# PCB_ICBExt-R1_0-J36-CH01.net
KiCad netlist of a schematic drawn in EAGLE
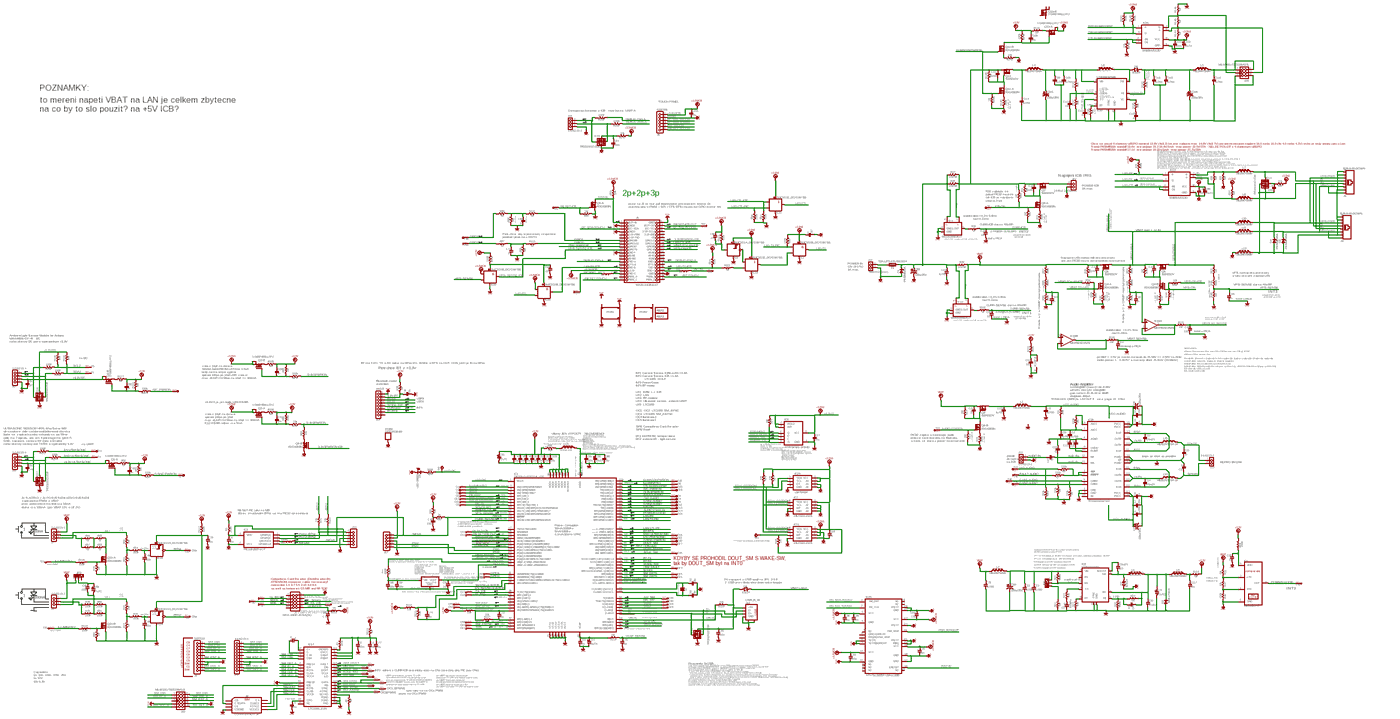
[diagram p0: schematic, sheet 1, overview]
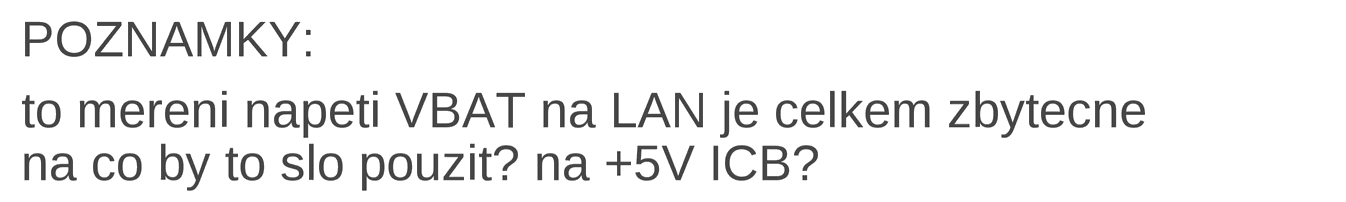
[diagram p1: schematic, sheet 1, part 1 of 6]
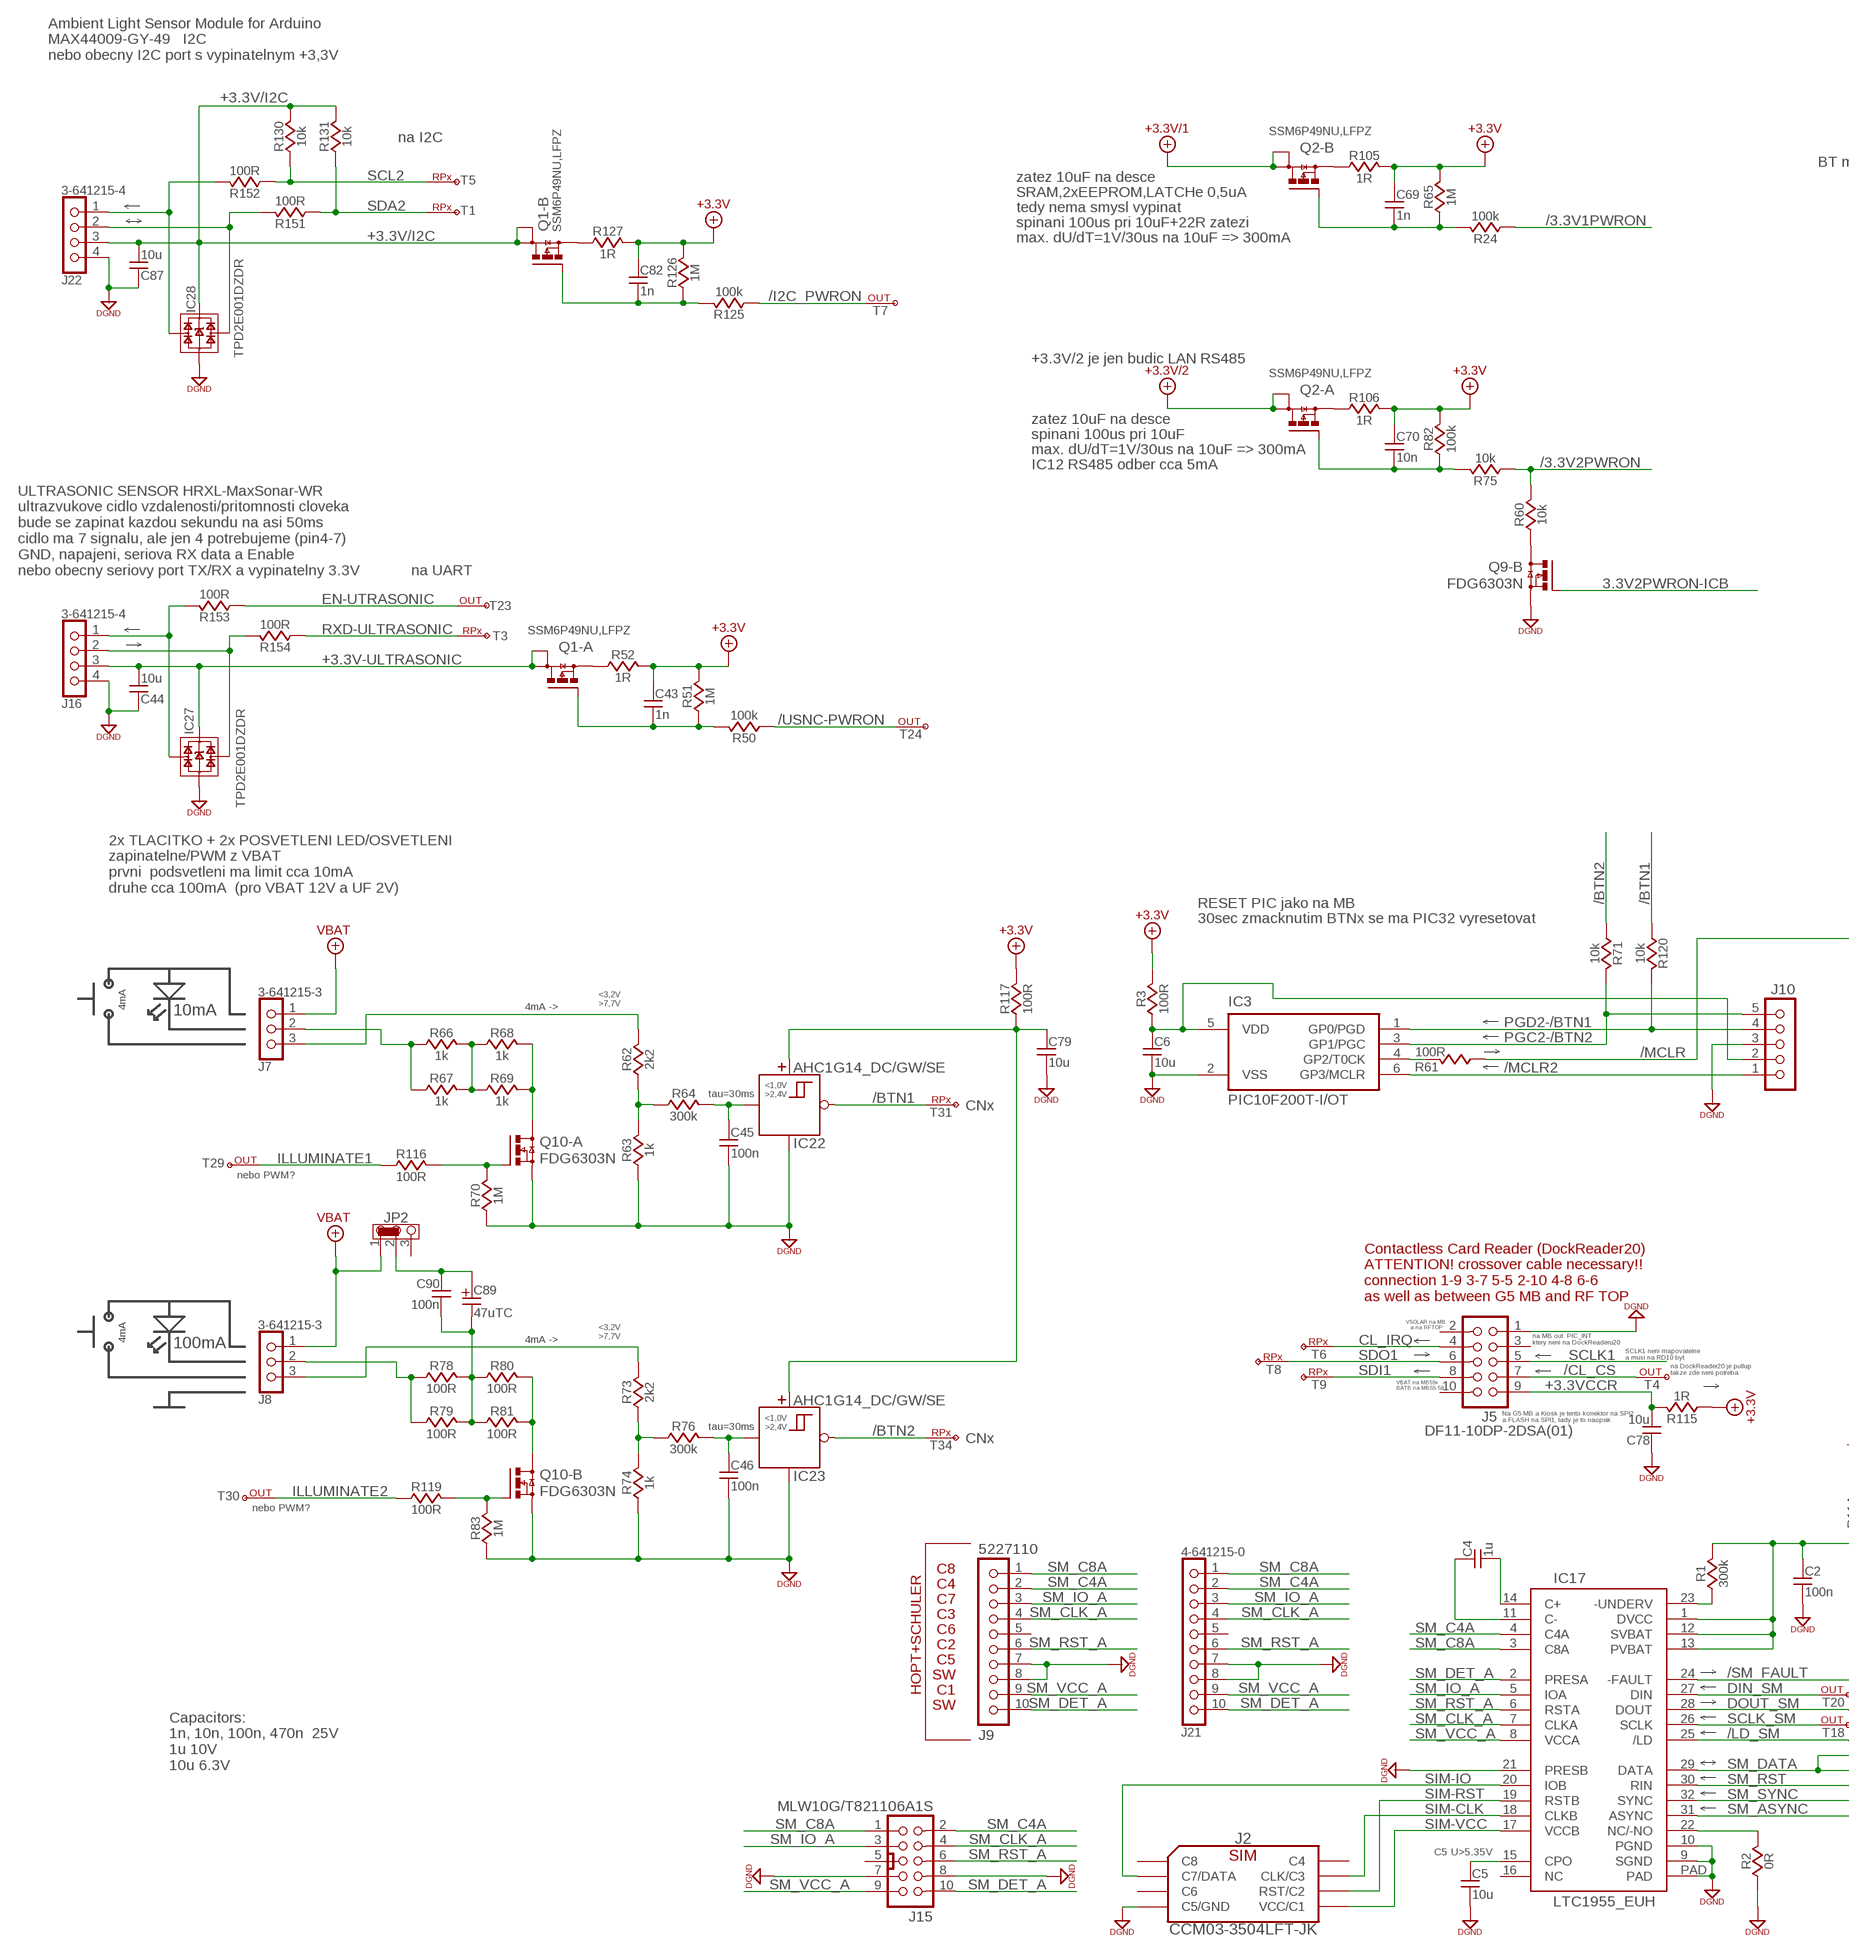
[diagram p2: schematic, sheet 1, part 2 of 6]
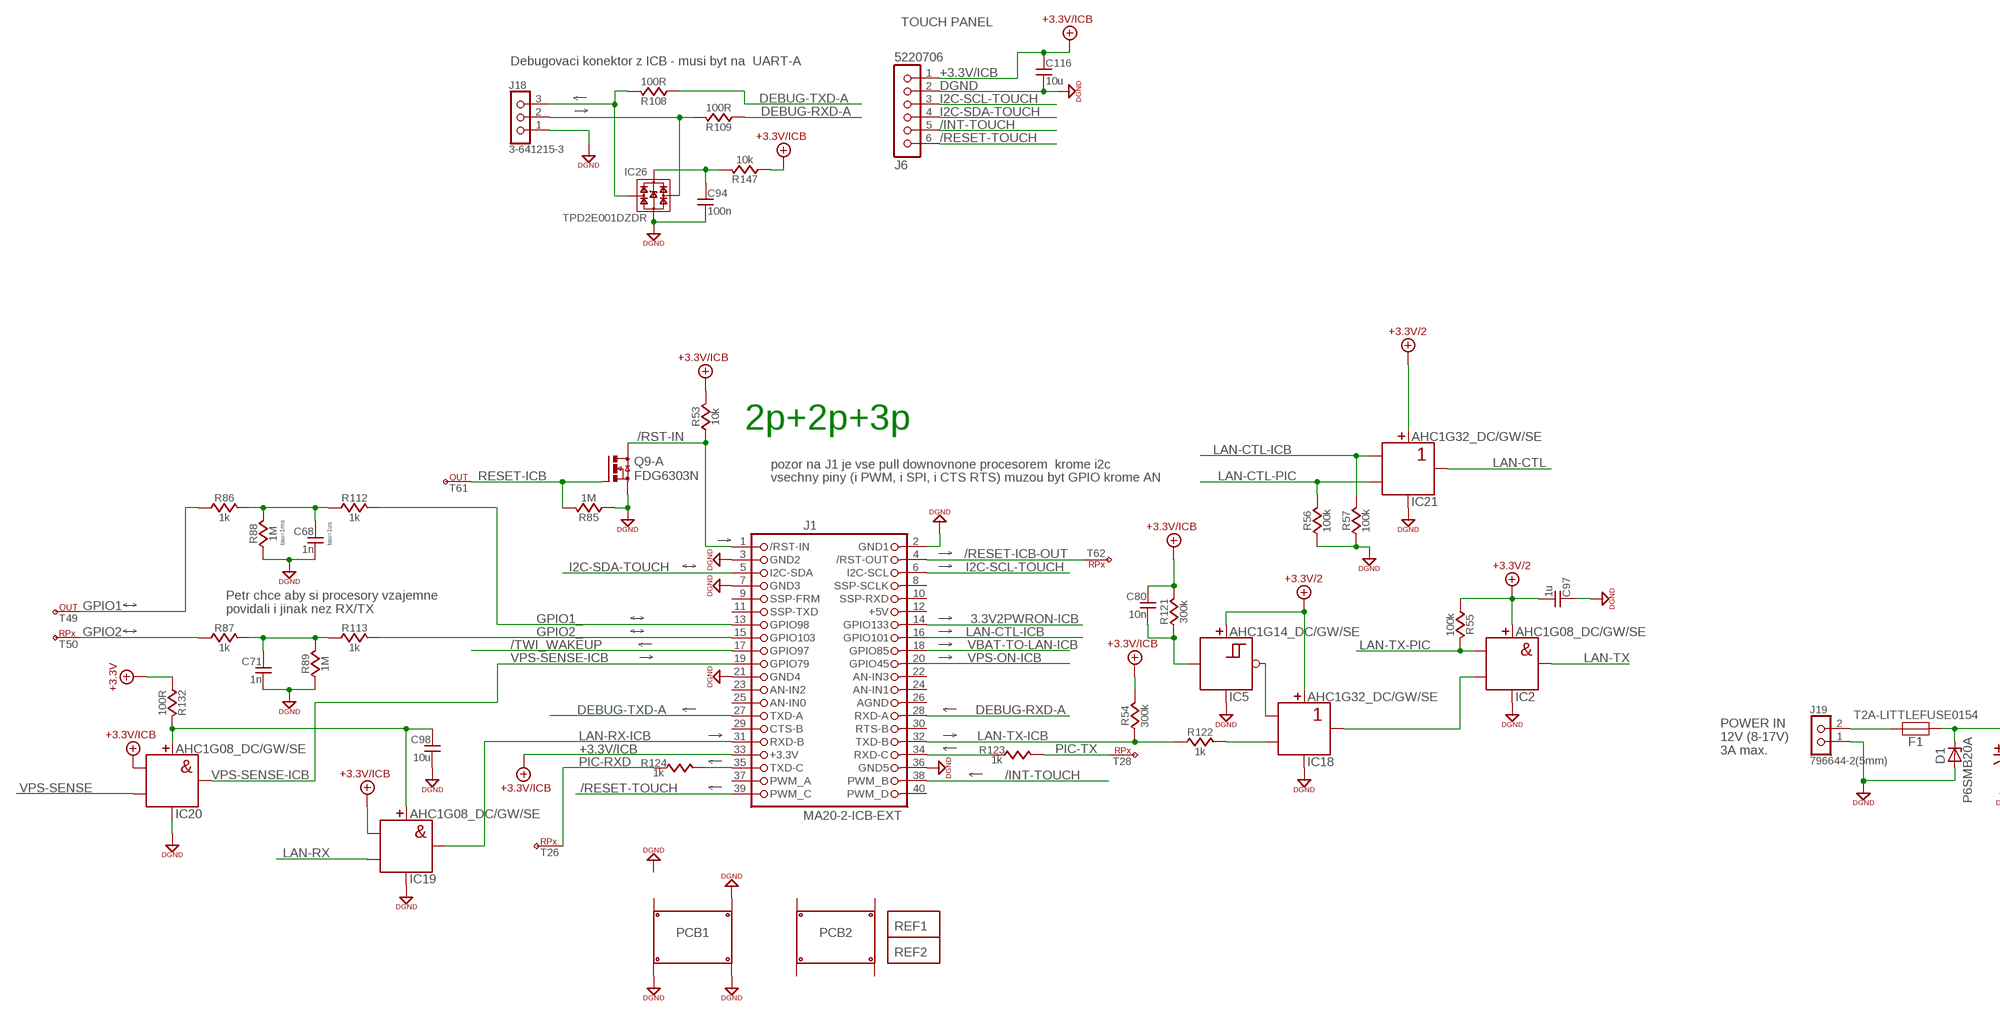
[diagram p3: schematic, sheet 1, part 3 of 6]
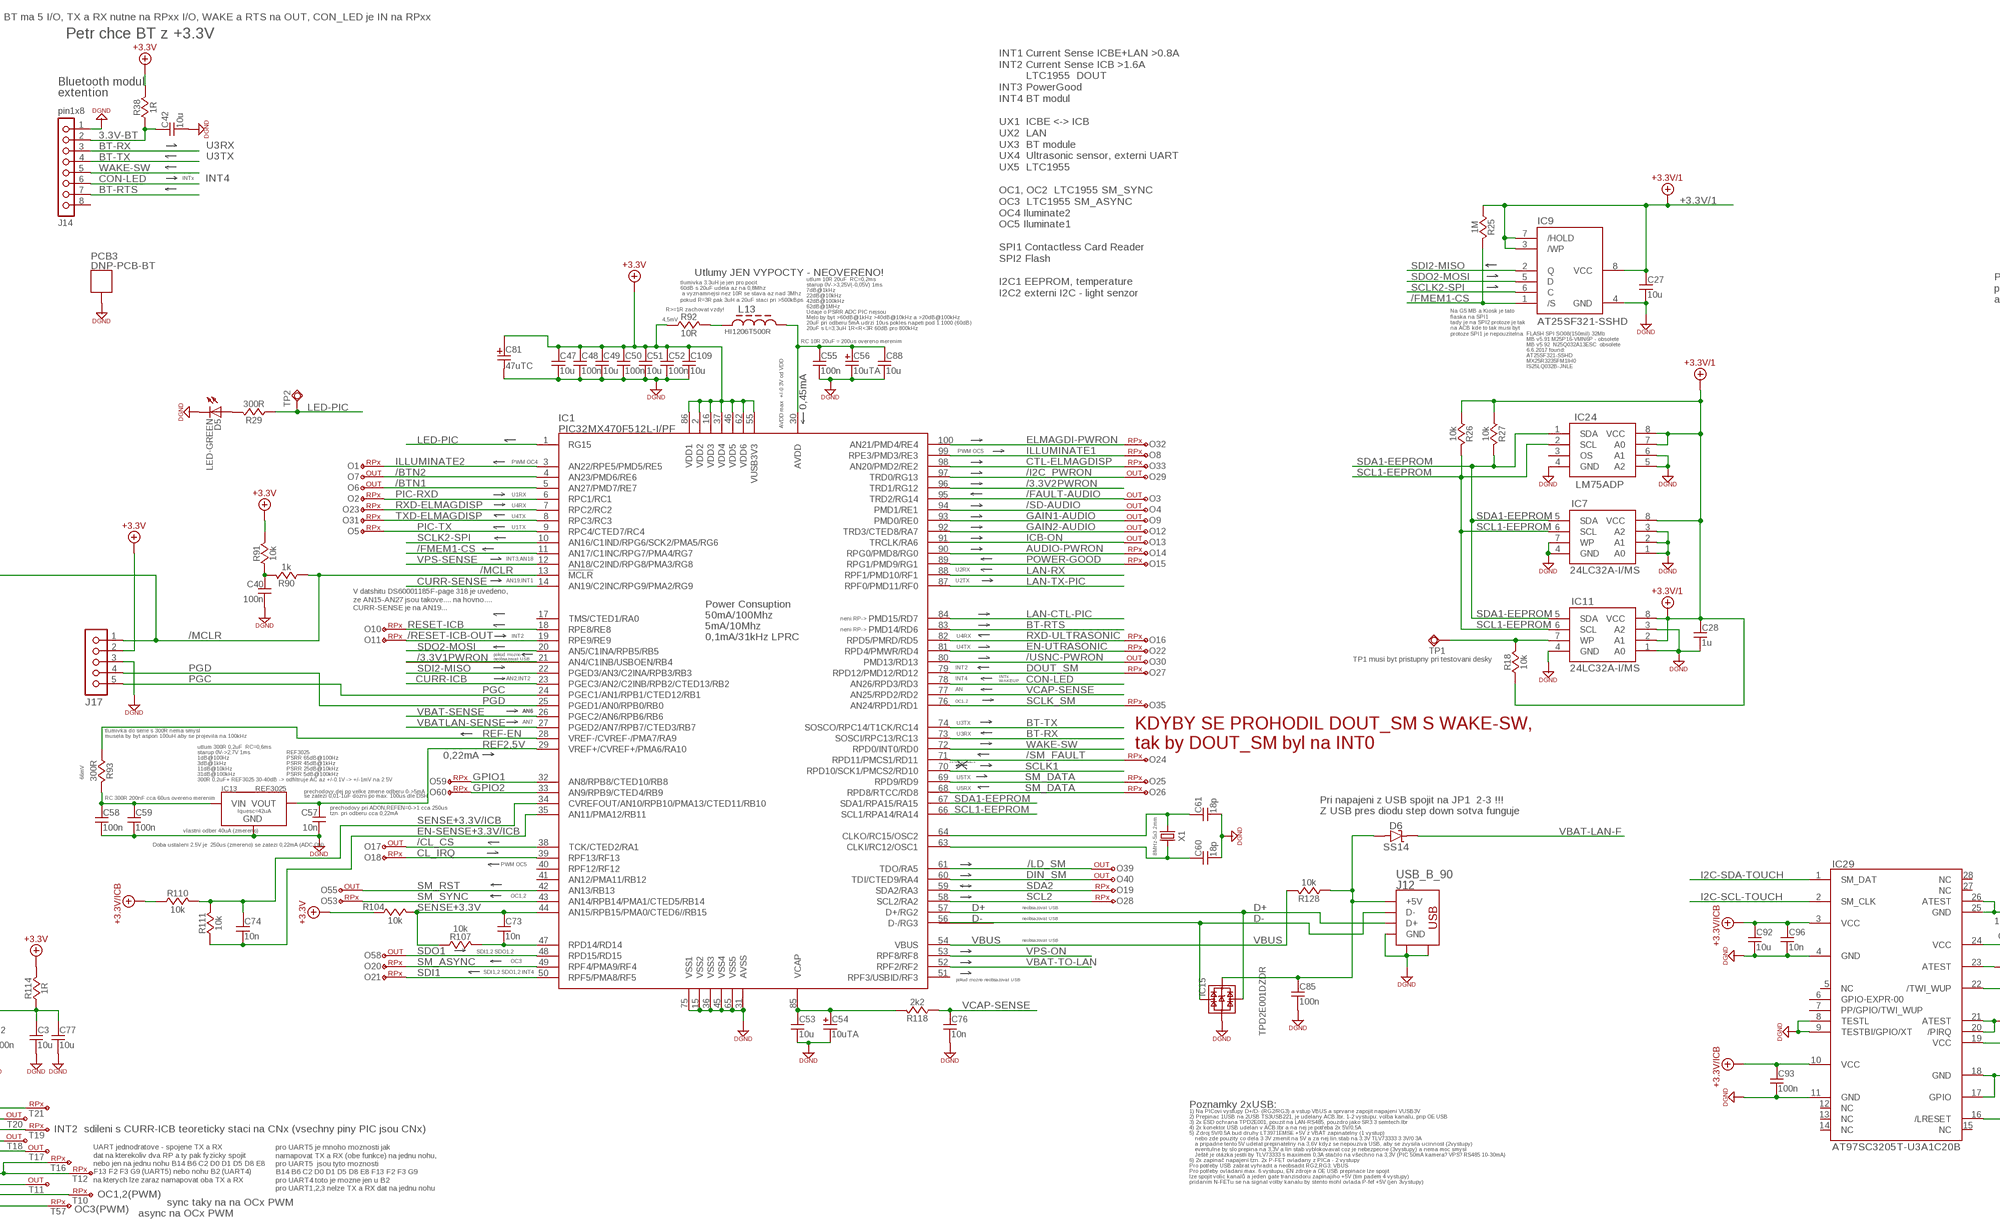
[diagram p4: schematic, sheet 1, part 4 of 6]
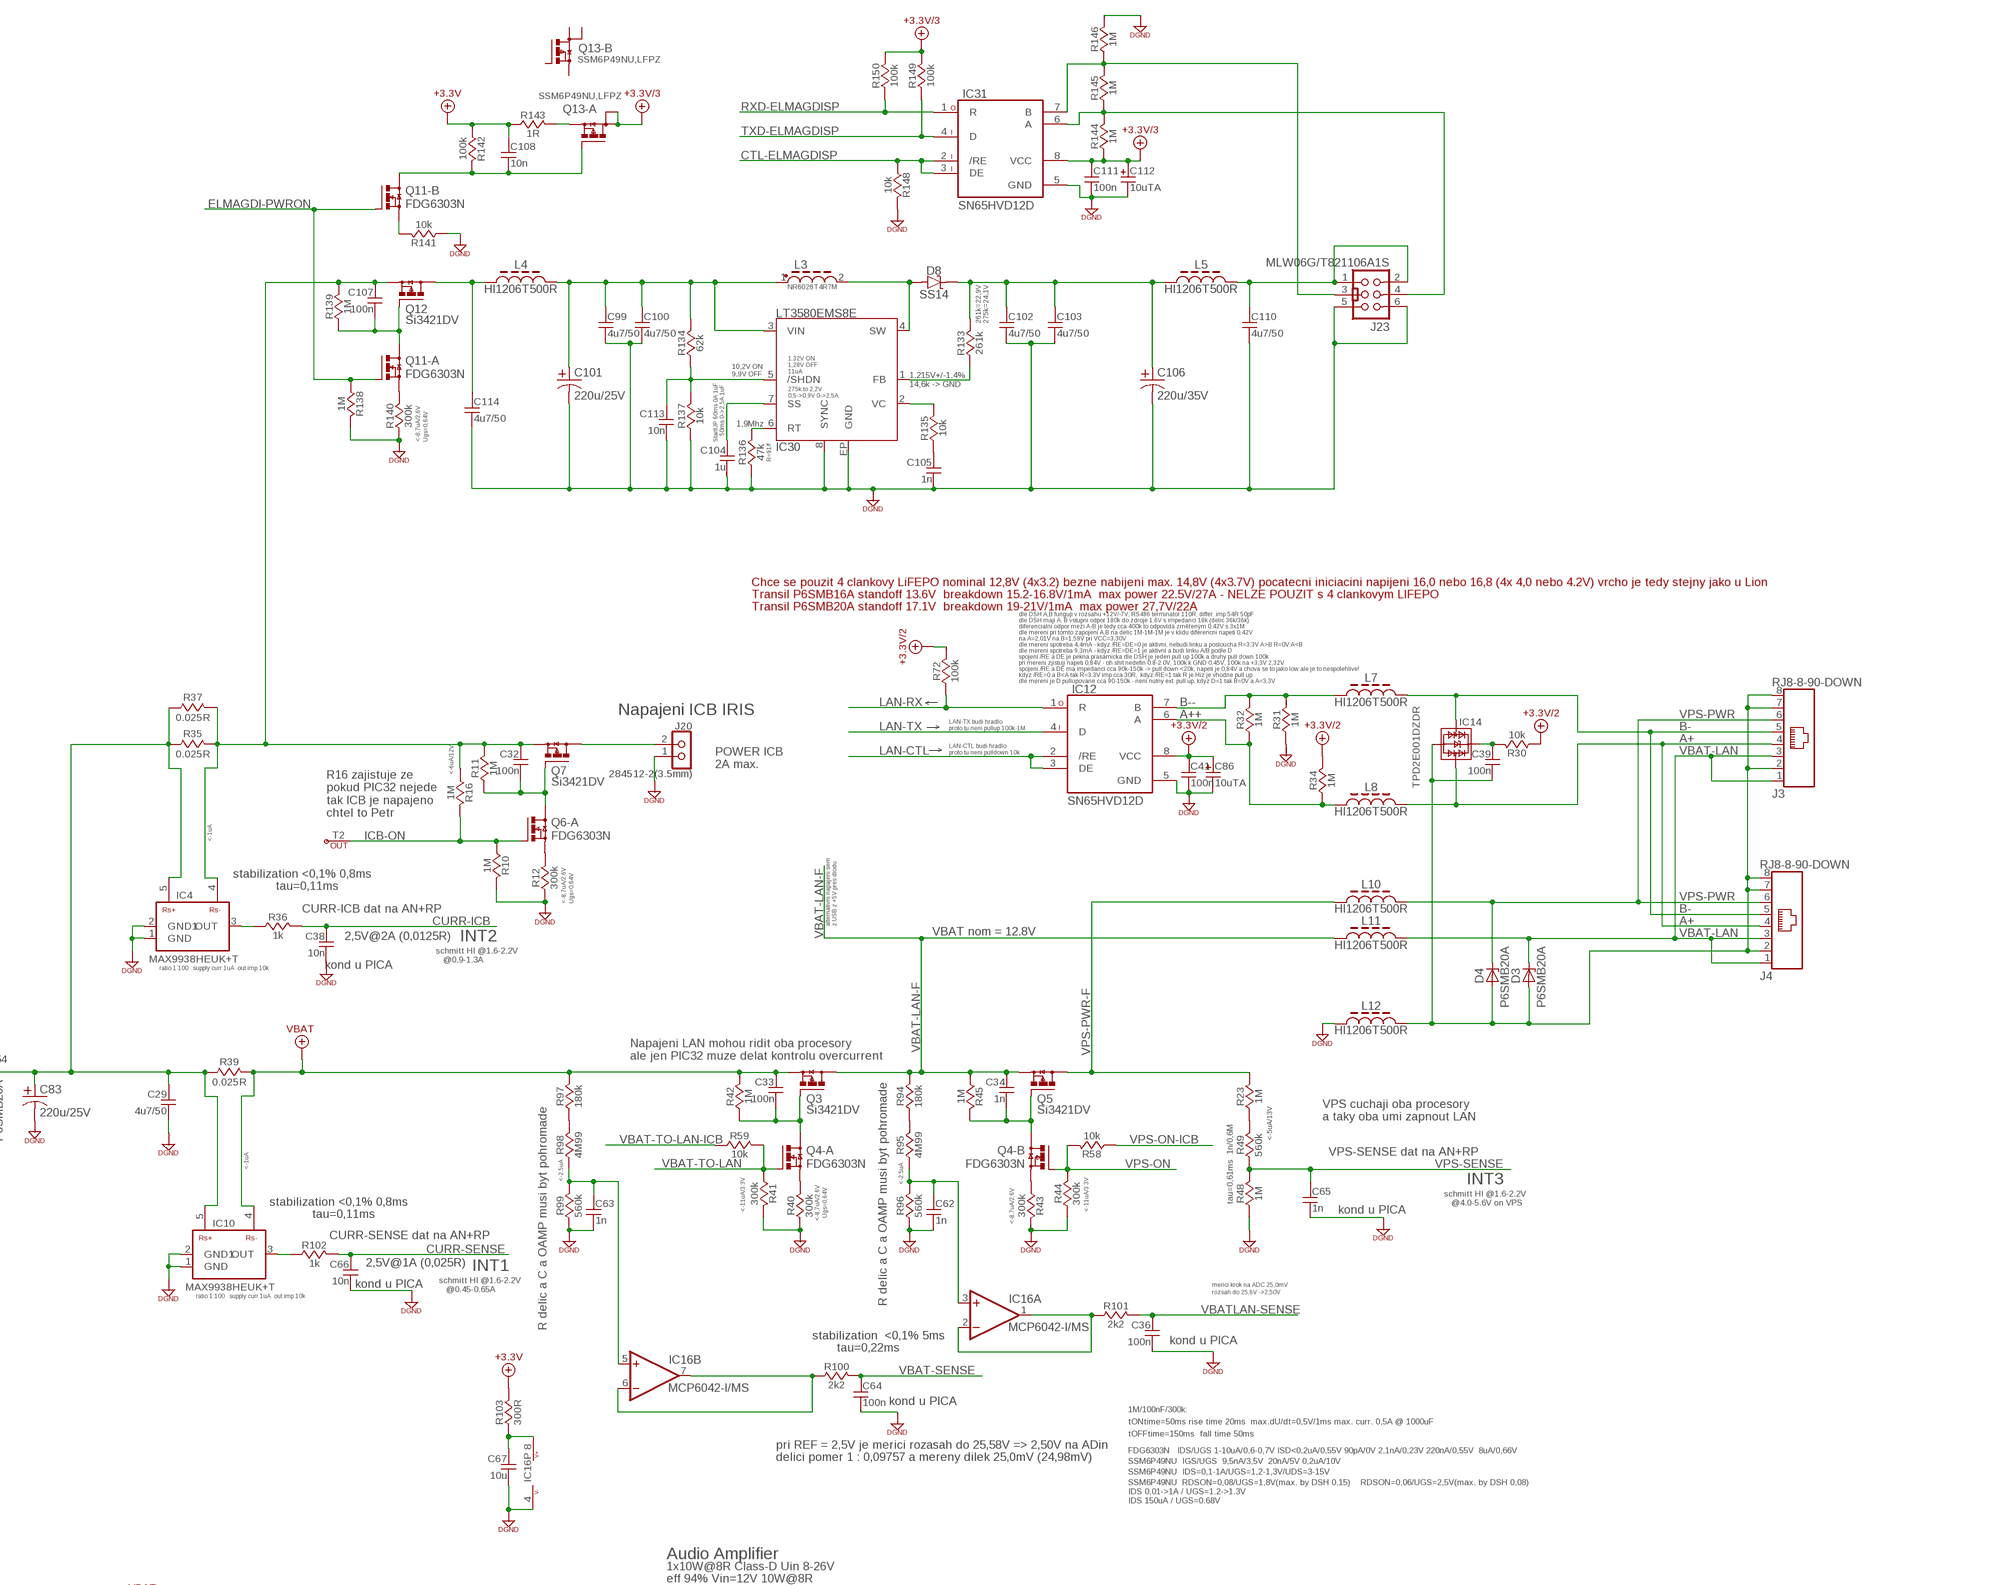
[diagram p5: schematic, sheet 1, part 5 of 6]
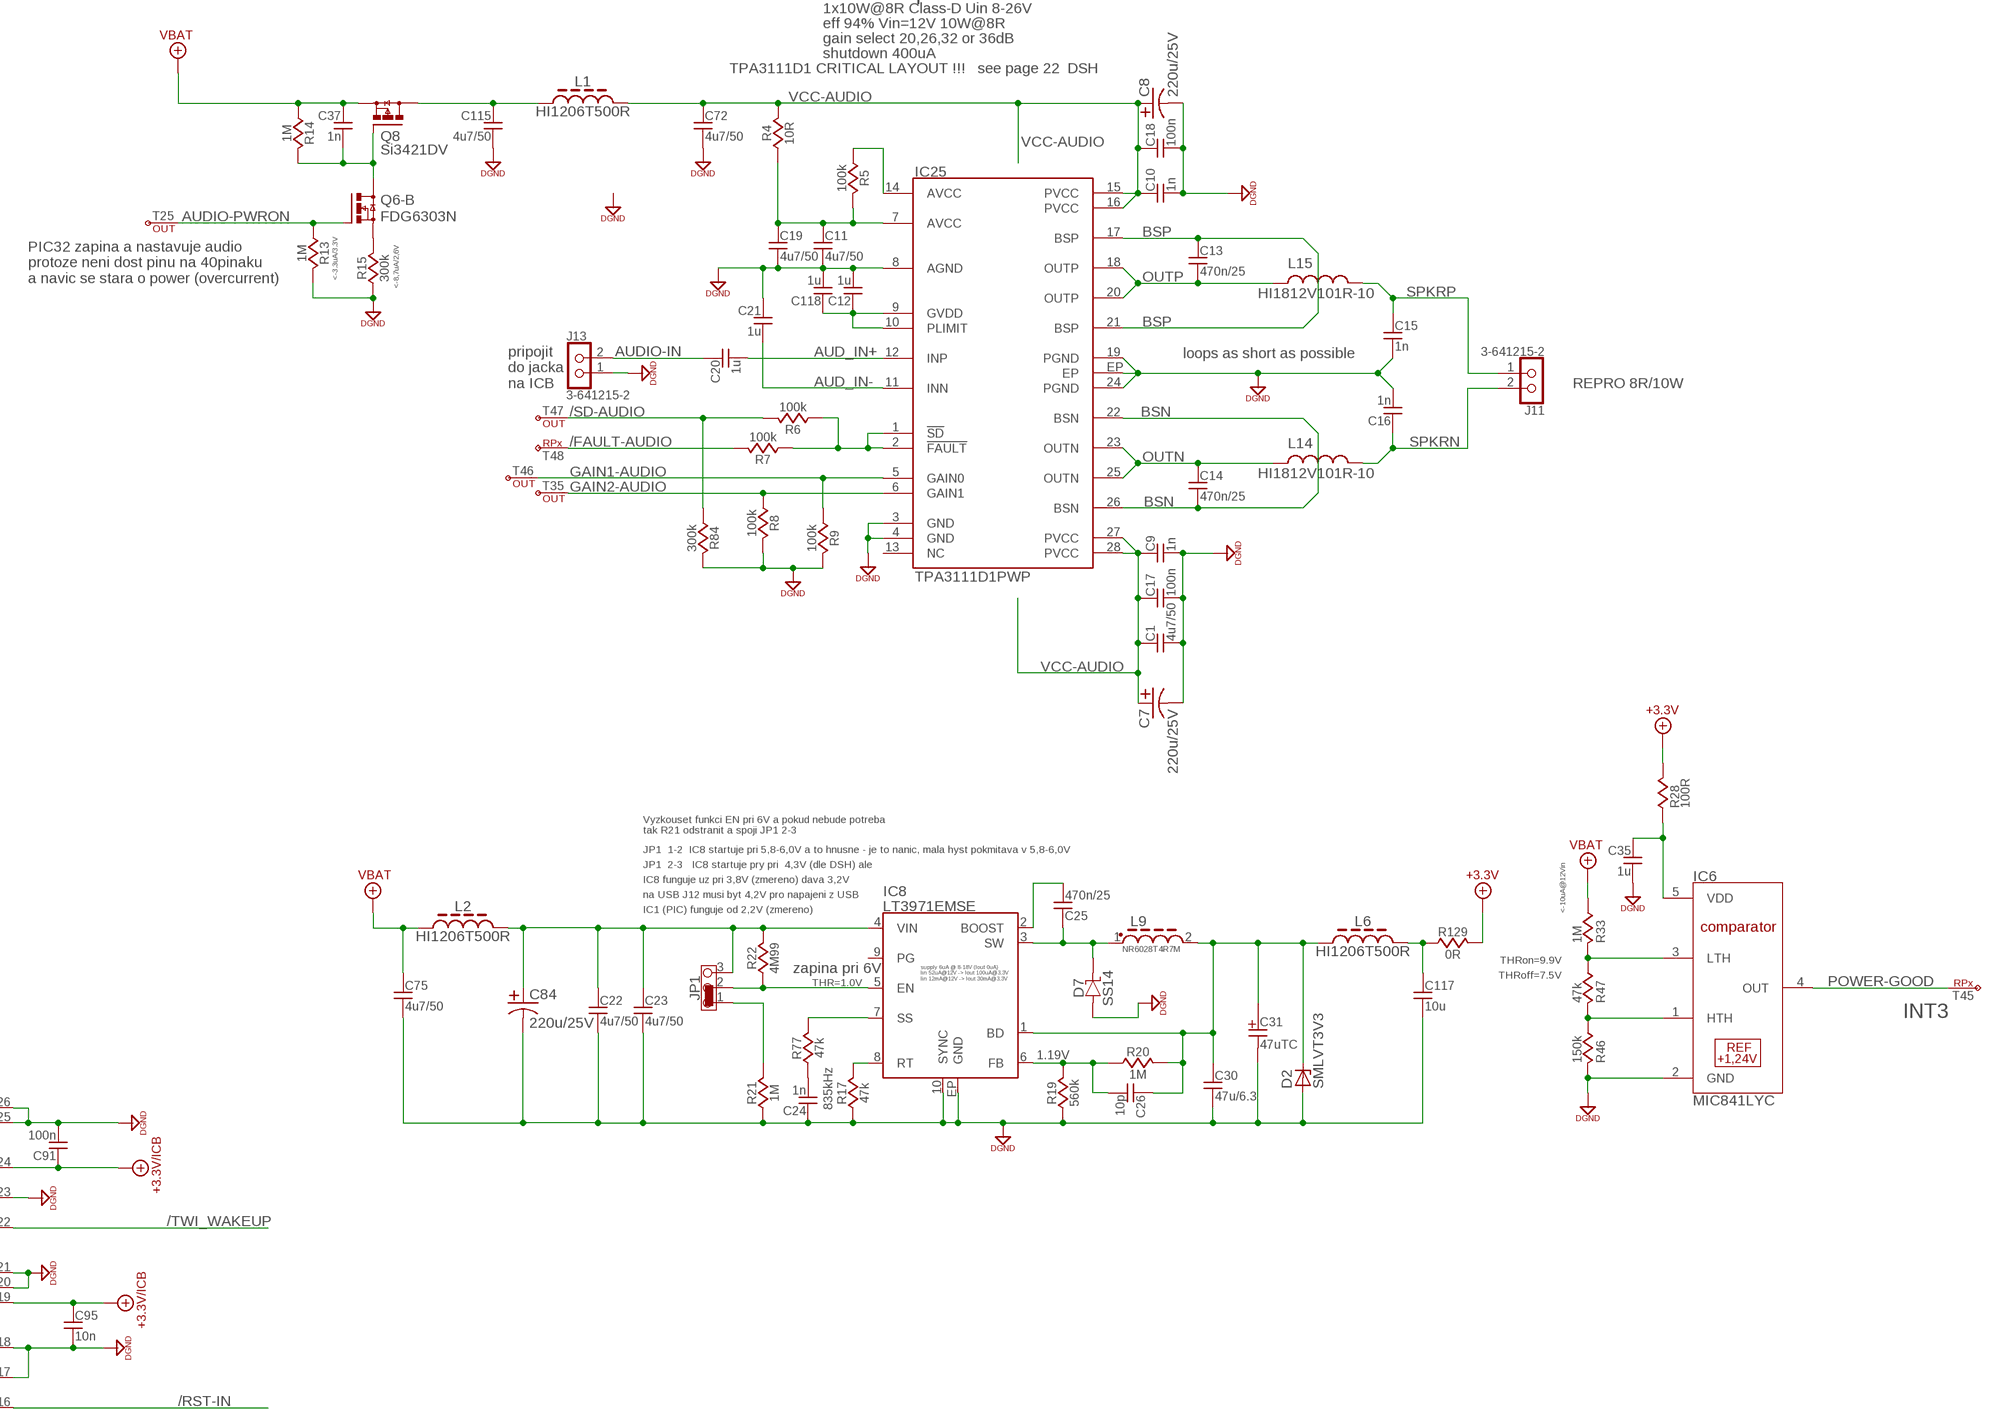
[diagram p6: schematic, sheet 1, part 6 of 6]

(export (version "E")
  (design (tool "Eeschema 10.0.6"))
  (components
    (comp (ref "C1")
      (value "4u7/50")
      (footprint "eagle-import:1206")
      (libsource (lib "eagle-import") (part "C-1206"))
    )
    (comp (ref "C2")
      (value "100n")
      (footprint "eagle-import:0603")
      (libsource (lib "eagle-import") (part "C-0603"))
    )
    (comp (ref "C3")
      (value "10u")
      (footprint "eagle-import:0603")
      (libsource (lib "eagle-import") (part "C-0603"))
    )
    (comp (ref "C4")
      (value "1u")
      (footprint "eagle-import:0603")
      (libsource (lib "eagle-import") (part "C-0603"))
    )
    (comp (ref "C5")
      (value "10u")
      (footprint "eagle-import:0603")
      (libsource (lib "eagle-import") (part "C-0603"))
    )
    (comp (ref "C6")
      (value "10u")
      (footprint "eagle-import:0603")
      (libsource (lib "eagle-import") (part "C-0603"))
    )
    (comp (ref "C7")
      (value "220u/25V")
      (footprint "eagle-import:CAP_8MM_DIA_SMT")
      (libsource (lib "eagle-import") (part "CAP-ELEC-SMD-8MM"))
    )
    (comp (ref "C8")
      (value "220u/25V")
      (footprint "eagle-import:CAP_8MM_DIA_SMT")
      (libsource (lib "eagle-import") (part "CAP-ELEC-SMD-8MM"))
    )
    (comp (ref "C9")
      (value "1n")
      (footprint "eagle-import:0603")
      (libsource (lib "eagle-import") (part "C-0603"))
    )
    (comp (ref "C10")
      (value "1n")
      (footprint "eagle-import:0603")
      (libsource (lib "eagle-import") (part "C-0603"))
    )
    (comp (ref "C11")
      (value "4u7/50")
      (footprint "eagle-import:1206")
      (libsource (lib "eagle-import") (part "C-1206"))
    )
    (comp (ref "C12")
      (value "1u")
      (footprint "eagle-import:0603")
      (libsource (lib "eagle-import") (part "C-0603"))
    )
    (comp (ref "C13")
      (value "470n/25")
      (footprint "eagle-import:0603")
      (libsource (lib "eagle-import") (part "C-0603"))
    )
    (comp (ref "C14")
      (value "470n/25")
      (footprint "eagle-import:0603")
      (libsource (lib "eagle-import") (part "C-0603"))
    )
    (comp (ref "C15")
      (value "1n")
      (footprint "eagle-import:0603")
      (libsource (lib "eagle-import") (part "C-0603"))
    )
    (comp (ref "C16")
      (value "1n")
      (footprint "eagle-import:0603")
      (libsource (lib "eagle-import") (part "C-0603"))
    )
    (comp (ref "C17")
      (value "100n")
      (footprint "eagle-import:0603")
      (libsource (lib "eagle-import") (part "C-0603"))
    )
    (comp (ref "C18")
      (value "100n")
      (footprint "eagle-import:0603")
      (libsource (lib "eagle-import") (part "C-0603"))
    )
    (comp (ref "C19")
      (value "4u7/50")
      (footprint "eagle-import:1206")
      (libsource (lib "eagle-import") (part "C-1206"))
    )
    (comp (ref "C20")
      (value "1u")
      (footprint "eagle-import:0603")
      (libsource (lib "eagle-import") (part "C-0603"))
    )
    (comp (ref "C21")
      (value "1u")
      (footprint "eagle-import:0603")
      (libsource (lib "eagle-import") (part "C-0603"))
    )
    (comp (ref "C22")
      (value "4u7/50")
      (footprint "eagle-import:1206")
      (libsource (lib "eagle-import") (part "C-1206"))
    )
    (comp (ref "C23")
      (value "4u7/50")
      (footprint "eagle-import:1206")
      (libsource (lib "eagle-import") (part "C-1206"))
    )
    (comp (ref "C24")
      (value "1n")
      (footprint "eagle-import:0603")
      (libsource (lib "eagle-import") (part "C-0603"))
    )
    (comp (ref "C25")
      (value "470n/25")
      (footprint "eagle-import:0603")
      (libsource (lib "eagle-import") (part "C-0603"))
    )
    (comp (ref "C26")
      (value "10p")
      (footprint "eagle-import:0603")
      (libsource (lib "eagle-import") (part "C-0603"))
    )
    (comp (ref "C27")
      (value "10u")
      (footprint "eagle-import:0603")
      (libsource (lib "eagle-import") (part "C-0603"))
    )
    (comp (ref "C28")
      (value "1u")
      (footprint "eagle-import:0603")
      (libsource (lib "eagle-import") (part "C-0603"))
    )
    (comp (ref "C29")
      (value "4u7/50")
      (footprint "eagle-import:1206")
      (libsource (lib "eagle-import") (part "C-1206"))
    )
    (comp (ref "C30")
      (value "47u/6.3")
      (footprint "eagle-import:1206")
      (libsource (lib "eagle-import") (part "C-1206"))
    )
    (comp (ref "C31")
      (value "47uTC")
      (footprint "eagle-import:CT-C")
      (libsource (lib "eagle-import") (part "CT-C"))
    )
    (comp (ref "C32")
      (value "100n")
      (footprint "eagle-import:0603")
      (libsource (lib "eagle-import") (part "C-0603"))
    )
    (comp (ref "C33")
      (value "100n")
      (footprint "eagle-import:0603")
      (libsource (lib "eagle-import") (part "C-0603"))
    )
    (comp (ref "C34")
      (value "1n")
      (footprint "eagle-import:0603")
      (libsource (lib "eagle-import") (part "C-0603"))
    )
    (comp (ref "C35")
      (value "1u")
      (footprint "eagle-import:0603")
      (libsource (lib "eagle-import") (part "C-0603"))
    )
    (comp (ref "C36")
      (value "100n")
      (footprint "eagle-import:0603")
      (libsource (lib "eagle-import") (part "C-0603"))
    )
    (comp (ref "C37")
      (value "1n")
      (footprint "eagle-import:0603")
      (libsource (lib "eagle-import") (part "C-0603"))
    )
    (comp (ref "C38")
      (value "10n")
      (footprint "eagle-import:0603")
      (libsource (lib "eagle-import") (part "C-0603"))
    )
    (comp (ref "C39")
      (value "100n")
      (footprint "eagle-import:0603")
      (libsource (lib "eagle-import") (part "C-0603"))
    )
    (comp (ref "C40")
      (value "100n")
      (footprint "eagle-import:0603")
      (libsource (lib "eagle-import") (part "C-0603"))
    )
    (comp (ref "C41")
      (value "100n")
      (footprint "eagle-import:0603")
      (libsource (lib "eagle-import") (part "C-0603"))
    )
    (comp (ref "C42")
      (value "10u")
      (footprint "eagle-import:0603")
      (libsource (lib "eagle-import") (part "C-0603"))
    )
    (comp (ref "C43")
      (value "1n")
      (footprint "eagle-import:0603")
      (libsource (lib "eagle-import") (part "C-0603"))
    )
    (comp (ref "C44")
      (value "10u")
      (footprint "eagle-import:0603")
      (libsource (lib "eagle-import") (part "C-0603"))
    )
    (comp (ref "C45")
      (value "100n")
      (footprint "eagle-import:0603")
      (libsource (lib "eagle-import") (part "C-0603"))
    )
    (comp (ref "C46")
      (value "100n")
      (footprint "eagle-import:0603")
      (libsource (lib "eagle-import") (part "C-0603"))
    )
    (comp (ref "C47")
      (value "10u")
      (footprint "eagle-import:0603")
      (libsource (lib "eagle-import") (part "C-0603"))
    )
    (comp (ref "C48")
      (value "100n")
      (footprint "eagle-import:0603")
      (libsource (lib "eagle-import") (part "C-0603"))
    )
    (comp (ref "C49")
      (value "10u")
      (footprint "eagle-import:0603")
      (libsource (lib "eagle-import") (part "C-0603"))
    )
    (comp (ref "C50")
      (value "100n")
      (footprint "eagle-import:0603")
      (libsource (lib "eagle-import") (part "C-0603"))
    )
    (comp (ref "C51")
      (value "10u")
      (footprint "eagle-import:0603")
      (libsource (lib "eagle-import") (part "C-0603"))
    )
    (comp (ref "C52")
      (value "100n")
      (footprint "eagle-import:0603")
      (libsource (lib "eagle-import") (part "C-0603"))
    )
    (comp (ref "C53")
      (value "10u")
      (footprint "eagle-import:0603")
      (libsource (lib "eagle-import") (part "C-0603"))
    )
    (comp (ref "C54")
      (value "10uTA")
      (footprint "eagle-import:1206-POL-C")
      (libsource (lib "eagle-import") (part "CT-1206"))
    )
    (comp (ref "C55")
      (value "100n")
      (footprint "eagle-import:0603")
      (libsource (lib "eagle-import") (part "C-0603"))
    )
    (comp (ref "C56")
      (value "10uTA")
      (footprint "eagle-import:1206-POL-C")
      (libsource (lib "eagle-import") (part "CT-1206"))
    )
    (comp (ref "C57")
      (value "10n")
      (footprint "eagle-import:0603")
      (libsource (lib "eagle-import") (part "C-0603"))
    )
    (comp (ref "C58")
      (value "100n")
      (footprint "eagle-import:0603")
      (libsource (lib "eagle-import") (part "C-0603"))
    )
    (comp (ref "C59")
      (value "100n")
      (footprint "eagle-import:0603")
      (libsource (lib "eagle-import") (part "C-0603"))
    )
    (comp (ref "C60")
      (value "18p")
      (footprint "eagle-import:0603")
      (libsource (lib "eagle-import") (part "C-0603"))
    )
    (comp (ref "C61")
      (value "18p")
      (footprint "eagle-import:0603")
      (libsource (lib "eagle-import") (part "C-0603"))
    )
    (comp (ref "C62")
      (value "1n")
      (footprint "eagle-import:0603")
      (libsource (lib "eagle-import") (part "C-0603"))
    )
    (comp (ref "C63")
      (value "1n")
      (footprint "eagle-import:0603")
      (libsource (lib "eagle-import") (part "C-0603"))
    )
    (comp (ref "C64")
      (value "100n")
      (footprint "eagle-import:0603")
      (libsource (lib "eagle-import") (part "C-0603"))
    )
    (comp (ref "C65")
      (value "1n")
      (footprint "eagle-import:0603")
      (libsource (lib "eagle-import") (part "C-0603"))
    )
    (comp (ref "C66")
      (value "10n")
      (footprint "eagle-import:0603")
      (libsource (lib "eagle-import") (part "C-0603"))
    )
    (comp (ref "C67")
      (value "10u")
      (footprint "eagle-import:0603")
      (libsource (lib "eagle-import") (part "C-0603"))
    )
    (comp (ref "C68")
      (value "1n")
      (footprint "eagle-import:0603")
      (libsource (lib "eagle-import") (part "C-0603"))
    )
    (comp (ref "C69")
      (value "1n")
      (footprint "eagle-import:0603")
      (libsource (lib "eagle-import") (part "C-0603"))
    )
    (comp (ref "C70")
      (value "10n")
      (footprint "eagle-import:0603")
      (libsource (lib "eagle-import") (part "C-0603"))
    )
    (comp (ref "C71")
      (value "1n")
      (footprint "eagle-import:0603")
      (libsource (lib "eagle-import") (part "C-0603"))
    )
    (comp (ref "C72")
      (value "4u7/50")
      (footprint "eagle-import:1206")
      (libsource (lib "eagle-import") (part "C-1206"))
    )
    (comp (ref "C73")
      (value "10n")
      (footprint "eagle-import:0603")
      (libsource (lib "eagle-import") (part "C-0603"))
    )
    (comp (ref "C74")
      (value "10n")
      (footprint "eagle-import:0603")
      (libsource (lib "eagle-import") (part "C-0603"))
    )
    (comp (ref "C75")
      (value "4u7/50")
      (footprint "eagle-import:1206")
      (libsource (lib "eagle-import") (part "C-1206"))
    )
    (comp (ref "C76")
      (value "10n")
      (footprint "eagle-import:0603")
      (libsource (lib "eagle-import") (part "C-0603"))
    )
    (comp (ref "C77")
      (value "10u")
      (footprint "eagle-import:0603")
      (libsource (lib "eagle-import") (part "C-0603"))
    )
    (comp (ref "C78")
      (value "10u")
      (footprint "eagle-import:0603")
      (libsource (lib "eagle-import") (part "C-0603"))
    )
    (comp (ref "C79")
      (value "10u")
      (footprint "eagle-import:0603")
      (libsource (lib "eagle-import") (part "C-0603"))
    )
    (comp (ref "C80")
      (value "10n")
      (footprint "eagle-import:0603")
      (libsource (lib "eagle-import") (part "C-0603"))
    )
    (comp (ref "C81")
      (value "47uTC")
      (footprint "eagle-import:CT-C")
      (libsource (lib "eagle-import") (part "CT-C"))
    )
    (comp (ref "C82")
      (value "1n")
      (footprint "eagle-import:0603")
      (libsource (lib "eagle-import") (part "C-0603"))
    )
    (comp (ref "C83")
      (value "220u/25V")
      (footprint "eagle-import:CAP_8MM_DIA_SMT")
      (libsource (lib "eagle-import") (part "CAP-ELEC-SMD-8MM"))
    )
    (comp (ref "C84")
      (value "220u/25V")
      (footprint "eagle-import:CAP_8MM_DIA_SMT")
      (libsource (lib "eagle-import") (part "CAP-ELEC-SMD-8MM"))
    )
    (comp (ref "C85")
      (value "100n")
      (footprint "eagle-import:0603")
      (libsource (lib "eagle-import") (part "C-0603"))
    )
    (comp (ref "C86")
      (value "10uTA")
      (footprint "eagle-import:1206-POL-C")
      (libsource (lib "eagle-import") (part "CT-1206"))
    )
    (comp (ref "C87")
      (value "10u")
      (footprint "eagle-import:0603")
      (libsource (lib "eagle-import") (part "C-0603"))
    )
    (comp (ref "C88")
      (value "10u")
      (footprint "eagle-import:0603")
      (libsource (lib "eagle-import") (part "C-0603"))
    )
    (comp (ref "C89")
      (value "47uTC")
      (footprint "eagle-import:CT-C")
      (libsource (lib "eagle-import") (part "CT-C"))
    )
    (comp (ref "C90")
      (value "100n")
      (footprint "eagle-import:0603")
      (libsource (lib "eagle-import") (part "C-0603"))
    )
    (comp (ref "C91")
      (value "100n")
      (footprint "eagle-import:0603")
      (libsource (lib "eagle-import") (part "C-0603"))
    )
    (comp (ref "C92")
      (value "10u")
      (footprint "eagle-import:0603")
      (libsource (lib "eagle-import") (part "C-0603"))
    )
    (comp (ref "C93")
      (value "100n")
      (footprint "eagle-import:0603")
      (libsource (lib "eagle-import") (part "C-0603"))
    )
    (comp (ref "C94")
      (value "100n")
      (footprint "eagle-import:0603")
      (libsource (lib "eagle-import") (part "C-0603"))
    )
    (comp (ref "C95")
      (value "10n")
      (footprint "eagle-import:0603")
      (libsource (lib "eagle-import") (part "C-0603"))
    )
    (comp (ref "C96")
      (value "10n")
      (footprint "eagle-import:0603")
      (libsource (lib "eagle-import") (part "C-0603"))
    )
    (comp (ref "C97")
      (value "1u")
      (footprint "eagle-import:0603")
      (libsource (lib "eagle-import") (part "C-0603"))
    )
    (comp (ref "C98")
      (value "10u")
      (footprint "eagle-import:0603")
      (libsource (lib "eagle-import") (part "C-0603"))
    )
    (comp (ref "C99")
      (value "4u7/50")
      (footprint "eagle-import:1206")
      (libsource (lib "eagle-import") (part "C-1206"))
    )
    (comp (ref "C100")
      (value "4u7/50")
      (footprint "eagle-import:1206")
      (libsource (lib "eagle-import") (part "C-1206"))
    )
    (comp (ref "C101")
      (value "220u/25V")
      (footprint "eagle-import:CAP_8MM_DIA_SMT")
      (libsource (lib "eagle-import") (part "CAP-ELEC-SMD-8MM"))
    )
    (comp (ref "C102")
      (value "4u7/50")
      (footprint "eagle-import:1206")
      (libsource (lib "eagle-import") (part "C-1206"))
    )
    (comp (ref "C103")
      (value "4u7/50")
      (footprint "eagle-import:1206")
      (libsource (lib "eagle-import") (part "C-1206"))
    )
    (comp (ref "C104")
      (value "1u")
      (footprint "eagle-import:0603")
      (libsource (lib "eagle-import") (part "C-0603"))
    )
    (comp (ref "C105")
      (value "1n")
      (footprint "eagle-import:0603")
      (libsource (lib "eagle-import") (part "C-0603"))
    )
    (comp (ref "C106")
      (value "220u/35V")
      (footprint "eagle-import:CAP_8MM_DIA_SMT")
      (libsource (lib "eagle-import") (part "CAP-ELEC-SMD-8MM"))
    )
    (comp (ref "C107")
      (value "100n")
      (footprint "eagle-import:0603")
      (libsource (lib "eagle-import") (part "C-0603"))
    )
    (comp (ref "C108")
      (value "10n")
      (footprint "eagle-import:0603")
      (libsource (lib "eagle-import") (part "C-0603"))
    )
    (comp (ref "C109")
      (value "10u")
      (footprint "eagle-import:0603")
      (libsource (lib "eagle-import") (part "C-0603"))
    )
    (comp (ref "C110")
      (value "4u7/50")
      (footprint "eagle-import:1206")
      (libsource (lib "eagle-import") (part "C-1206"))
    )
    (comp (ref "C111")
      (value "100n")
      (footprint "eagle-import:0603")
      (libsource (lib "eagle-import") (part "C-0603"))
    )
    (comp (ref "C112")
      (value "10uTA")
      (footprint "eagle-import:1206-POL-C")
      (libsource (lib "eagle-import") (part "CT-1206"))
    )
    (comp (ref "C113")
      (value "10n")
      (footprint "eagle-import:0603")
      (libsource (lib "eagle-import") (part "C-0603"))
    )
    (comp (ref "C114")
      (value "4u7/50")
      (footprint "eagle-import:1206")
      (libsource (lib "eagle-import") (part "C-1206"))
    )
    (comp (ref "C115")
      (value "4u7/50")
      (footprint "eagle-import:1206")
      (libsource (lib "eagle-import") (part "C-1206"))
    )
    (comp (ref "C116")
      (value "10u")
      (footprint "eagle-import:0603")
      (libsource (lib "eagle-import") (part "C-0603"))
    )
    (comp (ref "C117")
      (value "10u")
      (footprint "eagle-import:0603")
      (libsource (lib "eagle-import") (part "C-0603"))
    )
    (comp (ref "C118")
      (value "1u")
      (footprint "eagle-import:0603")
      (libsource (lib "eagle-import") (part "C-0603"))
    )
    (comp (ref "D1")
      (value "P6SMB20A")
      (footprint "eagle-import:SMB")
      (libsource (lib "eagle-import") (part "P6SMB"))
    )
    (comp (ref "D2")
      (value "SMLVT3V3")
      (footprint "eagle-import:SMA")
      (libsource (lib "eagle-import") (part "SMLVT3V3"))
    )
    (comp (ref "D3")
      (value "P6SMB20A")
      (footprint "eagle-import:SMB")
      (libsource (lib "eagle-import") (part "P6SMB"))
    )
    (comp (ref "D4")
      (value "P6SMB20A")
      (footprint "eagle-import:SMB")
      (libsource (lib "eagle-import") (part "P6SMB"))
    )
    (comp (ref "D5")
      (value "LED-GREEN")
      (footprint "eagle-import:0805-POL-D")
      (libsource (lib "eagle-import") (part "LED-0805"))
    )
    (comp (ref "D6")
      (value "SS14")
      (footprint "eagle-import:SMA")
      (libsource (lib "eagle-import") (part "DS-SMA"))
    )
    (comp (ref "D7")
      (value "SS14")
      (footprint "eagle-import:SMA")
      (libsource (lib "eagle-import") (part "DS-SMA"))
    )
    (comp (ref "D8")
      (value "SS14")
      (footprint "eagle-import:SMA")
      (libsource (lib "eagle-import") (part "DS-SMA"))
    )
    (comp (ref "F1")
      (value "T2A-LITTLEFUSE0154")
      (footprint "eagle-import:LITTLEFUSE0154")
      (libsource (lib "eagle-import") (part "POJISTKA-LITTLEFUSE0154"))
    )
    (comp (ref "IC1")
      (value "PIC32MX470F512L-I/PF")
      (footprint "eagle-import:TQFP100_14X14_0,5MM")
      (libsource (lib "eagle-import") (part "PIC32MX470F512L-I/PF"))
    )
    (comp (ref "IC2")
      (value "AHC1G08_DC/GW/SE")
      (footprint "eagle-import:SC70-5,SOT353,TSSOP5")
      (libsource (lib "eagle-import") (part "AHC1G08"))
    )
    (comp (ref "IC3")
      (value "PIC10F200T-I/OT")
      (footprint "eagle-import:SOT23-6")
      (libsource (lib "eagle-import") (part "PIC10F200T-I/OT"))
    )
    (comp (ref "IC4")
      (value "MAX9938HEUK+T")
      (footprint "eagle-import:SOT23-5")
      (libsource (lib "eagle-import") (part "TSM9938HEUK+T"))
    )
    (comp (ref "IC5")
      (value "AHC1G14_DC/GW/SE")
      (footprint "eagle-import:SC70-5,SOT353,TSSOP5")
      (libsource (lib "eagle-import") (part "AHC1G14"))
    )
    (comp (ref "IC6")
      (value "MIC841LYC")
      (footprint "eagle-import:SC-70-5")
      (libsource (lib "eagle-import") (part "MIC841LYC"))
    )
    (comp (ref "IC7")
      (value "24LC32A-I/MS")
      (footprint "eagle-import:MSOP-08")
      (libsource (lib "eagle-import") (part "24-I/MS"))
    )
    (comp (ref "IC8")
      (value "LT3971EMSE")
      (footprint "eagle-import:MSOP10EXP")
      (libsource (lib "eagle-import") (part "LT3971EMSE"))
    )
    (comp (ref "IC9")
      (value "AT25SF321-SSHD")
      (footprint "eagle-import:SO-08")
      (libsource (lib "eagle-import") (part "M25P16-VMN6P"))
    )
    (comp (ref "IC10")
      (value "MAX9938HEUK+T")
      (footprint "eagle-import:SOT23-5")
      (libsource (lib "eagle-import") (part "TSM9938HEUK+T"))
    )
    (comp (ref "IC11")
      (value "24LC32A-I/MS")
      (footprint "eagle-import:MSOP-08")
      (libsource (lib "eagle-import") (part "24-I/MS"))
    )
    (comp (ref "IC12")
      (value "SN65HVD12D")
      (footprint "eagle-import:SO08")
      (libsource (lib "eagle-import") (part "SN65HVD3082ED"))
    )
    (comp (ref "IC13")
      (value "REF3025")
      (footprint "eagle-import:SOT23")
      (libsource (lib "eagle-import") (part "REF3025"))
    )
    (comp (ref "IC14")
      (value "TPD2E001DZDR")
      (footprint "eagle-import:SOT-143")
      (libsource (lib "eagle-import") (part "SR05.TCT"))
    )
    (comp (ref "IC15")
      (value "TPD2E001DZDR")
      (footprint "eagle-import:SOT-143")
      (libsource (lib "eagle-import") (part "SR05.TCT"))
    )
    (comp (ref "IC16")
      (value "MCP6042-I/MS")
      (footprint "eagle-import:MSOP-08")
      (libsource (lib "eagle-import") (part "MCP6042-I/MS"))
    )
    (comp (ref "IC17")
      (value "LTC1955_EUH")
      (footprint "eagle-import:QFN32")
      (libsource (lib "eagle-import") (part "LTC1955"))
    )
    (comp (ref "IC18")
      (value "AHC1G32_DC/GW/SE")
      (footprint "eagle-import:SC70-5,SOT353,TSSOP5")
      (libsource (lib "eagle-import") (part "AHC1G32"))
    )
    (comp (ref "IC19")
      (value "AHC1G08_DC/GW/SE")
      (footprint "eagle-import:SC70-5,SOT353,TSSOP5")
      (libsource (lib "eagle-import") (part "AHC1G08"))
    )
    (comp (ref "IC20")
      (value "AHC1G08_DC/GW/SE")
      (footprint "eagle-import:SC70-5,SOT353,TSSOP5")
      (libsource (lib "eagle-import") (part "AHC1G08"))
    )
    (comp (ref "IC21")
      (value "AHC1G32_DC/GW/SE")
      (footprint "eagle-import:SC70-5,SOT353,TSSOP5")
      (libsource (lib "eagle-import") (part "AHC1G32"))
    )
    (comp (ref "IC22")
      (value "AHC1G14_DC/GW/SE")
      (footprint "eagle-import:SC70-5,SOT353,TSSOP5")
      (libsource (lib "eagle-import") (part "AHC1G14"))
    )
    (comp (ref "IC23")
      (value "AHC1G14_DC/GW/SE")
      (footprint "eagle-import:SC70-5,SOT353,TSSOP5")
      (libsource (lib "eagle-import") (part "AHC1G14"))
    )
    (comp (ref "IC24")
      (value "LM75ADP")
      (footprint "eagle-import:TSSOP08-3")
      (libsource (lib "eagle-import") (part "LM75ADP"))
    )
    (comp (ref "IC25")
      (value "TPA3111D1PWP")
      (footprint "eagle-import:TSSOP28_EP")
      (fields (field (name "MANUFACTURER") "TI"))
      (libsource (lib "eagle-import") (part "IC_TI_TPA3111D1PWP"))
    )
    (comp (ref "IC26")
      (value "TPD2E001DZDR")
      (footprint "eagle-import:SOT-143")
      (libsource (lib "eagle-import") (part "SR05.TCT"))
    )
    (comp (ref "IC27")
      (value "TPD2E001DZDR")
      (footprint "eagle-import:SOT-143")
      (libsource (lib "eagle-import") (part "SR05.TCT"))
    )
    (comp (ref "IC28")
      (value "TPD2E001DZDR")
      (footprint "eagle-import:SOT-143")
      (libsource (lib "eagle-import") (part "SR05.TCT"))
    )
    (comp (ref "IC29")
      (value "AT97SC3205T-U3A1C20B")
      (footprint "eagle-import:TSSOP28")
      (fields (field (name "MANUFACTURER") "Microchip"))
      (libsource (lib "eagle-import") (part "AT97SC3205T-U3A1C20B"))
    )
    (comp (ref "IC30")
      (value "LT3580EMS8E")
      (footprint "eagle-import:MSOP8EXP")
      (libsource (lib "eagle-import") (part "LT3580EMS8E"))
    )
    (comp (ref "IC31")
      (value "SN65HVD12D")
      (footprint "eagle-import:SO08")
      (libsource (lib "eagle-import") (part "SN65HVD3082ED"))
    )
    (comp (ref "J1")
      (value "MA20-2-ICB-EXT")
      (footprint "eagle-import:MA20-2")
      (libsource (lib "eagle-import") (part "MA20-2-ICB-EXT"))
    )
    (comp (ref "J2")
      (value "CCM03-3504LFT-JK")
      (footprint "eagle-import:CCM03-3504LFT-JK")
      (libsource (lib "eagle-import") (part "CCM03-3504LFT-JK"))
    )
    (comp (ref "J3")
      (value "RJ8-8-90-DOWN")
      (footprint "eagle-import:RJ8-8-90-DOWN")
      (libsource (lib "eagle-import") (part "RJ8-8-90-DOWN"))
    )
    (comp (ref "J4")
      (value "RJ8-8-90-DOWN")
      (footprint "eagle-import:RJ8-8-90-DOWN")
      (libsource (lib "eagle-import") (part "RJ8-8-90-DOWN"))
    )
    (comp (ref "J5")
      (value "DF11-10DP-2DSA(01)")
      (footprint "eagle-import:DF11-10DP-2DSA")
      (libsource (lib "eagle-import") (part "DF11-10DP-2DSA(01)"))
    )
    (comp (ref "J6")
      (value "5220706")
      (footprint "eagle-import:5220706_1.LEFT")
      (libsource (lib "eagle-import") (part "5220706/1.LEFT"))
    )
    (comp (ref "J7")
      (value "3-641215-3")
      (footprint "eagle-import:3-641215-3")
      (libsource (lib "eagle-import") (part "3-641215-3"))
    )
    (comp (ref "J8")
      (value "3-641215-3")
      (footprint "eagle-import:3-641215-3")
      (libsource (lib "eagle-import") (part "3-641215-3"))
    )
    (comp (ref "J9")
      (value "5227110")
      (footprint "eagle-import:5227110_1.RIGHT")
      (libsource (lib "eagle-import") (part "5227110/1.RIGHT"))
    )
    (comp (ref "J10")
      (value "DNP-open-hole")
      (footprint "eagle-import:MA05-1")
      (libsource (lib "eagle-import") (part "MA05-1"))
    )
    (comp (ref "J11")
      (value "3-641215-2")
      (footprint "eagle-import:3-641215-2")
      (libsource (lib "eagle-import") (part "3-641215-2"))
    )
    (comp (ref "J12")
      (value "USB_B_90")
      (footprint "eagle-import:USB_B_90")
      (libsource (lib "eagle-import") (part "USB_B_90"))
    )
    (comp (ref "J13")
      (value "3-641215-2")
      (footprint "eagle-import:3-641215-2")
      (libsource (lib "eagle-import") (part "3-641215-2"))
    )
    (comp (ref "J14")
      (value "pin1x8")
      (footprint "eagle-import:MA08-1-MALE")
      (libsource (lib "eagle-import") (part "MA08-1-M"))
    )
    (comp (ref "J15")
      (value "MLW10G/T821106A1S")
      (footprint "eagle-import:MLW10-5X2-PRIMY")
      (libsource (lib "eagle-import") (part "MLW10G/T821106A1S"))
    )
    (comp (ref "J16")
      (value "3-641215-4")
      (footprint "eagle-import:3-641215-4")
      (libsource (lib "eagle-import") (part "3-641215-4"))
    )
    (comp (ref "J17")
      (value "DNP-open-hole")
      (footprint "eagle-import:MA05-1")
      (libsource (lib "eagle-import") (part "MA05-1"))
    )
    (comp (ref "J18")
      (value "3-641215-3")
      (footprint "eagle-import:3-641215-3")
      (libsource (lib "eagle-import") (part "3-641215-3"))
    )
    (comp (ref "J19")
      (value "796644-2(5mm)")
      (footprint "eagle-import:796644-2-5MM")
      (libsource (lib "eagle-import") (part "796644-2"))
    )
    (comp (ref "J20")
      (value "284512-2(3.5mm)")
      (footprint "eagle-import:284512-2-3,5MM")
      (libsource (lib "eagle-import") (part "284512-2"))
    )
    (comp (ref "J21")
      (value "4-641215-0")
      (footprint "eagle-import:4-641215-0")
      (libsource (lib "eagle-import") (part "4-641215-0"))
    )
    (comp (ref "J22")
      (value "3-641215-4")
      (footprint "eagle-import:3-641215-4")
      (libsource (lib "eagle-import") (part "3-641215-4"))
    )
    (comp (ref "J23")
      (value "MLW06G/T821106A1S")
      (footprint "eagle-import:MLW06-3X2-PRIMY")
      (libsource (lib "eagle-import") (part "MLW06G/T821106A1S"))
    )
    (comp (ref "JP1")
      (value "JP3CLOSE12")
      (footprint "eagle-import:JP3CLOSE12")
      (libsource (lib "eagle-import") (part "JP3CLOSE12"))
    )
    (comp (ref "JP2")
      (value "JP3CLOSE12")
      (footprint "eagle-import:JP3CLOSE12")
      (libsource (lib "eagle-import") (part "JP3CLOSE12"))
    )
    (comp (ref "L1")
      (value "HI1206T500R")
      (footprint "eagle-import:1206")
      (libsource (lib "eagle-import") (part "L-1206"))
    )
    (comp (ref "L2")
      (value "HI1206T500R")
      (footprint "eagle-import:1206")
      (libsource (lib "eagle-import") (part "L-1206"))
    )
    (comp (ref "L3")
      (value "NR6028T4R7M")
      (footprint "eagle-import:NR6028")
      (libsource (lib "eagle-import") (part "NR6028"))
    )
    (comp (ref "L4")
      (value "HI1206T500R")
      (footprint "eagle-import:1206")
      (libsource (lib "eagle-import") (part "L-1206"))
    )
    (comp (ref "L5")
      (value "HI1206T500R")
      (footprint "eagle-import:1206")
      (libsource (lib "eagle-import") (part "L-1206"))
    )
    (comp (ref "L6")
      (value "HI1206T500R")
      (footprint "eagle-import:1206")
      (libsource (lib "eagle-import") (part "L-1206"))
    )
    (comp (ref "L7")
      (value "HI1206T500R")
      (footprint "eagle-import:1206")
      (libsource (lib "eagle-import") (part "L-1206"))
    )
    (comp (ref "L8")
      (value "HI1206T500R")
      (footprint "eagle-import:1206")
      (libsource (lib "eagle-import") (part "L-1206"))
    )
    (comp (ref "L9")
      (value "NR6028T4R7M")
      (footprint "eagle-import:NR6028")
      (libsource (lib "eagle-import") (part "NR6028"))
    )
    (comp (ref "L10")
      (value "HI1206T500R")
      (footprint "eagle-import:1206")
      (libsource (lib "eagle-import") (part "L-1206"))
    )
    (comp (ref "L11")
      (value "HI1206T500R")
      (footprint "eagle-import:1206")
      (libsource (lib "eagle-import") (part "L-1206"))
    )
    (comp (ref "L12")
      (value "HI1206T500R")
      (footprint "eagle-import:1206")
      (libsource (lib "eagle-import") (part "L-1206"))
    )
    (comp (ref "L13")
      (value "HI1206T500R")
      (footprint "eagle-import:1206")
      (libsource (lib "eagle-import") (part "L-1206"))
    )
    (comp (ref "L14")
      (value "HI1812V101R-10")
      (footprint "eagle-import:L1812")
      (fields (field (name "MANUFACTURER") "Laird") (field (name "MFR_PN") "HI1812V101R-10"))
      (libsource (lib "eagle-import") (part "L1812"))
    )
    (comp (ref "L15")
      (value "HI1812V101R-10")
      (footprint "eagle-import:L1812")
      (fields (field (name "MANUFACTURER") "Laird") (field (name "MFR_PN") "HI1812V101R-10"))
      (libsource (lib "eagle-import") (part "L1812"))
    )
    (comp (ref "O1")
      (value "PIC-RPX")
      (footprint "eagle-import:TEMP-PAD")
      (libsource (lib "eagle-import") (part "PIC-RPX"))
    )
    (comp (ref "O2")
      (value "PIC-RPX")
      (footprint "eagle-import:TEMP-PAD")
      (libsource (lib "eagle-import") (part "PIC-RPX"))
    )
    (comp (ref "O3")
      (value "PIC-OUT")
      (footprint "eagle-import:TEMP-PAD")
      (libsource (lib "eagle-import") (part "PIC-OUT"))
    )
    (comp (ref "O4")
      (value "PIC-OUT")
      (footprint "eagle-import:TEMP-PAD")
      (libsource (lib "eagle-import") (part "PIC-OUT"))
    )
    (comp (ref "O5")
      (value "PIC-RPX")
      (footprint "eagle-import:TEMP-PAD")
      (libsource (lib "eagle-import") (part "PIC-RPX"))
    )
    (comp (ref "O6")
      (value "PIC-OUT")
      (footprint "eagle-import:TEMP-PAD")
      (libsource (lib "eagle-import") (part "PIC-OUT"))
    )
    (comp (ref "O7")
      (value "PIC-OUT")
      (footprint "eagle-import:TEMP-PAD")
      (libsource (lib "eagle-import") (part "PIC-OUT"))
    )
    (comp (ref "O8")
      (value "PIC-RPX")
      (footprint "eagle-import:TEMP-PAD")
      (libsource (lib "eagle-import") (part "PIC-RPX"))
    )
    (comp (ref "O9")
      (value "PIC-OUT")
      (footprint "eagle-import:TEMP-PAD")
      (libsource (lib "eagle-import") (part "PIC-OUT"))
    )
    (comp (ref "O10")
      (value "PIC-RPX")
      (footprint "eagle-import:TEMP-PAD")
      (libsource (lib "eagle-import") (part "PIC-RPX"))
    )
    (comp (ref "O11")
      (value "PIC-RPX")
      (footprint "eagle-import:TEMP-PAD")
      (libsource (lib "eagle-import") (part "PIC-RPX"))
    )
    (comp (ref "O12")
      (value "PIC-OUT")
      (footprint "eagle-import:TEMP-PAD")
      (libsource (lib "eagle-import") (part "PIC-OUT"))
    )
    (comp (ref "O13")
      (value "PIC-OUT")
      (footprint "eagle-import:TEMP-PAD")
      (libsource (lib "eagle-import") (part "PIC-OUT"))
    )
    (comp (ref "O14")
      (value "PIC-RPX")
      (footprint "eagle-import:TEMP-PAD")
      (libsource (lib "eagle-import") (part "PIC-RPX"))
    )
    (comp (ref "O15")
      (value "PIC-RPX")
      (footprint "eagle-import:TEMP-PAD")
      (libsource (lib "eagle-import") (part "PIC-RPX"))
    )
    (comp (ref "O16")
      (value "PIC-RPX")
      (footprint "eagle-import:TEMP-PAD")
      (libsource (lib "eagle-import") (part "PIC-RPX"))
    )
    (comp (ref "O17")
      (value "PIC-OUT")
      (footprint "eagle-import:TEMP-PAD")
      (libsource (lib "eagle-import") (part "PIC-OUT"))
    )
    (comp (ref "O18")
      (value "PIC-RPX")
      (footprint "eagle-import:TEMP-PAD")
      (libsource (lib "eagle-import") (part "PIC-RPX"))
    )
    (comp (ref "O19")
      (value "PIC-RPX")
      (footprint "eagle-import:TEMP-PAD")
      (libsource (lib "eagle-import") (part "PIC-RPX"))
    )
    (comp (ref "O20")
      (value "PIC-RPX")
      (footprint "eagle-import:TEMP-PAD")
      (libsource (lib "eagle-import") (part "PIC-RPX"))
    )
    (comp (ref "O21")
      (value "PIC-RPX")
      (footprint "eagle-import:TEMP-PAD")
      (libsource (lib "eagle-import") (part "PIC-RPX"))
    )
    (comp (ref "O22")
      (value "PIC-RPX")
      (footprint "eagle-import:TEMP-PAD")
      (libsource (lib "eagle-import") (part "PIC-RPX"))
    )
    (comp (ref "O23")
      (value "PIC-RPX")
      (footprint "eagle-import:TEMP-PAD")
      (libsource (lib "eagle-import") (part "PIC-RPX"))
    )
    (comp (ref "O24")
      (value "PIC-RPX")
      (footprint "eagle-import:TEMP-PAD")
      (libsource (lib "eagle-import") (part "PIC-RPX"))
    )
    (comp (ref "O25")
      (value "PIC-RPX")
      (footprint "eagle-import:TEMP-PAD")
      (libsource (lib "eagle-import") (part "PIC-RPX"))
    )
    (comp (ref "O26")
      (value "PIC-RPX")
      (footprint "eagle-import:TEMP-PAD")
      (libsource (lib "eagle-import") (part "PIC-RPX"))
    )
    (comp (ref "O27")
      (value "PIC-RPX")
      (footprint "eagle-import:TEMP-PAD")
      (libsource (lib "eagle-import") (part "PIC-RPX"))
    )
    (comp (ref "O28")
      (value "PIC-RPX")
      (footprint "eagle-import:TEMP-PAD")
      (libsource (lib "eagle-import") (part "PIC-RPX"))
    )
    (comp (ref "O29")
      (value "PIC-OUT")
      (footprint "eagle-import:TEMP-PAD")
      (libsource (lib "eagle-import") (part "PIC-OUT"))
    )
    (comp (ref "O30")
      (value "PIC-OUT")
      (footprint "eagle-import:TEMP-PAD")
      (libsource (lib "eagle-import") (part "PIC-OUT"))
    )
    (comp (ref "O31")
      (value "PIC-RPX")
      (footprint "eagle-import:TEMP-PAD")
      (libsource (lib "eagle-import") (part "PIC-RPX"))
    )
    (comp (ref "O32")
      (value "PIC-RPX")
      (footprint "eagle-import:TEMP-PAD")
      (libsource (lib "eagle-import") (part "PIC-RPX"))
    )
    (comp (ref "O33")
      (value "PIC-RPX")
      (footprint "eagle-import:TEMP-PAD")
      (libsource (lib "eagle-import") (part "PIC-RPX"))
    )
    (comp (ref "O35")
      (value "PIC-RPX")
      (footprint "eagle-import:TEMP-PAD")
      (libsource (lib "eagle-import") (part "PIC-RPX"))
    )
    (comp (ref "O39")
      (value "PIC-OUT")
      (footprint "eagle-import:TEMP-PAD")
      (libsource (lib "eagle-import") (part "PIC-OUT"))
    )
    (comp (ref "O40")
      (value "PIC-OUT")
      (footprint "eagle-import:TEMP-PAD")
      (libsource (lib "eagle-import") (part "PIC-OUT"))
    )
    (comp (ref "O53")
      (value "PIC-RPX")
      (footprint "eagle-import:TEMP-PAD")
      (libsource (lib "eagle-import") (part "PIC-RPX"))
    )
    (comp (ref "O55")
      (value "PIC-OUT")
      (footprint "eagle-import:TEMP-PAD")
      (libsource (lib "eagle-import") (part "PIC-OUT"))
    )
    (comp (ref "O58")
      (value "PIC-OUT")
      (footprint "eagle-import:TEMP-PAD")
      (libsource (lib "eagle-import") (part "PIC-OUT"))
    )
    (comp (ref "O59")
      (value "PIC-RPX")
      (footprint "eagle-import:TEMP-PAD")
      (libsource (lib "eagle-import") (part "PIC-RPX"))
    )
    (comp (ref "O60")
      (value "PIC-RPX")
      (footprint "eagle-import:TEMP-PAD")
      (libsource (lib "eagle-import") (part "PIC-RPX"))
    )
    (comp (ref "PCB1")
      (value "PCB-ICBE")
      (footprint "eagle-import:PCB-ICBE")
      (libsource (lib "eagle-import") (part "PCB-ICBE"))
    )
    (comp (ref "PCB2")
      (value "DNP-PCB-ICB")
      (footprint "eagle-import:PCB-ICB")
      (libsource (lib "eagle-import") (part "PCB-ICB"))
    )
    (comp (ref "PCB3")
      (value "DNP-PCB-BT")
      (footprint "eagle-import:BT_MODULE_BRD")
      (libsource (lib "eagle-import") (part "BT_PCBBRD"))
    )
    (comp (ref "Q1")
      (value "SSM6P49NU,LFPZ")
      (footprint "eagle-import:MICRO_FET")
      (libsource (lib "eagle-import") (part "SSM6P49PZNU,LF"))
    )
    (comp (ref "Q2")
      (value "SSM6P49NU,LFPZ")
      (footprint "eagle-import:MICRO_FET")
      (libsource (lib "eagle-import") (part "SSM6P49PZNU,LF"))
    )
    (comp (ref "Q3")
      (value "Si3421DV")
      (footprint "eagle-import:SSOT-6")
      (libsource (lib "eagle-import") (part "FDC658AP"))
    )
    (comp (ref "Q4")
      (value "FDG6303N")
      (footprint "eagle-import:SC70-6")
      (libsource (lib "eagle-import") (part "FDG6303N"))
    )
    (comp (ref "Q5")
      (value "Si3421DV")
      (footprint "eagle-import:SSOT-6")
      (libsource (lib "eagle-import") (part "FDC658AP"))
    )
    (comp (ref "Q6")
      (value "FDG6303N")
      (footprint "eagle-import:SC70-6")
      (libsource (lib "eagle-import") (part "FDG6303N"))
    )
    (comp (ref "Q7")
      (value "Si3421DV")
      (footprint "eagle-import:SSOT-6")
      (libsource (lib "eagle-import") (part "FDC658AP"))
    )
    (comp (ref "Q8")
      (value "Si3421DV")
      (footprint "eagle-import:SSOT-6")
      (libsource (lib "eagle-import") (part "FDC658AP"))
    )
    (comp (ref "Q9")
      (value "FDG6303N")
      (footprint "eagle-import:SC70-6")
      (libsource (lib "eagle-import") (part "FDG6303N"))
    )
    (comp (ref "Q10")
      (value "FDG6303N")
      (footprint "eagle-import:SC70-6")
      (libsource (lib "eagle-import") (part "FDG6303N"))
    )
    (comp (ref "Q11")
      (value "FDG6303N")
      (footprint "eagle-import:SC70-6")
      (libsource (lib "eagle-import") (part "FDG6303N"))
    )
    (comp (ref "Q12")
      (value "Si3421DV")
      (footprint "eagle-import:SSOT-6")
      (libsource (lib "eagle-import") (part "FDC658AP"))
    )
    (comp (ref "Q13")
      (value "SSM6P49NU,LFPZ")
      (footprint "eagle-import:MICRO_FET")
      (libsource (lib "eagle-import") (part "SSM6P49PZNU,LF"))
    )
    (comp (ref "R1")
      (value "300k")
      (footprint "eagle-import:0603")
      (libsource (lib "eagle-import") (part "R-0603"))
    )
    (comp (ref "R2")
      (value "0R")
      (footprint "eagle-import:0603")
      (libsource (lib "eagle-import") (part "R-0603"))
    )
    (comp (ref "R3")
      (value "100R")
      (footprint "eagle-import:0603")
      (libsource (lib "eagle-import") (part "R-0603"))
    )
    (comp (ref "R4")
      (value "10R")
      (footprint "eagle-import:0603")
      (libsource (lib "eagle-import") (part "R-0603"))
    )
    (comp (ref "R5")
      (value "100k")
      (footprint "eagle-import:0603")
      (libsource (lib "eagle-import") (part "R-0603"))
    )
    (comp (ref "R6")
      (value "100k")
      (footprint "eagle-import:0603")
      (libsource (lib "eagle-import") (part "R-0603"))
    )
    (comp (ref "R7")
      (value "100k")
      (footprint "eagle-import:0603")
      (libsource (lib "eagle-import") (part "R-0603"))
    )
    (comp (ref "R8")
      (value "100k")
      (footprint "eagle-import:0603")
      (libsource (lib "eagle-import") (part "R-0603"))
    )
    (comp (ref "R9")
      (value "100k")
      (footprint "eagle-import:0603")
      (libsource (lib "eagle-import") (part "R-0603"))
    )
    (comp (ref "R10")
      (value "1M")
      (footprint "eagle-import:0603")
      (libsource (lib "eagle-import") (part "R-0603"))
    )
    (comp (ref "R11")
      (value "1M")
      (footprint "eagle-import:0603")
      (libsource (lib "eagle-import") (part "R-0603"))
    )
    (comp (ref "R12")
      (value "300k")
      (footprint "eagle-import:0603")
      (libsource (lib "eagle-import") (part "R-0603"))
    )
    (comp (ref "R13")
      (value "1M")
      (footprint "eagle-import:0603")
      (libsource (lib "eagle-import") (part "R-0603"))
    )
    (comp (ref "R14")
      (value "1M")
      (footprint "eagle-import:0603")
      (libsource (lib "eagle-import") (part "R-0603"))
    )
    (comp (ref "R15")
      (value "300k")
      (footprint "eagle-import:0603")
      (libsource (lib "eagle-import") (part "R-0603"))
    )
    (comp (ref "R16")
      (value "1M")
      (footprint "eagle-import:0603")
      (libsource (lib "eagle-import") (part "R-0603"))
    )
    (comp (ref "R17")
      (value "47k")
      (footprint "eagle-import:0603")
      (libsource (lib "eagle-import") (part "R-0603"))
    )
    (comp (ref "R18")
      (value "10k")
      (footprint "eagle-import:0603")
      (libsource (lib "eagle-import") (part "R-0603"))
    )
    (comp (ref "R19")
      (value "560k")
      (footprint "eagle-import:0603")
      (libsource (lib "eagle-import") (part "R-0603"))
    )
    (comp (ref "R20")
      (value "1M")
      (footprint "eagle-import:0603")
      (libsource (lib "eagle-import") (part "R-0603"))
    )
    (comp (ref "R21")
      (value "1M")
      (footprint "eagle-import:0603")
      (libsource (lib "eagle-import") (part "R-0603"))
    )
    (comp (ref "R22")
      (value "4M99")
      (footprint "eagle-import:0603")
      (libsource (lib "eagle-import") (part "R-0603"))
    )
    (comp (ref "R23")
      (value "1M")
      (footprint "eagle-import:0603")
      (libsource (lib "eagle-import") (part "R-0603"))
    )
    (comp (ref "R24")
      (value "100k")
      (footprint "eagle-import:0603")
      (libsource (lib "eagle-import") (part "R-0603"))
    )
    (comp (ref "R25")
      (value "1M")
      (footprint "eagle-import:0603")
      (libsource (lib "eagle-import") (part "R-0603"))
    )
    (comp (ref "R26")
      (value "10k")
      (footprint "eagle-import:0603")
      (libsource (lib "eagle-import") (part "R-0603"))
    )
    (comp (ref "R27")
      (value "10k")
      (footprint "eagle-import:0603")
      (libsource (lib "eagle-import") (part "R-0603"))
    )
    (comp (ref "R28")
      (value "100R")
      (footprint "eagle-import:0603")
      (libsource (lib "eagle-import") (part "R-0603"))
    )
    (comp (ref "R29")
      (value "300R")
      (footprint "eagle-import:0603")
      (libsource (lib "eagle-import") (part "R-0603"))
    )
    (comp (ref "R30")
      (value "10k")
      (footprint "eagle-import:0603")
      (libsource (lib "eagle-import") (part "R-0603"))
    )
    (comp (ref "R31")
      (value "1M")
      (footprint "eagle-import:0603")
      (libsource (lib "eagle-import") (part "R-0603"))
    )
    (comp (ref "R32")
      (value "1M")
      (footprint "eagle-import:0603")
      (libsource (lib "eagle-import") (part "R-0603"))
    )
    (comp (ref "R33")
      (value "1M")
      (footprint "eagle-import:0603")
      (libsource (lib "eagle-import") (part "R-0603"))
    )
    (comp (ref "R34")
      (value "1M")
      (footprint "eagle-import:0603")
      (libsource (lib "eagle-import") (part "R-0603"))
    )
    (comp (ref "R35")
      (value "0.025R")
      (footprint "eagle-import:0805")
      (libsource (lib "eagle-import") (part "R-0805"))
    )
    (comp (ref "R36")
      (value "1k")
      (footprint "eagle-import:0603")
      (libsource (lib "eagle-import") (part "R-0603"))
    )
    (comp (ref "R37")
      (value "0.025R")
      (footprint "eagle-import:0805")
      (libsource (lib "eagle-import") (part "R-0805"))
    )
    (comp (ref "R38")
      (value "1R")
      (footprint "eagle-import:0805")
      (libsource (lib "eagle-import") (part "R-0805"))
    )
    (comp (ref "R39")
      (value "0.025R")
      (footprint "eagle-import:0805")
      (libsource (lib "eagle-import") (part "R-0805"))
    )
    (comp (ref "R40")
      (value "300k")
      (footprint "eagle-import:0603")
      (libsource (lib "eagle-import") (part "R-0603"))
    )
    (comp (ref "R41")
      (value "300k")
      (footprint "eagle-import:0603")
      (libsource (lib "eagle-import") (part "R-0603"))
    )
    (comp (ref "R42")
      (value "1M")
      (footprint "eagle-import:0603")
      (libsource (lib "eagle-import") (part "R-0603"))
    )
    (comp (ref "R43")
      (value "300k")
      (footprint "eagle-import:0603")
      (libsource (lib "eagle-import") (part "R-0603"))
    )
    (comp (ref "R44")
      (value "300k")
      (footprint "eagle-import:0603")
      (libsource (lib "eagle-import") (part "R-0603"))
    )
    (comp (ref "R45")
      (value "1M")
      (footprint "eagle-import:0603")
      (libsource (lib "eagle-import") (part "R-0603"))
    )
    (comp (ref "R46")
      (value "150k")
      (footprint "eagle-import:0603")
      (libsource (lib "eagle-import") (part "R-0603"))
    )
    (comp (ref "R47")
      (value "47k")
      (footprint "eagle-import:0603")
      (libsource (lib "eagle-import") (part "R-0603"))
    )
    (comp (ref "R48")
      (value "1M")
      (footprint "eagle-import:0603")
      (libsource (lib "eagle-import") (part "R-0603"))
    )
    (comp (ref "R49")
      (value "560k")
      (footprint "eagle-import:0603")
      (libsource (lib "eagle-import") (part "R-0603"))
    )
    (comp (ref "R50")
      (value "100k")
      (footprint "eagle-import:0603")
      (libsource (lib "eagle-import") (part "R-0603"))
    )
    (comp (ref "R51")
      (value "1M")
      (footprint "eagle-import:0603")
      (libsource (lib "eagle-import") (part "R-0603"))
    )
    (comp (ref "R52")
      (value "1R")
      (footprint "eagle-import:0805")
      (libsource (lib "eagle-import") (part "R-0805"))
    )
    (comp (ref "R53")
      (value "10k")
      (footprint "eagle-import:0603")
      (libsource (lib "eagle-import") (part "R-0603"))
    )
    (comp (ref "R54")
      (value "300k")
      (footprint "eagle-import:0603")
      (libsource (lib "eagle-import") (part "R-0603"))
    )
    (comp (ref "R55")
      (value "100k")
      (footprint "eagle-import:0603")
      (libsource (lib "eagle-import") (part "R-0603"))
    )
    (comp (ref "R56")
      (value "100k")
      (footprint "eagle-import:0603")
      (libsource (lib "eagle-import") (part "R-0603"))
    )
    (comp (ref "R57")
      (value "100k")
      (footprint "eagle-import:0603")
      (libsource (lib "eagle-import") (part "R-0603"))
    )
    (comp (ref "R58")
      (value "10k")
      (footprint "eagle-import:0603")
      (libsource (lib "eagle-import") (part "R-0603"))
    )
    (comp (ref "R59")
      (value "10k")
      (footprint "eagle-import:0603")
      (libsource (lib "eagle-import") (part "R-0603"))
    )
    (comp (ref "R60")
      (value "10k")
      (footprint "eagle-import:0603")
      (libsource (lib "eagle-import") (part "R-0603"))
    )
    (comp (ref "R61")
      (value "100R")
      (footprint "eagle-import:0603")
      (libsource (lib "eagle-import") (part "R-0603"))
    )
    (comp (ref "R62")
      (value "2k2")
      (footprint "eagle-import:0603")
      (libsource (lib "eagle-import") (part "R-0603"))
    )
    (comp (ref "R63")
      (value "1k")
      (footprint "eagle-import:0603")
      (libsource (lib "eagle-import") (part "R-0603"))
    )
    (comp (ref "R64")
      (value "300k")
      (footprint "eagle-import:0603")
      (libsource (lib "eagle-import") (part "R-0603"))
    )
    (comp (ref "R65")
      (value "1M")
      (footprint "eagle-import:0603")
      (libsource (lib "eagle-import") (part "R-0603"))
    )
    (comp (ref "R66")
      (value "1k")
      (footprint "eagle-import:0603")
      (libsource (lib "eagle-import") (part "R-0603"))
    )
    (comp (ref "R67")
      (value "1k")
      (footprint "eagle-import:0603")
      (libsource (lib "eagle-import") (part "R-0603"))
    )
    (comp (ref "R68")
      (value "1k")
      (footprint "eagle-import:0603")
      (libsource (lib "eagle-import") (part "R-0603"))
    )
    (comp (ref "R69")
      (value "1k")
      (footprint "eagle-import:0603")
      (libsource (lib "eagle-import") (part "R-0603"))
    )
    (comp (ref "R70")
      (value "1M")
      (footprint "eagle-import:0603")
      (libsource (lib "eagle-import") (part "R-0603"))
    )
    (comp (ref "R71")
      (value "10k")
      (footprint "eagle-import:0603")
      (libsource (lib "eagle-import") (part "R-0603"))
    )
    (comp (ref "R72")
      (value "100k")
      (footprint "eagle-import:0603")
      (libsource (lib "eagle-import") (part "R-0603"))
    )
    (comp (ref "R73")
      (value "2k2")
      (footprint "eagle-import:0603")
      (libsource (lib "eagle-import") (part "R-0603"))
    )
    (comp (ref "R74")
      (value "1k")
      (footprint "eagle-import:0603")
      (libsource (lib "eagle-import") (part "R-0603"))
    )
    (comp (ref "R75")
      (value "10k")
      (footprint "eagle-import:0603")
      (libsource (lib "eagle-import") (part "R-0603"))
    )
    (comp (ref "R76")
      (value "300k")
      (footprint "eagle-import:0603")
      (libsource (lib "eagle-import") (part "R-0603"))
    )
    (comp (ref "R77")
      (value "47k")
      (footprint "eagle-import:0603")
      (libsource (lib "eagle-import") (part "R-0603"))
    )
    (comp (ref "R78")
      (value "100R")
      (footprint "eagle-import:0603")
      (libsource (lib "eagle-import") (part "R-0603"))
    )
    (comp (ref "R79")
      (value "100R")
      (footprint "eagle-import:0603")
      (libsource (lib "eagle-import") (part "R-0603"))
    )
    (comp (ref "R80")
      (value "100R")
      (footprint "eagle-import:0603")
      (libsource (lib "eagle-import") (part "R-0603"))
    )
    (comp (ref "R81")
      (value "100R")
      (footprint "eagle-import:0603")
      (libsource (lib "eagle-import") (part "R-0603"))
    )
    (comp (ref "R82")
      (value "100k")
      (footprint "eagle-import:0603")
      (libsource (lib "eagle-import") (part "R-0603"))
    )
    (comp (ref "R83")
      (value "1M")
      (footprint "eagle-import:0603")
      (libsource (lib "eagle-import") (part "R-0603"))
    )
    (comp (ref "R84")
      (value "300k")
      (footprint "eagle-import:0603")
      (libsource (lib "eagle-import") (part "R-0603"))
    )
    (comp (ref "R85")
      (value "1M")
      (footprint "eagle-import:0603")
      (libsource (lib "eagle-import") (part "R-0603"))
    )
    (comp (ref "R86")
      (value "1k")
      (footprint "eagle-import:0603")
      (libsource (lib "eagle-import") (part "R-0603"))
    )
    (comp (ref "R87")
      (value "1k")
      (footprint "eagle-import:0603")
      (libsource (lib "eagle-import") (part "R-0603"))
    )
    (comp (ref "R88")
      (value "1M")
      (footprint "eagle-import:0603")
      (libsource (lib "eagle-import") (part "R-0603"))
    )
    (comp (ref "R89")
      (value "1M")
      (footprint "eagle-import:0603")
      (libsource (lib "eagle-import") (part "R-0603"))
    )
    (comp (ref "R90")
      (value "1k")
      (footprint "eagle-import:0603")
      (libsource (lib "eagle-import") (part "R-0603"))
    )
    (comp (ref "R91")
      (value "10k")
      (footprint "eagle-import:0603")
      (libsource (lib "eagle-import") (part "R-0603"))
    )
    (comp (ref "R92")
      (value "10R")
      (footprint "eagle-import:0603")
      (libsource (lib "eagle-import") (part "R-0603"))
    )
    (comp (ref "R93")
      (value "300R")
      (footprint "eagle-import:0603")
      (libsource (lib "eagle-import") (part "R-0603"))
    )
    (comp (ref "R94")
      (value "180k")
      (footprint "eagle-import:0603")
      (libsource (lib "eagle-import") (part "R-0603"))
    )
    (comp (ref "R95")
      (value "4M99")
      (footprint "eagle-import:0603")
      (libsource (lib "eagle-import") (part "R-0603"))
    )
    (comp (ref "R96")
      (value "560k")
      (footprint "eagle-import:0603")
      (libsource (lib "eagle-import") (part "R-0603"))
    )
    (comp (ref "R97")
      (value "180k")
      (footprint "eagle-import:0603")
      (libsource (lib "eagle-import") (part "R-0603"))
    )
    (comp (ref "R98")
      (value "4M99")
      (footprint "eagle-import:0603")
      (libsource (lib "eagle-import") (part "R-0603"))
    )
    (comp (ref "R99")
      (value "560k")
      (footprint "eagle-import:0603")
      (libsource (lib "eagle-import") (part "R-0603"))
    )
    (comp (ref "R100")
      (value "2k2")
      (footprint "eagle-import:0603")
      (libsource (lib "eagle-import") (part "R-0603"))
    )
    (comp (ref "R101")
      (value "2k2")
      (footprint "eagle-import:0603")
      (libsource (lib "eagle-import") (part "R-0603"))
    )
    (comp (ref "R102")
      (value "1k")
      (footprint "eagle-import:0603")
      (libsource (lib "eagle-import") (part "R-0603"))
    )
    (comp (ref "R103")
      (value "300R")
      (footprint "eagle-import:0603")
      (libsource (lib "eagle-import") (part "R-0603"))
    )
    (comp (ref "R104")
      (value "10k")
      (footprint "eagle-import:0603")
      (libsource (lib "eagle-import") (part "R-0603"))
    )
    (comp (ref "R105")
      (value "1R")
      (footprint "eagle-import:0805")
      (libsource (lib "eagle-import") (part "R-0805"))
    )
    (comp (ref "R106")
      (value "1R")
      (footprint "eagle-import:0805")
      (libsource (lib "eagle-import") (part "R-0805"))
    )
    (comp (ref "R107")
      (value "10k")
      (footprint "eagle-import:0603")
      (libsource (lib "eagle-import") (part "R-0603"))
    )
    (comp (ref "R108")
      (value "100R")
      (footprint "eagle-import:0603")
      (libsource (lib "eagle-import") (part "R-0603"))
    )
    (comp (ref "R109")
      (value "100R")
      (footprint "eagle-import:0603")
      (libsource (lib "eagle-import") (part "R-0603"))
    )
    (comp (ref "R110")
      (value "10k")
      (footprint "eagle-import:0603")
      (libsource (lib "eagle-import") (part "R-0603"))
    )
    (comp (ref "R111")
      (value "10k")
      (footprint "eagle-import:0603")
      (libsource (lib "eagle-import") (part "R-0603"))
    )
    (comp (ref "R112")
      (value "1k")
      (footprint "eagle-import:0603")
      (libsource (lib "eagle-import") (part "R-0603"))
    )
    (comp (ref "R113")
      (value "1k")
      (footprint "eagle-import:0603")
      (libsource (lib "eagle-import") (part "R-0603"))
    )
    (comp (ref "R114")
      (value "1R")
      (footprint "eagle-import:0805")
      (libsource (lib "eagle-import") (part "R-0805"))
    )
    (comp (ref "R115")
      (value "1R")
      (footprint "eagle-import:0805")
      (libsource (lib "eagle-import") (part "R-0805"))
    )
    (comp (ref "R116")
      (value "100R")
      (footprint "eagle-import:0603")
      (libsource (lib "eagle-import") (part "R-0603"))
    )
    (comp (ref "R117")
      (value "100R")
      (footprint "eagle-import:0603")
      (libsource (lib "eagle-import") (part "R-0603"))
    )
    (comp (ref "R118")
      (value "2k2")
      (footprint "eagle-import:0603")
      (libsource (lib "eagle-import") (part "R-0603"))
    )
    (comp (ref "R119")
      (value "100R")
      (footprint "eagle-import:0603")
      (libsource (lib "eagle-import") (part "R-0603"))
    )
    (comp (ref "R120")
      (value "10k")
      (footprint "eagle-import:0603")
      (libsource (lib "eagle-import") (part "R-0603"))
    )
    (comp (ref "R121")
      (value "300k")
      (footprint "eagle-import:0603")
      (libsource (lib "eagle-import") (part "R-0603"))
    )
    (comp (ref "R122")
      (value "1k")
      (footprint "eagle-import:0603")
      (libsource (lib "eagle-import") (part "R-0603"))
    )
    (comp (ref "R123")
      (value "1k")
      (footprint "eagle-import:0603")
      (libsource (lib "eagle-import") (part "R-0603"))
    )
    (comp (ref "R124")
      (value "1k")
      (footprint "eagle-import:0603")
      (libsource (lib "eagle-import") (part "R-0603"))
    )
    (comp (ref "R125")
      (value "100k")
      (footprint "eagle-import:0603")
      (libsource (lib "eagle-import") (part "R-0603"))
    )
    (comp (ref "R126")
      (value "1M")
      (footprint "eagle-import:0603")
      (libsource (lib "eagle-import") (part "R-0603"))
    )
    (comp (ref "R127")
      (value "1R")
      (footprint "eagle-import:0805")
      (libsource (lib "eagle-import") (part "R-0805"))
    )
    (comp (ref "R128")
      (value "10k")
      (footprint "eagle-import:0603")
      (libsource (lib "eagle-import") (part "R-0603"))
    )
    (comp (ref "R129")
      (value "0R")
      (footprint "eagle-import:0603")
      (libsource (lib "eagle-import") (part "R-0603"))
    )
    (comp (ref "R130")
      (value "10k")
      (footprint "eagle-import:0603")
      (libsource (lib "eagle-import") (part "R-0603"))
    )
    (comp (ref "R131")
      (value "10k")
      (footprint "eagle-import:0603")
      (libsource (lib "eagle-import") (part "R-0603"))
    )
    (comp (ref "R132")
      (value "100R")
      (footprint "eagle-import:0603")
      (libsource (lib "eagle-import") (part "R-0603"))
    )
    (comp (ref "R133")
      (value "261k")
      (footprint "eagle-import:0603")
      (libsource (lib "eagle-import") (part "R-0603"))
    )
    (comp (ref "R134")
      (value "62k")
      (footprint "eagle-import:0603")
      (libsource (lib "eagle-import") (part "R-0603"))
    )
    (comp (ref "R135")
      (value "10k")
      (footprint "eagle-import:0603")
      (libsource (lib "eagle-import") (part "R-0603"))
    )
    (comp (ref "R136")
      (value "47k")
      (footprint "eagle-import:0603")
      (libsource (lib "eagle-import") (part "R-0603"))
    )
    (comp (ref "R137")
      (value "10k")
      (footprint "eagle-import:0603")
      (libsource (lib "eagle-import") (part "R-0603"))
    )
    (comp (ref "R138")
      (value "1M")
      (footprint "eagle-import:0603")
      (libsource (lib "eagle-import") (part "R-0603"))
    )
    (comp (ref "R139")
      (value "1M")
      (footprint "eagle-import:0603")
      (libsource (lib "eagle-import") (part "R-0603"))
    )
    (comp (ref "R140")
      (value "300k")
      (footprint "eagle-import:0603")
      (libsource (lib "eagle-import") (part "R-0603"))
    )
    (comp (ref "R141")
      (value "10k")
      (footprint "eagle-import:0603")
      (libsource (lib "eagle-import") (part "R-0603"))
    )
    (comp (ref "R142")
      (value "100k")
      (footprint "eagle-import:0603")
      (libsource (lib "eagle-import") (part "R-0603"))
    )
    (comp (ref "R143")
      (value "1R")
      (footprint "eagle-import:0805")
      (libsource (lib "eagle-import") (part "R-0805"))
    )
    (comp (ref "R144")
      (value "1M")
      (footprint "eagle-import:0603")
      (libsource (lib "eagle-import") (part "R-0603"))
    )
    (comp (ref "R145")
      (value "1M")
      (footprint "eagle-import:0603")
      (libsource (lib "eagle-import") (part "R-0603"))
    )
    (comp (ref "R146")
      (value "1M")
      (footprint "eagle-import:0603")
      (libsource (lib "eagle-import") (part "R-0603"))
    )
    (comp (ref "R147")
      (value "10k")
      (footprint "eagle-import:0603")
      (libsource (lib "eagle-import") (part "R-0603"))
    )
    (comp (ref "R148")
      (value "10k")
      (footprint "eagle-import:0603")
      (libsource (lib "eagle-import") (part "R-0603"))
    )
    (comp (ref "R149")
      (value "100k")
      (footprint "eagle-import:0603")
      (libsource (lib "eagle-import") (part "R-0603"))
    )
    (comp (ref "R150")
      (value "100k")
      (footprint "eagle-import:0603")
      (libsource (lib "eagle-import") (part "R-0603"))
    )
    (comp (ref "R151")
      (value "100R")
      (footprint "eagle-import:0603")
      (libsource (lib "eagle-import") (part "R-0603"))
    )
    (comp (ref "R152")
      (value "100R")
      (footprint "eagle-import:0603")
      (libsource (lib "eagle-import") (part "R-0603"))
    )
    (comp (ref "R153")
      (value "100R")
      (footprint "eagle-import:0603")
      (libsource (lib "eagle-import") (part "R-0603"))
    )
    (comp (ref "R154")
      (value "100R")
      (footprint "eagle-import:0603")
      (libsource (lib "eagle-import") (part "R-0603"))
    )
    (comp (ref "REF1")
      (value "REF")
      (footprint "eagle-import:REF")
      (libsource (lib "eagle-import") (part "REF"))
    )
    (comp (ref "REF2")
      (value "REF")
      (footprint "eagle-import:REF")
      (libsource (lib "eagle-import") (part "REF"))
    )
    (comp (ref "T1")
      (value "PIC-RPX")
      (footprint "eagle-import:TEMP-PAD")
      (libsource (lib "eagle-import") (part "PIC-RPX"))
    )
    (comp (ref "T2")
      (value "PIC-OUT")
      (footprint "eagle-import:TEMP-PAD")
      (libsource (lib "eagle-import") (part "PIC-OUT"))
    )
    (comp (ref "T3")
      (value "PIC-RPX")
      (footprint "eagle-import:TEMP-PAD")
      (libsource (lib "eagle-import") (part "PIC-RPX"))
    )
    (comp (ref "T4")
      (value "PIC-OUT")
      (footprint "eagle-import:TEMP-PAD")
      (libsource (lib "eagle-import") (part "PIC-OUT"))
    )
    (comp (ref "T5")
      (value "PIC-RPX")
      (footprint "eagle-import:TEMP-PAD")
      (libsource (lib "eagle-import") (part "PIC-RPX"))
    )
    (comp (ref "T6")
      (value "PIC-RPX")
      (footprint "eagle-import:TEMP-PAD")
      (libsource (lib "eagle-import") (part "PIC-RPX"))
    )
    (comp (ref "T7")
      (value "PIC-OUT")
      (footprint "eagle-import:TEMP-PAD")
      (libsource (lib "eagle-import") (part "PIC-OUT"))
    )
    (comp (ref "T8")
      (value "PIC-RPX")
      (footprint "eagle-import:TEMP-PAD")
      (libsource (lib "eagle-import") (part "PIC-RPX"))
    )
    (comp (ref "T9")
      (value "PIC-RPX")
      (footprint "eagle-import:TEMP-PAD")
      (libsource (lib "eagle-import") (part "PIC-RPX"))
    )
    (comp (ref "T10")
      (value "PIC-RPX")
      (footprint "eagle-import:TEMP-PAD")
      (libsource (lib "eagle-import") (part "PIC-RPX"))
    )
    (comp (ref "T11")
      (value "PIC-OUT")
      (footprint "eagle-import:TEMP-PAD")
      (libsource (lib "eagle-import") (part "PIC-OUT"))
    )
    (comp (ref "T12")
      (value "PIC-RPX")
      (footprint "eagle-import:TEMP-PAD")
      (libsource (lib "eagle-import") (part "PIC-RPX"))
    )
    (comp (ref "T16")
      (value "PIC-RPX")
      (footprint "eagle-import:TEMP-PAD")
      (libsource (lib "eagle-import") (part "PIC-RPX"))
    )
    (comp (ref "T17")
      (value "PIC-OUT")
      (footprint "eagle-import:TEMP-PAD")
      (libsource (lib "eagle-import") (part "PIC-OUT"))
    )
    (comp (ref "T18")
      (value "PIC-OUT")
      (footprint "eagle-import:TEMP-PAD")
      (libsource (lib "eagle-import") (part "PIC-OUT"))
    )
    (comp (ref "T19")
      (value "PIC-RPX")
      (footprint "eagle-import:TEMP-PAD")
      (libsource (lib "eagle-import") (part "PIC-RPX"))
    )
    (comp (ref "T20")
      (value "PIC-OUT")
      (footprint "eagle-import:TEMP-PAD")
      (libsource (lib "eagle-import") (part "PIC-OUT"))
    )
    (comp (ref "T21")
      (value "PIC-RPX")
      (footprint "eagle-import:TEMP-PAD")
      (libsource (lib "eagle-import") (part "PIC-RPX"))
    )
    (comp (ref "T23")
      (value "PIC-OUT")
      (footprint "eagle-import:TEMP-PAD")
      (libsource (lib "eagle-import") (part "PIC-OUT"))
    )
    (comp (ref "T24")
      (value "PIC-OUT")
      (footprint "eagle-import:TEMP-PAD")
      (libsource (lib "eagle-import") (part "PIC-OUT"))
    )
    (comp (ref "T25")
      (value "PIC-OUT")
      (footprint "eagle-import:TEMP-PAD")
      (libsource (lib "eagle-import") (part "PIC-OUT"))
    )
    (comp (ref "T26")
      (value "PIC-RPX")
      (footprint "eagle-import:TEMP-PAD")
      (libsource (lib "eagle-import") (part "PIC-RPX"))
    )
    (comp (ref "T28")
      (value "PIC-RPX")
      (footprint "eagle-import:TEMP-PAD")
      (libsource (lib "eagle-import") (part "PIC-RPX"))
    )
    (comp (ref "T29")
      (value "PIC-OUT")
      (footprint "eagle-import:TEMP-PAD")
      (libsource (lib "eagle-import") (part "PIC-OUT"))
    )
    (comp (ref "T30")
      (value "PIC-OUT")
      (footprint "eagle-import:TEMP-PAD")
      (libsource (lib "eagle-import") (part "PIC-OUT"))
    )
    (comp (ref "T31")
      (value "PIC-RPX")
      (footprint "eagle-import:TEMP-PAD")
      (libsource (lib "eagle-import") (part "PIC-RPX"))
    )
    (comp (ref "T34")
      (value "PIC-RPX")
      (footprint "eagle-import:TEMP-PAD")
      (libsource (lib "eagle-import") (part "PIC-RPX"))
    )
    (comp (ref "T35")
      (value "PIC-OUT")
      (footprint "eagle-import:TEMP-PAD")
      (libsource (lib "eagle-import") (part "PIC-OUT"))
    )
    (comp (ref "T45")
      (value "PIC-RPX")
      (footprint "eagle-import:TEMP-PAD")
      (libsource (lib "eagle-import") (part "PIC-RPX"))
    )
    (comp (ref "T46")
      (value "PIC-OUT")
      (footprint "eagle-import:TEMP-PAD")
      (libsource (lib "eagle-import") (part "PIC-OUT"))
    )
    (comp (ref "T47")
      (value "PIC-OUT")
      (footprint "eagle-import:TEMP-PAD")
      (libsource (lib "eagle-import") (part "PIC-OUT"))
    )
    (comp (ref "T48")
      (value "PIC-RPX")
      (footprint "eagle-import:TEMP-PAD")
      (libsource (lib "eagle-import") (part "PIC-RPX"))
    )
    (comp (ref "T49")
      (value "PIC-OUT")
      (footprint "eagle-import:TEMP-PAD")
      (libsource (lib "eagle-import") (part "PIC-OUT"))
    )
    (comp (ref "T50")
      (value "PIC-RPX")
      (footprint "eagle-import:TEMP-PAD")
      (libsource (lib "eagle-import") (part "PIC-RPX"))
    )
    (comp (ref "T57")
      (value "PIC-RPX")
      (footprint "eagle-import:TEMP-PAD")
      (libsource (lib "eagle-import") (part "PIC-RPX"))
    )
    (comp (ref "T61")
      (value "PIC-OUT")
      (footprint "eagle-import:TEMP-PAD")
      (libsource (lib "eagle-import") (part "PIC-OUT"))
    )
    (comp (ref "T62")
      (value "PIC-RPX")
      (footprint "eagle-import:TEMP-PAD")
      (libsource (lib "eagle-import") (part "PIC-RPX"))
    )
    (comp (ref "TP1")
      (value "DNP-TestPoint")
      (footprint "eagle-import:SMD_ROUND_1MM")
      (libsource (lib "eagle-import") (part "ROUND_SMD1MM"))
    )
    (comp (ref "TP2")
      (value "DNP-TestPoint")
      (footprint "eagle-import:TH_ROUND_14MM08MM")
      (libsource (lib "eagle-import") (part "ROUND_SMDTH1.4MM"))
    )
    (comp (ref "X1")
      (value "8MHz-5x3.2mm")
      (footprint "eagle-import:7B")
      (libsource (lib "eagle-import") (part "XTAL-7B"))
    )
  )
  (nets
    (net (code "1") (name "+3.3V") (class "Default")
      (node (ref "C108") (pin "1") (pinfunction "1_1") (pintype "passive"))
      (node (ref "C109") (pin "1") (pinfunction "1_1") (pintype "passive"))
      (node (ref "C43") (pin "1") (pinfunction "1_1") (pintype "passive"))
      (node (ref "C47") (pin "1") (pinfunction "1_1") (pintype "passive"))
      (node (ref "C48") (pin "1") (pinfunction "1_1") (pintype "passive"))
      (node (ref "C49") (pin "1") (pinfunction "1_1") (pintype "passive"))
      (node (ref "C50") (pin "1") (pinfunction "1_1") (pintype "passive"))
      (node (ref "C51") (pin "1") (pinfunction "1_1") (pintype "passive"))
      (node (ref "C52") (pin "1") (pinfunction "1_1") (pintype "passive"))
      (node (ref "C69") (pin "1") (pinfunction "1_1") (pintype "passive"))
      (node (ref "C70") (pin "1") (pinfunction "1_1") (pintype "passive"))
      (node (ref "C81") (pin "+") (pinfunction "+_+") (pintype "passive"))
      (node (ref "C82") (pin "1") (pinfunction "1_1") (pintype "passive"))
      (node (ref "IC1") (pin "16") (pinfunction "VDD3_16") (pintype "input"))
      (node (ref "IC1") (pin "2") (pinfunction "VDD2_2") (pintype "input"))
      (node (ref "IC1") (pin "37") (pinfunction "VDD4_37") (pintype "input"))
      (node (ref "IC1") (pin "46") (pinfunction "VDD5_46") (pintype "input"))
      (node (ref "IC1") (pin "55") (pinfunction "VUSB3V3_55") (pintype "input"))
      (node (ref "IC1") (pin "62") (pinfunction "VDD6_62") (pintype "input"))
      (node (ref "IC1") (pin "86") (pinfunction "VDD1_86") (pintype "input"))
      (node (ref "J17") (pin "2") (pinfunction "2_2") (pintype "passive"))
      (node (ref "R103") (pin "2") (pinfunction "2_2") (pintype "passive"))
      (node (ref "R104") (pin "1") (pinfunction "1_1") (pintype "passive"))
      (node (ref "R105") (pin "2") (pinfunction "2_2") (pintype "passive"))
      (node (ref "R106") (pin "2") (pinfunction "2_2") (pintype "passive"))
      (node (ref "R114") (pin "1") (pinfunction "1_1") (pintype "passive"))
      (node (ref "R115") (pin "2") (pinfunction "2_2") (pintype "passive"))
      (node (ref "R117") (pin "2") (pinfunction "2_2") (pintype "passive"))
      (node (ref "R126") (pin "1") (pinfunction "1_1") (pintype "passive"))
      (node (ref "R127") (pin "2") (pinfunction "2_2") (pintype "passive"))
      (node (ref "R129") (pin "1") (pinfunction "1_1") (pintype "passive"))
      (node (ref "R132") (pin "1") (pinfunction "1_1") (pintype "passive"))
      (node (ref "R142") (pin "1") (pinfunction "1_1") (pintype "passive"))
      (node (ref "R143") (pin "2") (pinfunction "2_2") (pintype "passive"))
      (node (ref "R28") (pin "2") (pinfunction "2_2") (pintype "passive"))
      (node (ref "R3") (pin "1") (pinfunction "1_1") (pintype "passive"))
      (node (ref "R38") (pin "2") (pinfunction "2_2") (pintype "passive"))
      (node (ref "R51") (pin "1") (pinfunction "1_1") (pintype "passive"))
      (node (ref "R52") (pin "2") (pinfunction "2_2") (pintype "passive"))
      (node (ref "R65") (pin "1") (pinfunction "1_1") (pintype "passive"))
      (node (ref "R82") (pin "1") (pinfunction "1_1") (pintype "passive"))
      (node (ref "R91") (pin "2") (pinfunction "2_2") (pintype "passive"))
      (node (ref "R92") (pin "1") (pinfunction "1_1") (pintype "passive"))
    )
    (net (code "2") (name "+3.3V{slash}1") (class "Default")
      (node (ref "C27") (pin "1") (pinfunction "1_1") (pintype "passive"))
      (node (ref "C28") (pin "1") (pinfunction "1_1") (pintype "passive"))
      (node (ref "IC11") (pin "2") (pinfunction "A1_2") (pintype "input"))
      (node (ref "IC11") (pin "8") (pinfunction "VCC_8") (pintype "input"))
      (node (ref "IC24") (pin "7") (pinfunction "A0_7") (pintype "input"))
      (node (ref "IC24") (pin "8") (pinfunction "VCC_8") (pintype "input"))
      (node (ref "IC7") (pin "8") (pinfunction "VCC_8") (pintype "input"))
      (node (ref "IC9") (pin "3") (pinfunction "/WP_3") (pintype "input"))
      (node (ref "IC9") (pin "7") (pinfunction "/HOLD_7") (pintype "input"))
      (node (ref "IC9") (pin "8") (pinfunction "VCC_8") (pintype "input"))
      (node (ref "Q2") (pin "3") (pinfunction "D_3") (pintype "passive"))
      (node (ref "Q2") (pin "P2") (pinfunction "D1_P2") (pintype "passive"))
      (node (ref "R18") (pin "1") (pinfunction "1_1") (pintype "passive"))
      (node (ref "R25") (pin "2") (pinfunction "2_2") (pintype "passive"))
      (node (ref "R26") (pin "1") (pinfunction "1_1") (pintype "passive"))
      (node (ref "R27") (pin "1") (pinfunction "1_1") (pintype "passive"))
    )
    (net (code "3") (name "+3.3V{slash}2") (class "Default")
      (node (ref "C41") (pin "1") (pinfunction "1_1") (pintype "passive"))
      (node (ref "C86") (pin "+") (pinfunction "+_+") (pintype "passive"))
      (node (ref "C97") (pin "2") (pinfunction "2_2") (pintype "passive"))
      (node (ref "IC12") (pin "8") (pinfunction "VCC_8") (pintype "input"))
      (node (ref "IC18") (pin "5") (pinfunction "VCC_5") (pintype "input"))
      (node (ref "IC2") (pin "5") (pinfunction "VCC_5") (pintype "input"))
      (node (ref "IC21") (pin "5") (pinfunction "VCC_5") (pintype "input"))
      (node (ref "IC5") (pin "5") (pinfunction "VCC_5") (pintype "input"))
      (node (ref "Q2") (pin "6") (pinfunction "D_6") (pintype "passive"))
      (node (ref "Q2") (pin "P1") (pinfunction "D1_P1") (pintype "passive"))
      (node (ref "R30") (pin "2") (pinfunction "2_2") (pintype "passive"))
      (node (ref "R34") (pin "1") (pinfunction "1_1") (pintype "passive"))
      (node (ref "R55") (pin "1") (pinfunction "1_1") (pintype "passive"))
      (node (ref "R72") (pin "1") (pinfunction "1_1") (pintype "passive"))
    )
    (net (code "4") (name "+3.3V{slash}3") (class "Default")
      (node (ref "C111") (pin "1") (pinfunction "1_1") (pintype "passive"))
      (node (ref "C112") (pin "+") (pinfunction "+_+") (pintype "passive"))
      (node (ref "IC31") (pin "8") (pinfunction "VCC_8") (pintype "input"))
      (node (ref "Q13") (pin "6") (pinfunction "D_6") (pintype "passive"))
      (node (ref "Q13") (pin "P1") (pinfunction "D1_P1") (pintype "passive"))
      (node (ref "R144") (pin "2") (pinfunction "2_2") (pintype "passive"))
      (node (ref "R149") (pin "2") (pinfunction "2_2") (pintype "passive"))
      (node (ref "R150") (pin "2") (pinfunction "2_2") (pintype "passive"))
    )
    (net (code "5") (name "+3.3V{slash}ICB") (class "Default")
      (node (ref "C116") (pin "1") (pinfunction "1_1") (pintype "passive"))
      (node (ref "C80") (pin "1") (pinfunction "1_1") (pintype "passive"))
      (node (ref "C91") (pin "1") (pinfunction "1_1") (pintype "passive"))
      (node (ref "C92") (pin "1") (pinfunction "1_1") (pintype "passive"))
      (node (ref "C93") (pin "1") (pinfunction "1_1") (pintype "passive"))
      (node (ref "C95") (pin "1") (pinfunction "1_1") (pintype "passive"))
      (node (ref "C96") (pin "1") (pinfunction "1_1") (pintype "passive"))
      (node (ref "IC19") (pin "1") (pinfunction "A_1") (pintype "input"))
      (node (ref "IC20") (pin "1") (pinfunction "A_1") (pintype "input"))
      (node (ref "IC29") (pin "10") (pinfunction "VCC_10") (pintype "input"))
      (node (ref "IC29") (pin "19") (pinfunction "VCC_19") (pintype "input"))
      (node (ref "IC29") (pin "24") (pinfunction "VCC_24") (pintype "input"))
      (node (ref "IC29") (pin "3") (pinfunction "VCC_3") (pintype "input"))
      (node (ref "J1") (pin "33") (pinfunction "+3.3V_33") (pintype "passive"))
      (node (ref "J6") (pin "1") (pinfunction "1_1") (pintype "passive"))
      (node (ref "R110") (pin "1") (pinfunction "1_1") (pintype "passive"))
      (node (ref "R121") (pin "2") (pinfunction "2_2") (pintype "passive"))
      (node (ref "R147") (pin "1") (pinfunction "1_1") (pintype "passive"))
      (node (ref "R53") (pin "2") (pinfunction "2_2") (pintype "passive"))
      (node (ref "R54") (pin "2") (pinfunction "2_2") (pintype "passive"))
    )
    (net (code "6") (name "/+3.3V-ULTRASONIC") (class "Default")
      (node (ref "C44") (pin "2") (pinfunction "2_2") (pintype "passive"))
      (node (ref "IC27") (pin "4") (pinfunction "4_4") (pintype "input"))
      (node (ref "J16") (pin "3") (pinfunction "3_3") (pintype "passive"))
      (node (ref "Q1") (pin "6") (pinfunction "D_6") (pintype "passive"))
      (node (ref "Q1") (pin "P1") (pinfunction "D1_P1") (pintype "passive"))
    )
    (net (code "7") (name "/+3.3VCCR") (class "Default")
      (node (ref "C78") (pin "2") (pinfunction "2_2") (pintype "passive"))
      (node (ref "J5") (pin "9") (pinfunction "9_9") (pintype "passive"))
      (node (ref "R115") (pin "1") (pinfunction "1_1") (pintype "passive"))
    )
    (net (code "8") (name "/+3.3V{slash}I2C") (class "Default")
      (node (ref "C87") (pin "2") (pinfunction "2_2") (pintype "passive"))
      (node (ref "IC28") (pin "4") (pinfunction "4_4") (pintype "input"))
      (node (ref "J22") (pin "3") (pinfunction "3_3") (pintype "passive"))
      (node (ref "Q1") (pin "3") (pinfunction "D_3") (pintype "passive"))
      (node (ref "Q1") (pin "P2") (pinfunction "D1_P2") (pintype "passive"))
      (node (ref "R130") (pin "1") (pinfunction "1_1") (pintype "passive"))
      (node (ref "R131") (pin "1") (pinfunction "1_1") (pintype "passive"))
    )
    (net (code "9") (name "/3.3V-BT") (class "Default")
      (node (ref "C42") (pin "1") (pinfunction "1_1") (pintype "passive"))
      (node (ref "J14") (pin "2") (pinfunction "2_2") (pintype "passive"))
      (node (ref "R38") (pin "1") (pinfunction "1_1") (pintype "passive"))
    )
    (net (code "10") (name "/3.3V2PWRON-ICB") (class "Default")
      (node (ref "J1") (pin "14") (pinfunction "GPIO133_14") (pintype "passive"))
      (node (ref "Q9") (pin "5") (pinfunction "G_5") (pintype "passive"))
    )
    (net (code "11") (name "/A+") (class "Default")
      (node (ref "IC14") (pin "3") (pinfunction "3_3") (pintype "passive"))
      (node (ref "J3") (pin "4") (pinfunction "4_4") (pintype "passive"))
      (node (ref "J4") (pin "4") (pinfunction "4_4") (pintype "passive"))
      (node (ref "L8") (pin "2") (pinfunction "2_2") (pintype "passive"))
    )
    (net (code "12") (name "/A++") (class "Default")
      (node (ref "IC12") (pin "6") (pinfunction "A_6") (pintype "bidirectional"))
      (node (ref "L8") (pin "1") (pinfunction "1_1") (pintype "passive"))
      (node (ref "R32") (pin "2") (pinfunction "2_2") (pintype "passive"))
      (node (ref "R34") (pin "2") (pinfunction "2_2") (pintype "passive"))
    )
    (net (code "13") (name "/AUDIO-IN") (class "Default")
      (node (ref "C20") (pin "1") (pinfunction "1_1") (pintype "passive"))
      (node (ref "J13") (pin "2") (pinfunction "2_2") (pintype "passive"))
    )
    (net (code "14") (name "/AUDIO-PWRON") (class "Default")
      (node (ref "IC1") (pin "90") (pinfunction "RPG0/PMD8/RG0_90") (pintype "bidirectional"))
      (node (ref "O14") (pin "P$1") (pinfunction "TP_P$1") (pintype "passive"))
      (node (ref "Q6") (pin "5") (pinfunction "G_5") (pintype "passive"))
      (node (ref "R13") (pin "1") (pinfunction "1_1") (pintype "passive"))
      (node (ref "T25") (pin "P$1") (pinfunction "TP_P$1") (pintype "passive"))
    )
    (net (code "15") (name "/AUD_IN+") (class "Default")
      (node (ref "C20") (pin "2") (pinfunction "2_2") (pintype "passive"))
      (node (ref "IC25") (pin "12") (pinfunction "INP_12") (pintype "input"))
    )
    (net (code "16") (name "/AUD_IN-") (class "Default")
      (node (ref "C21") (pin "2") (pinfunction "2_2") (pintype "passive"))
      (node (ref "IC25") (pin "11") (pinfunction "INN_11") (pintype "input"))
    )
    (net (code "17") (name "/B-") (class "Default")
      (node (ref "IC14") (pin "2") (pinfunction "2_2") (pintype "passive"))
      (node (ref "J3") (pin "5") (pinfunction "5_5") (pintype "passive"))
      (node (ref "J4") (pin "5") (pinfunction "5_5") (pintype "passive"))
      (node (ref "L7") (pin "2") (pinfunction "2_2") (pintype "passive"))
    )
    (net (code "18") (name "/B--") (class "Default")
      (node (ref "IC12") (pin "7") (pinfunction "B_7") (pintype "bidirectional"))
      (node (ref "L7") (pin "1") (pinfunction "1_1") (pintype "passive"))
      (node (ref "R31") (pin "1") (pinfunction "1_1") (pintype "passive"))
      (node (ref "R32") (pin "1") (pinfunction "1_1") (pintype "passive"))
    )
    (net (code "19") (name "/BSN") (class "Default")
      (node (ref "C14") (pin "2") (pinfunction "2_2") (pintype "passive"))
      (node (ref "IC25") (pin "22") (pinfunction "BSN_22") (pintype "input"))
      (node (ref "IC25") (pin "26") (pinfunction "BSN_26") (pintype "input"))
    )
    (net (code "20") (name "/BSP") (class "Default")
      (node (ref "C13") (pin "1") (pinfunction "1_1") (pintype "passive"))
      (node (ref "IC25") (pin "17") (pinfunction "BSP_17") (pintype "input"))
      (node (ref "IC25") (pin "21") (pinfunction "BSP_21") (pintype "input"))
    )
    (net (code "21") (name "/BT-RTS") (class "Default")
      (node (ref "IC1") (pin "83") (pinfunction "PMD14/RD6_83") (pintype "bidirectional"))
      (node (ref "J14") (pin "7") (pinfunction "7_7") (pintype "passive"))
    )
    (net (code "22") (name "/BT-RX") (class "Default")
      (node (ref "IC1") (pin "73") (pinfunction "SOSCI/RPC13/RC13_73") (pintype "bidirectional"))
      (node (ref "J14") (pin "3") (pinfunction "3_3") (pintype "passive"))
    )
    (net (code "23") (name "/BT-TX") (class "Default")
      (node (ref "IC1") (pin "74") (pinfunction "SOSCO/RPC14/T1CK/RC14_74") (pintype "bidirectional"))
      (node (ref "J14") (pin "4") (pinfunction "4_4") (pintype "passive"))
    )
    (net (code "24") (name "/CL_IRQ") (class "Default")
      (node (ref "IC1") (pin "39") (pinfunction "RPF13/RF13_39") (pintype "bidirectional"))
      (node (ref "J5") (pin "4") (pinfunction "4_4") (pintype "passive"))
      (node (ref "O18") (pin "P$1") (pinfunction "TP_P$1") (pintype "passive"))
      (node (ref "T6") (pin "P$1") (pinfunction "TP_P$1") (pintype "passive"))
    )
    (net (code "25") (name "/CON-LED") (class "Default")
      (node (ref "IC1") (pin "78") (pinfunction "AN26/RPD3/RD3_78") (pintype "bidirectional"))
      (node (ref "J14") (pin "6") (pinfunction "6_6") (pintype "passive"))
    )
    (net (code "26") (name "/CTL-ELMAGDISP") (class "Default")
      (node (ref "IC1") (pin "98") (pinfunction "AN20/PMD2/RE2_98") (pintype "bidirectional"))
      (node (ref "IC31") (pin "2") (pinfunction "/RE_2") (pintype "input"))
      (node (ref "IC31") (pin "3") (pinfunction "DE_3") (pintype "input"))
      (node (ref "O33") (pin "P$1") (pinfunction "TP_P$1") (pintype "passive"))
      (node (ref "R148") (pin "1") (pinfunction "1_1") (pintype "passive"))
    )
    (net (code "27") (name "/CURR-ICB") (class "Default")
      (node (ref "C38") (pin "1") (pinfunction "1_1") (pintype "passive"))
      (node (ref "IC1") (pin "23") (pinfunction "PGEC3/AN2/C2INB/RPB2/CTED13/RB2_23") (pintype "bidirectional"))
      (node (ref "R36") (pin "2") (pinfunction "2_2") (pintype "passive"))
    )
    (net (code "28") (name "/CURR-SENSE") (class "Default")
      (node (ref "C66") (pin "1") (pinfunction "1_1") (pintype "passive"))
      (node (ref "IC1") (pin "14") (pinfunction "AN19/C2INC/RPG9/PMA2/RG9_14") (pintype "bidirectional"))
      (node (ref "R102") (pin "2") (pinfunction "2_2") (pintype "passive"))
    )
    (net (code "29") (name "/D+") (class "Default")
      (node (ref "IC1") (pin "57") (pinfunction "D+/RG2_57") (pintype "bidirectional"))
      (node (ref "IC15") (pin "3") (pinfunction "3_3") (pintype "passive"))
      (node (ref "J12") (pin "3_D+") (pinfunction "D+_3_D+") (pintype "bidirectional"))
    )
    (net (code "30") (name "/D-") (class "Default")
      (node (ref "IC1") (pin "56") (pinfunction "D-/RG3_56") (pintype "bidirectional"))
      (node (ref "IC15") (pin "2") (pinfunction "2_2") (pintype "passive"))
      (node (ref "J12") (pin "2_D-") (pinfunction "D-_2_D-") (pintype "bidirectional"))
    )
    (net (code "31") (name "/DEBUG-RXD-A") (class "Default")
      (node (ref "J1") (pin "28") (pinfunction "RXD-A_28") (pintype "passive"))
      (node (ref "R109") (pin "1") (pinfunction "1_1") (pintype "passive"))
    )
    (net (code "32") (name "/DEBUG-TXD-A") (class "Default")
      (node (ref "J1") (pin "27") (pinfunction "TXD-A_27") (pintype "passive"))
      (node (ref "R108") (pin "1") (pinfunction "1_1") (pintype "passive"))
    )
    (net (code "33") (name "/DIN_SM") (class "Default")
      (node (ref "IC1") (pin "60") (pinfunction "TDI/CTED9/RA4_60") (pintype "bidirectional"))
      (node (ref "IC17") (pin "27") (pinfunction "DIN_27") (pintype "bidirectional"))
      (node (ref "O40") (pin "P$1") (pinfunction "TP_P$1") (pintype "passive"))
      (node (ref "T20") (pin "P$1") (pinfunction "TP_P$1") (pintype "passive"))
    )
    (net (code "34") (name "/DOUT_SM") (class "Default")
      (node (ref "IC1") (pin "79") (pinfunction "RPD12/PMD12/RD12_79") (pintype "bidirectional"))
      (node (ref "IC17") (pin "28") (pinfunction "DOUT_28") (pintype "bidirectional"))
      (node (ref "O27") (pin "P$1") (pinfunction "TP_P$1") (pintype "passive"))
      (node (ref "T19") (pin "P$1") (pinfunction "TP_P$1") (pintype "passive"))
    )
    (net (code "35") (name "/ELMAGDI-PWRON") (class "Default")
      (node (ref "IC1") (pin "100") (pinfunction "AN21/PMD4/RE4_100") (pintype "bidirectional"))
      (node (ref "O32") (pin "P$1") (pinfunction "TP_P$1") (pintype "passive"))
      (node (ref "Q11") (pin "2") (pinfunction "G_2") (pintype "passive"))
      (node (ref "Q11") (pin "5") (pinfunction "G_5") (pintype "passive"))
      (node (ref "R138") (pin "1") (pinfunction "1_1") (pintype "passive"))
    )
    (net (code "36") (name "/EN-SENSE+3.3V{slash}ICB") (class "Default")
      (node (ref "C74") (pin "2") (pinfunction "2_2") (pintype "passive"))
      (node (ref "IC1") (pin "35") (pinfunction "AN11/PMA12/RB11_35") (pintype "bidirectional"))
      (node (ref "R111") (pin "1") (pinfunction "1_1") (pintype "passive"))
    )
    (net (code "37") (name "/EN-UTRASONIC") (class "Default")
      (node (ref "IC1") (pin "81") (pinfunction "RPD4/PMWR/RD4_81") (pintype "bidirectional"))
      (node (ref "O22") (pin "P$1") (pinfunction "TP_P$1") (pintype "passive"))
      (node (ref "R153") (pin "1") (pinfunction "1_1") (pintype "passive"))
      (node (ref "T23") (pin "P$1") (pinfunction "TP_P$1") (pintype "passive"))
    )
    (net (code "38") (name "/GAIN1-AUDIO") (class "Default")
      (node (ref "IC1") (pin "93") (pinfunction "PMD0/RE0_93") (pintype "bidirectional"))
      (node (ref "IC25") (pin "5") (pinfunction "GAIN0_5") (pintype "input"))
      (node (ref "O9") (pin "P$1") (pinfunction "TP_P$1") (pintype "passive"))
      (node (ref "R9") (pin "2") (pinfunction "2_2") (pintype "passive"))
      (node (ref "T46") (pin "P$1") (pinfunction "TP_P$1") (pintype "passive"))
    )
    (net (code "39") (name "/GAIN2-AUDIO") (class "Default")
      (node (ref "IC1") (pin "92") (pinfunction "TRD3/CTED8/RA7_92") (pintype "bidirectional"))
      (node (ref "IC25") (pin "6") (pinfunction "GAIN1_6") (pintype "input"))
      (node (ref "O12") (pin "P$1") (pinfunction "TP_P$1") (pintype "passive"))
      (node (ref "R8") (pin "2") (pinfunction "2_2") (pintype "passive"))
      (node (ref "T35") (pin "P$1") (pinfunction "TP_P$1") (pintype "passive"))
    )
    (net (code "40") (name "/GPIO1") (class "Default")
      (node (ref "IC1") (pin "32") (pinfunction "AN8/RPB8/CTED10/RB8_32") (pintype "bidirectional"))
      (node (ref "O59") (pin "P$1") (pinfunction "TP_P$1") (pintype "passive"))
      (node (ref "R86") (pin "1") (pinfunction "1_1") (pintype "passive"))
      (node (ref "T49") (pin "P$1") (pinfunction "TP_P$1") (pintype "passive"))
    )
    (net (code "41") (name "/GPIO1_") (class "Default")
      (node (ref "J1") (pin "13") (pinfunction "GPIO98_13") (pintype "passive"))
      (node (ref "R112") (pin "2") (pinfunction "2_2") (pintype "passive"))
    )
    (net (code "42") (name "/GPIO2") (class "Default")
      (node (ref "IC1") (pin "33") (pinfunction "AN9/RPB9/CTED4/RB9_33") (pintype "bidirectional"))
      (node (ref "O60") (pin "P$1") (pinfunction "TP_P$1") (pintype "passive"))
      (node (ref "R87") (pin "1") (pinfunction "1_1") (pintype "passive"))
      (node (ref "T50") (pin "P$1") (pinfunction "TP_P$1") (pintype "passive"))
    )
    (net (code "43") (name "/GPIO2_") (class "Default")
      (node (ref "J1") (pin "15") (pinfunction "GPIO103_15") (pintype "passive"))
      (node (ref "R113") (pin "2") (pinfunction "2_2") (pintype "passive"))
    )
    (net (code "44") (name "/I2C-SCL-TOUCH") (class "Default")
      (node (ref "IC29") (pin "2") (pinfunction "SM_CLK_2") (pintype "input"))
      (node (ref "J1") (pin "6") (pinfunction "I2C-SCL_6") (pintype "passive"))
      (node (ref "J6") (pin "3") (pinfunction "3_3") (pintype "passive"))
    )
    (net (code "45") (name "/I2C-SDA-TOUCH") (class "Default")
      (node (ref "IC29") (pin "1") (pinfunction "SM_DAT_1") (pintype "input"))
      (node (ref "J1") (pin "5") (pinfunction "I2C-SDA_5") (pintype "passive"))
      (node (ref "J6") (pin "4") (pinfunction "4_4") (pintype "passive"))
    )
    (net (code "46") (name "/ICB-ON") (class "Default")
      (node (ref "IC1") (pin "91") (pinfunction "TRCLK/RA6_91") (pintype "bidirectional"))
      (node (ref "O13") (pin "P$1") (pinfunction "TP_P$1") (pintype "passive"))
      (node (ref "Q6") (pin "2") (pinfunction "G_2") (pintype "passive"))
      (node (ref "R10") (pin "1") (pinfunction "1_1") (pintype "passive"))
      (node (ref "R16") (pin "2") (pinfunction "2_2") (pintype "passive"))
      (node (ref "T2") (pin "P$1") (pinfunction "TP_P$1") (pintype "passive"))
    )
    (net (code "47") (name "/ILLUMINATE1") (class "Default")
      (node (ref "IC1") (pin "99") (pinfunction "RPE3/PMD3/RE3_99") (pintype "bidirectional"))
      (node (ref "O8") (pin "P$1") (pinfunction "TP_P$1") (pintype "passive"))
      (node (ref "R116") (pin "1") (pinfunction "1_1") (pintype "passive"))
      (node (ref "T29") (pin "P$1") (pinfunction "TP_P$1") (pintype "passive"))
    )
    (net (code "48") (name "/ILLUMINATE2") (class "Default")
      (node (ref "IC1") (pin "3") (pinfunction "AN22/RPE5/PMD5/RE5_3") (pintype "bidirectional"))
      (node (ref "O1") (pin "P$1") (pinfunction "TP_P$1") (pintype "passive"))
      (node (ref "R119") (pin "1") (pinfunction "1_1") (pintype "passive"))
      (node (ref "T30") (pin "P$1") (pinfunction "TP_P$1") (pintype "passive"))
    )
    (net (code "49") (name "/LAN-CTL") (class "Default")
      (node (ref "IC12") (pin "2") (pinfunction "/RE_2") (pintype "input"))
      (node (ref "IC12") (pin "3") (pinfunction "DE_3") (pintype "input"))
      (node (ref "IC21") (pin "4") (pinfunction "Y_4") (pintype "output"))
    )
    (net (code "50") (name "/LAN-CTL-ICB") (class "Default")
      (node (ref "IC21") (pin "1") (pinfunction "A_1") (pintype "input"))
      (node (ref "J1") (pin "16") (pinfunction "GPIO101_16") (pintype "passive"))
      (node (ref "R57") (pin "2") (pinfunction "2_2") (pintype "passive"))
    )
    (net (code "51") (name "/LAN-CTL-PIC") (class "Default")
      (node (ref "IC1") (pin "84") (pinfunction "PMD15/RD7_84") (pintype "bidirectional"))
      (node (ref "IC21") (pin "2") (pinfunction "B_2") (pintype "input"))
      (node (ref "R56") (pin "2") (pinfunction "2_2") (pintype "passive"))
    )
    (net (code "52") (name "/LAN-RX") (class "Default")
      (node (ref "IC1") (pin "88") (pinfunction "RPF1/PMD10/RF1_88") (pintype "bidirectional"))
      (node (ref "IC12") (pin "1") (pinfunction "R_1") (pintype "output"))
      (node (ref "IC19") (pin "2") (pinfunction "B_2") (pintype "input"))
      (node (ref "R72") (pin "2") (pinfunction "2_2") (pintype "passive"))
    )
    (net (code "53") (name "/LAN-RX-ICB") (class "Default")
      (node (ref "IC19") (pin "4") (pinfunction "Y_4") (pintype "output"))
      (node (ref "J1") (pin "31") (pinfunction "RXD-B_31") (pintype "passive"))
    )
    (net (code "54") (name "/LAN-TX") (class "Default")
      (node (ref "IC12") (pin "4") (pinfunction "D_4") (pintype "input"))
      (node (ref "IC2") (pin "4") (pinfunction "Y_4") (pintype "output"))
    )
    (net (code "55") (name "/LAN-TX-ICB") (class "Default")
      (node (ref "J1") (pin "32") (pinfunction "TXD-B_32") (pintype "passive"))
      (node (ref "R122") (pin "1") (pinfunction "1_1") (pintype "passive"))
      (node (ref "R54") (pin "1") (pinfunction "1_1") (pintype "passive"))
    )
    (net (code "56") (name "/LAN-TX-PIC") (class "Default")
      (node (ref "IC1") (pin "87") (pinfunction "RPF0/PMD11/RF0_87") (pintype "bidirectional"))
      (node (ref "IC2") (pin "1") (pinfunction "A_1") (pintype "input"))
      (node (ref "R55") (pin "2") (pinfunction "2_2") (pintype "passive"))
    )
    (net (code "57") (name "/LED-PIC") (class "Default")
      (node (ref "IC1") (pin "1") (pinfunction "RG15_1") (pintype "bidirectional"))
      (node (ref "R29") (pin "1") (pinfunction "1_1") (pintype "passive"))
      (node (ref "TP2") (pin "P$1") (pinfunction "TP_P$1") (pintype "passive"))
    )
    (net (code "58") (name "/OUTN") (class "Default")
      (node (ref "C14") (pin "1") (pinfunction "1_1") (pintype "passive"))
      (node (ref "IC25") (pin "23") (pinfunction "OUTN_23") (pintype "input"))
      (node (ref "IC25") (pin "25") (pinfunction "OUTN_25") (pintype "input"))
      (node (ref "L14") (pin "2") (pinfunction "2_2") (pintype "passive"))
    )
    (net (code "59") (name "/OUTP") (class "Default")
      (node (ref "C13") (pin "2") (pinfunction "2_2") (pintype "passive"))
      (node (ref "IC25") (pin "18") (pinfunction "OUTP_18") (pintype "input"))
      (node (ref "IC25") (pin "20") (pinfunction "OUTP_20") (pintype "input"))
      (node (ref "L15") (pin "2") (pinfunction "2_2") (pintype "passive"))
    )
    (net (code "60") (name "/PGC") (class "Default")
      (node (ref "IC1") (pin "24") (pinfunction "PGEC1/AN1/RPB1/CTED12/RB1_24") (pintype "bidirectional"))
      (node (ref "J17") (pin "5") (pinfunction "5_5") (pintype "passive"))
    )
    (net (code "61") (name "/PGC2-{slash}BTN2") (class "Default")
      (node (ref "IC3") (pin "3") (pinfunction "GP1/PGC_3") (pintype "bidirectional"))
      (node (ref "J10") (pin "5") (pinfunction "5_5") (pintype "passive"))
      (node (ref "R71") (pin "1") (pinfunction "1_1") (pintype "passive"))
    )
    (net (code "62") (name "/PGD") (class "Default")
      (node (ref "IC1") (pin "25") (pinfunction "PGED1/AN0/RPB0/RB0_25") (pintype "bidirectional"))
      (node (ref "J17") (pin "4") (pinfunction "4_4") (pintype "passive"))
    )
    (net (code "63") (name "/PGD2-{slash}BTN1") (class "Default")
      (node (ref "IC3") (pin "1") (pinfunction "GP0/PGD_1") (pintype "bidirectional"))
      (node (ref "J10") (pin "4") (pinfunction "4_4") (pintype "passive"))
      (node (ref "R120") (pin "1") (pinfunction "1_1") (pintype "passive"))
    )
    (net (code "64") (name "/PIC-RXD") (class "Default")
      (node (ref "IC1") (pin "6") (pinfunction "RPC1/RC1_6") (pintype "bidirectional"))
      (node (ref "O2") (pin "P$1") (pinfunction "TP_P$1") (pintype "passive"))
      (node (ref "R124") (pin "1") (pinfunction "1_1") (pintype "passive"))
      (node (ref "T26") (pin "P$1") (pinfunction "TP_P$1") (pintype "passive"))
    )
    (net (code "65") (name "/PIC-TX") (class "Default")
      (node (ref "IC1") (pin "9") (pinfunction "RPC4/CTED7/RC4_9") (pintype "bidirectional"))
      (node (ref "O5") (pin "P$1") (pinfunction "TP_P$1") (pintype "passive"))
      (node (ref "R123") (pin "2") (pinfunction "2_2") (pintype "passive"))
      (node (ref "T28") (pin "P$1") (pinfunction "TP_P$1") (pintype "passive"))
    )
    (net (code "66") (name "/POWER-GOOD") (class "Default")
      (node (ref "IC1") (pin "89") (pinfunction "RPG1/PMD9/RG1_89") (pintype "bidirectional"))
      (node (ref "IC6") (pin "4") (pinfunction "OUT_4") (pintype "output"))
      (node (ref "O15") (pin "P$1") (pinfunction "TP_P$1") (pintype "passive"))
      (node (ref "T45") (pin "P$1") (pinfunction "TP_P$1") (pintype "passive"))
    )
    (net (code "67") (name "/REF-EN") (class "Default")
      (node (ref "IC1") (pin "28") (pinfunction "VREF-/CVREF-/PMA7/RA9_28") (pintype "bidirectional"))
      (node (ref "R93") (pin "1") (pinfunction "1_1") (pintype "passive"))
    )
    (net (code "68") (name "/REF2,5V") (class "Default")
      (node (ref "C57") (pin "1") (pinfunction "1_1") (pintype "passive"))
      (node (ref "IC1") (pin "29") (pinfunction "VREF+/CVREF+/PMA6/RA10_29") (pintype "bidirectional"))
      (node (ref "IC13") (pin "2") (pinfunction "VOUT_2") (pintype "bidirectional"))
    )
    (net (code "69") (name "/RESET-ICB") (class "Default")
      (node (ref "IC1") (pin "18") (pinfunction "RPE8/RE8_18") (pintype "bidirectional"))
      (node (ref "O10") (pin "P$1") (pinfunction "TP_P$1") (pintype "passive"))
      (node (ref "Q9") (pin "2") (pinfunction "G_2") (pintype "passive"))
      (node (ref "R85") (pin "2") (pinfunction "2_2") (pintype "passive"))
      (node (ref "T61") (pin "P$1") (pinfunction "TP_P$1") (pintype "passive"))
    )
    (net (code "70") (name "/RXD-ELMAGDISP") (class "Default")
      (node (ref "IC1") (pin "7") (pinfunction "RPC2/RC2_7") (pintype "bidirectional"))
      (node (ref "IC31") (pin "1") (pinfunction "R_1") (pintype "output"))
      (node (ref "O23") (pin "P$1") (pinfunction "TP_P$1") (pintype "passive"))
      (node (ref "R150") (pin "1") (pinfunction "1_1") (pintype "passive"))
    )
    (net (code "71") (name "/RXD-ULTRASONIC") (class "Default")
      (node (ref "IC1") (pin "82") (pinfunction "RPD5/PMRD/RD5_82") (pintype "bidirectional"))
      (node (ref "O16") (pin "P$1") (pinfunction "TP_P$1") (pintype "passive"))
      (node (ref "R154") (pin "1") (pinfunction "1_1") (pintype "passive"))
      (node (ref "T3") (pin "P$1") (pinfunction "TP_P$1") (pintype "passive"))
    )
    (net (code "72") (name "/SCL1-EEPROM") (class "Default")
      (node (ref "IC1") (pin "66") (pinfunction "SCL1/RPA14/RA14_66") (pintype "bidirectional"))
      (node (ref "IC11") (pin "6") (pinfunction "SCL_6") (pintype "input"))
      (node (ref "IC24") (pin "2") (pinfunction "SCL_2") (pintype "input"))
      (node (ref "IC7") (pin "6") (pinfunction "SCL_6") (pintype "input"))
      (node (ref "R26") (pin "2") (pinfunction "2_2") (pintype "passive"))
    )
    (net (code "73") (name "/SCL2") (class "Default")
      (node (ref "IC1") (pin "58") (pinfunction "SCL2/RA2_58") (pintype "bidirectional"))
      (node (ref "O28") (pin "P$1") (pinfunction "TP_P$1") (pintype "passive"))
      (node (ref "R130") (pin "2") (pinfunction "2_2") (pintype "passive"))
      (node (ref "R152") (pin "1") (pinfunction "1_1") (pintype "passive"))
      (node (ref "T5") (pin "P$1") (pinfunction "TP_P$1") (pintype "passive"))
    )
    (net (code "74") (name "/SCLK1") (class "Default")
      (node (ref "IC1") (pin "70") (pinfunction "RPD10/SCK1/PMCS2/RD10_70") (pintype "bidirectional"))
      (node (ref "J5") (pin "5") (pinfunction "5_5") (pintype "passive"))
    )
    (net (code "75") (name "/SCLK2-SPI") (class "Default")
      (node (ref "IC1") (pin "10") (pinfunction "AN16/C1IND/RPG6/SCK2/PMA5/RG6_10") (pintype "bidirectional"))
      (node (ref "IC9") (pin "6") (pinfunction "C_6") (pintype "input"))
    )
    (net (code "76") (name "/SCLK_SM") (class "Default")
      (node (ref "IC1") (pin "76") (pinfunction "AN24/RPD1/RD1_76") (pintype "bidirectional"))
      (node (ref "IC17") (pin "26") (pinfunction "SCLK_26") (pintype "bidirectional"))
      (node (ref "O35") (pin "P$1") (pinfunction "TP_P$1") (pintype "passive"))
      (node (ref "T18") (pin "P$1") (pinfunction "TP_P$1") (pintype "passive"))
    )
    (net (code "77") (name "/SDA1-EEPROM") (class "Default")
      (node (ref "IC1") (pin "67") (pinfunction "SDA1/RPA15/RA15_67") (pintype "bidirectional"))
      (node (ref "IC11") (pin "5") (pinfunction "SDA_5") (pintype "bidirectional"))
      (node (ref "IC24") (pin "1") (pinfunction "SDA_1") (pintype "bidirectional"))
      (node (ref "IC7") (pin "5") (pinfunction "SDA_5") (pintype "bidirectional"))
      (node (ref "R27") (pin "2") (pinfunction "2_2") (pintype "passive"))
    )
    (net (code "78") (name "/SDA2") (class "Default")
      (node (ref "IC1") (pin "59") (pinfunction "SDA2/RA3_59") (pintype "bidirectional"))
      (node (ref "O19") (pin "P$1") (pinfunction "TP_P$1") (pintype "passive"))
      (node (ref "R131") (pin "2") (pinfunction "2_2") (pintype "passive"))
      (node (ref "R151") (pin "1") (pinfunction "1_1") (pintype "passive"))
      (node (ref "T1") (pin "P$1") (pinfunction "TP_P$1") (pintype "passive"))
    )
    (net (code "79") (name "/SDI1") (class "Default")
      (node (ref "IC1") (pin "50") (pinfunction "RPF5/PMA8/RF5_50") (pintype "bidirectional"))
      (node (ref "J5") (pin "8") (pinfunction "8_8") (pintype "passive"))
      (node (ref "O21") (pin "P$1") (pinfunction "TP_P$1") (pintype "passive"))
      (node (ref "T9") (pin "P$1") (pinfunction "TP_P$1") (pintype "passive"))
    )
    (net (code "80") (name "/SDI2-MISO") (class "Default")
      (node (ref "IC1") (pin "22") (pinfunction "PGED3/AN3/C2INA/RPB3/RB3_22") (pintype "bidirectional"))
      (node (ref "IC9") (pin "2") (pinfunction "Q_2") (pintype "bidirectional"))
    )
    (net (code "81") (name "/SDO1") (class "Default")
      (node (ref "IC1") (pin "48") (pinfunction "RPD15/RD15_48") (pintype "bidirectional"))
      (node (ref "J5") (pin "6") (pinfunction "6_6") (pintype "passive"))
      (node (ref "O58") (pin "P$1") (pinfunction "TP_P$1") (pintype "passive"))
      (node (ref "T8") (pin "P$1") (pinfunction "TP_P$1") (pintype "passive"))
    )
    (net (code "82") (name "/SDO2-MOSI") (class "Default")
      (node (ref "IC1") (pin "20") (pinfunction "AN5/C1INA/RPB5/RB5_20") (pintype "bidirectional"))
      (node (ref "IC9") (pin "5") (pinfunction "D_5") (pintype "input"))
    )
    (net (code "83") (name "/SENSE+3.3V") (class "Default")
      (node (ref "C73") (pin "1") (pinfunction "1_1") (pintype "passive"))
      (node (ref "IC1") (pin "44") (pinfunction "AN15/RPB15/PMA0/CTED6//RB15_44") (pintype "bidirectional"))
      (node (ref "R104") (pin "2") (pinfunction "2_2") (pintype "passive"))
      (node (ref "R107") (pin "1") (pinfunction "1_1") (pintype "passive"))
    )
    (net (code "84") (name "/SENSE+3.3V{slash}ICB") (class "Default")
      (node (ref "C74") (pin "1") (pinfunction "1_1") (pintype "passive"))
      (node (ref "IC1") (pin "34") (pinfunction "CVREFOUT/AN10/RPB10/PMA13/CTED11/RB10_34") (pintype "bidirectional"))
      (node (ref "R110") (pin "2") (pinfunction "2_2") (pintype "passive"))
      (node (ref "R111") (pin "2") (pinfunction "2_2") (pintype "passive"))
    )
    (net (code "85") (name "/SIM-CLK") (class "Default")
      (node (ref "IC17") (pin "18") (pinfunction "CLKB_18") (pintype "bidirectional"))
      (node (ref "J2") (pin "C3") (pinfunction "CLK/C3_C3") (pintype "bidirectional"))
    )
    (net (code "86") (name "/SIM-IO") (class "Default")
      (node (ref "IC17") (pin "20") (pinfunction "IOB_20") (pintype "bidirectional"))
      (node (ref "J2") (pin "C7") (pinfunction "C7/DATA_C7") (pintype "bidirectional"))
    )
    (net (code "87") (name "/SIM-RST") (class "Default")
      (node (ref "IC17") (pin "19") (pinfunction "RSTB_19") (pintype "bidirectional"))
      (node (ref "J2") (pin "C2") (pinfunction "RST/C2_C2") (pintype "input"))
    )
    (net (code "88") (name "/SIM-VCC") (class "Default")
      (node (ref "IC17") (pin "17") (pinfunction "VCCB_17") (pintype "bidirectional"))
      (node (ref "J2") (pin "C1") (pinfunction "VCC/C1_C1") (pintype "input"))
    )
    (net (code "89") (name "/SM_ASYNC") (class "Default")
      (node (ref "IC1") (pin "49") (pinfunction "RPF4/PMA9/RF4_49") (pintype "bidirectional"))
      (node (ref "IC17") (pin "31") (pinfunction "ASYNC_31") (pintype "bidirectional"))
      (node (ref "O20") (pin "P$1") (pinfunction "TP_P$1") (pintype "passive"))
      (node (ref "T57") (pin "P$1") (pinfunction "TP_P$1") (pintype "passive"))
    )
    (net (code "90") (name "/SM_C4A") (class "Default")
      (node (ref "IC17") (pin "4") (pinfunction "C4A_4") (pintype "bidirectional"))
      (node (ref "J15") (pin "2") (pinfunction "2_2") (pintype "passive"))
      (node (ref "J21") (pin "2") (pinfunction "2_2") (pintype "passive"))
      (node (ref "J9") (pin "2") (pinfunction "2_2") (pintype "passive"))
    )
    (net (code "91") (name "/SM_C8A") (class "Default")
      (node (ref "IC17") (pin "3") (pinfunction "C8A_3") (pintype "bidirectional"))
      (node (ref "J15") (pin "1") (pinfunction "1_1") (pintype "passive"))
      (node (ref "J21") (pin "1") (pinfunction "1_1") (pintype "passive"))
      (node (ref "J9") (pin "1") (pinfunction "1_1") (pintype "passive"))
    )
    (net (code "92") (name "/SM_CLK_A") (class "Default")
      (node (ref "IC17") (pin "7") (pinfunction "CLKA_7") (pintype "bidirectional"))
      (node (ref "J15") (pin "4") (pinfunction "4_4") (pintype "passive"))
      (node (ref "J21") (pin "4") (pinfunction "4_4") (pintype "passive"))
      (node (ref "J9") (pin "4") (pinfunction "4_4") (pintype "passive"))
    )
    (net (code "93") (name "/SM_DATA") (class "Default")
      (node (ref "IC1") (pin "68") (pinfunction "RPD8/RTCC/RD8_68") (pintype "bidirectional"))
      (node (ref "IC1") (pin "69") (pinfunction "RPD9/RD9_69") (pintype "bidirectional"))
      (node (ref "IC17") (pin "29") (pinfunction "DATA_29") (pintype "bidirectional"))
      (node (ref "O25") (pin "P$1") (pinfunction "TP_P$1") (pintype "passive"))
      (node (ref "O26") (pin "P$1") (pinfunction "TP_P$1") (pintype "passive"))
      (node (ref "T12") (pin "P$1") (pinfunction "TP_P$1") (pintype "passive"))
      (node (ref "T16") (pin "P$1") (pinfunction "TP_P$1") (pintype "passive"))
    )
    (net (code "94") (name "/SM_DET_A") (class "Default")
      (node (ref "IC17") (pin "2") (pinfunction "PRESA_2") (pintype "bidirectional"))
      (node (ref "J15") (pin "10") (pinfunction "10_10") (pintype "passive"))
      (node (ref "J21") (pin "10") (pinfunction "10_10") (pintype "passive"))
      (node (ref "J9") (pin "10") (pinfunction "10_10") (pintype "passive"))
    )
    (net (code "95") (name "/SM_IO_A") (class "Default")
      (node (ref "IC17") (pin "5") (pinfunction "IOA_5") (pintype "bidirectional"))
      (node (ref "J15") (pin "3") (pinfunction "3_3") (pintype "passive"))
      (node (ref "J21") (pin "3") (pinfunction "3_3") (pintype "passive"))
      (node (ref "J9") (pin "3") (pinfunction "3_3") (pintype "passive"))
    )
    (net (code "96") (name "/SM_RST") (class "Default")
      (node (ref "IC1") (pin "42") (pinfunction "AN13/RB13_42") (pintype "bidirectional"))
      (node (ref "IC17") (pin "30") (pinfunction "RIN_30") (pintype "bidirectional"))
      (node (ref "O55") (pin "P$1") (pinfunction "TP_P$1") (pintype "passive"))
      (node (ref "T11") (pin "P$1") (pinfunction "TP_P$1") (pintype "passive"))
    )
    (net (code "97") (name "/SM_RST_A") (class "Default")
      (node (ref "IC17") (pin "6") (pinfunction "RSTA_6") (pintype "bidirectional"))
      (node (ref "J15") (pin "6") (pinfunction "6_6") (pintype "passive"))
      (node (ref "J21") (pin "6") (pinfunction "6_6") (pintype "passive"))
      (node (ref "J9") (pin "6") (pinfunction "6_6") (pintype "passive"))
    )
    (net (code "98") (name "/SM_SYNC") (class "Default")
      (node (ref "IC1") (pin "43") (pinfunction "AN14/RPB14/PMA1/CTED5/RB14_43") (pintype "bidirectional"))
      (node (ref "IC17") (pin "32") (pinfunction "SYNC_32") (pintype "bidirectional"))
      (node (ref "O53") (pin "P$1") (pinfunction "TP_P$1") (pintype "passive"))
      (node (ref "T10") (pin "P$1") (pinfunction "TP_P$1") (pintype "passive"))
    )
    (net (code "99") (name "/SM_VCC_A") (class "Default")
      (node (ref "IC17") (pin "8") (pinfunction "VCCA_8") (pintype "bidirectional"))
      (node (ref "J15") (pin "9") (pinfunction "9_9") (pintype "passive"))
      (node (ref "J21") (pin "9") (pinfunction "9_9") (pintype "passive"))
      (node (ref "J9") (pin "9") (pinfunction "9_9") (pintype "passive"))
    )
    (net (code "100") (name "/SPKRN") (class "Default")
      (node (ref "C16") (pin "1") (pinfunction "1_1") (pintype "passive"))
      (node (ref "J11") (pin "2") (pinfunction "2_2") (pintype "passive"))
      (node (ref "L14") (pin "1") (pinfunction "1_1") (pintype "passive"))
    )
    (net (code "101") (name "/SPKRP") (class "Default")
      (node (ref "C15") (pin "1") (pinfunction "1_1") (pintype "passive"))
      (node (ref "J11") (pin "1") (pinfunction "1_1") (pintype "passive"))
      (node (ref "L15") (pin "1") (pinfunction "1_1") (pintype "passive"))
    )
    (net (code "102") (name "/TXD-ELMAGDISP") (class "Default")
      (node (ref "IC1") (pin "8") (pinfunction "RPC3/RC3_8") (pintype "bidirectional"))
      (node (ref "IC31") (pin "4") (pinfunction "D_4") (pintype "input"))
      (node (ref "O31") (pin "P$1") (pinfunction "TP_P$1") (pintype "passive"))
      (node (ref "R149") (pin "1") (pinfunction "1_1") (pintype "passive"))
    )
    (net (code "103") (name "/VBAT-LAN") (class "Default")
      (node (ref "D3") (pin "C") (pinfunction "C_C") (pintype "passive"))
      (node (ref "J3") (pin "1") (pinfunction "1_1") (pintype "passive"))
      (node (ref "J3") (pin "3") (pinfunction "3_3") (pintype "passive"))
      (node (ref "J4") (pin "1") (pinfunction "1_1") (pintype "passive"))
      (node (ref "J4") (pin "3") (pinfunction "3_3") (pintype "passive"))
      (node (ref "L11") (pin "2") (pinfunction "2_2") (pintype "passive"))
    )
    (net (code "104") (name "/VBAT-LAN-F") (class "Default")
      (node (ref "C34") (pin "1") (pinfunction "1_1") (pintype "passive"))
      (node (ref "D6") (pin "K") (pinfunction "K_K") (pintype "passive"))
      (node (ref "L11") (pin "1") (pinfunction "1_1") (pintype "passive"))
      (node (ref "Q3") (pin "1") (pinfunction "D_1") (pintype "passive"))
      (node (ref "Q3") (pin "2") (pinfunction "D_2") (pintype "passive"))
      (node (ref "Q3") (pin "5") (pinfunction "D_5") (pintype "passive"))
      (node (ref "Q3") (pin "6") (pinfunction "D_6") (pintype "passive"))
      (node (ref "Q5") (pin "4") (pinfunction "S_4") (pintype "passive"))
      (node (ref "R45") (pin "1") (pinfunction "1_1") (pintype "passive"))
      (node (ref "R94") (pin "1") (pinfunction "1_1") (pintype "passive"))
    )
    (net (code "105") (name "/VBAT-SENSE") (class "Default")
      (node (ref "C64") (pin "1") (pinfunction "1_1") (pintype "passive"))
      (node (ref "IC1") (pin "26") (pinfunction "PGEC2/AN6/RPB6/RB6_26") (pintype "bidirectional"))
      (node (ref "R100") (pin "1") (pinfunction "1_1") (pintype "passive"))
    )
    (net (code "106") (name "/VBAT-TO-LAN") (class "Default")
      (node (ref "IC1") (pin "52") (pinfunction "RPF2/RF2_52") (pintype "bidirectional"))
      (node (ref "Q4") (pin "2") (pinfunction "G_2") (pintype "passive"))
      (node (ref "R41") (pin "1") (pinfunction "1_1") (pintype "passive"))
      (node (ref "R59") (pin "1") (pinfunction "1_1") (pintype "passive"))
    )
    (net (code "107") (name "/VBAT-TO-LAN-ICB") (class "Default")
      (node (ref "J1") (pin "18") (pinfunction "GPIO85_18") (pintype "passive"))
      (node (ref "R59") (pin "2") (pinfunction "2_2") (pintype "passive"))
    )
    (net (code "108") (name "/VBATLAN-SENSE") (class "Default")
      (node (ref "C36") (pin "1") (pinfunction "1_1") (pintype "passive"))
      (node (ref "IC1") (pin "27") (pinfunction "PGED2/AN7/RPB7/CTED3/RB7_27") (pintype "bidirectional"))
      (node (ref "R101") (pin "1") (pinfunction "1_1") (pintype "passive"))
    )
    (net (code "109") (name "/VBUS") (class "Default")
      (node (ref "IC1") (pin "54") (pinfunction "VBUS_54") (pintype "input"))
      (node (ref "R128") (pin "2") (pinfunction "2_2") (pintype "passive"))
    )
    (net (code "110") (name "/VCAP-SENSE") (class "Default")
      (node (ref "C76") (pin "1") (pinfunction "1_1") (pintype "passive"))
      (node (ref "IC1") (pin "77") (pinfunction "AN25/RPD2/RD2_77") (pintype "bidirectional"))
      (node (ref "R118") (pin "1") (pinfunction "1_1") (pintype "passive"))
    )
    (net (code "111") (name "/VCC-AUDIO") (class "Default")
      (node (ref "C1") (pin "1") (pinfunction "1_1") (pintype "passive"))
      (node (ref "C10") (pin "1") (pinfunction "1_1") (pintype "passive"))
      (node (ref "C17") (pin "1") (pinfunction "1_1") (pintype "passive"))
      (node (ref "C18") (pin "1") (pinfunction "1_1") (pintype "passive"))
      (node (ref "C7") (pin "1") (pinfunction "1_1") (pintype "passive"))
      (node (ref "C72") (pin "1") (pinfunction "1_1") (pintype "passive"))
      (node (ref "C8") (pin "1") (pinfunction "1_1") (pintype "passive"))
      (node (ref "C9") (pin "1") (pinfunction "1_1") (pintype "passive"))
      (node (ref "IC25") (pin "15") (pinfunction "PVCC_15") (pintype "input"))
      (node (ref "IC25") (pin "16") (pinfunction "PVCC_16") (pintype "input"))
      (node (ref "IC25") (pin "27") (pinfunction "PVCC_27") (pintype "input"))
      (node (ref "IC25") (pin "28") (pinfunction "PVCC_28") (pintype "input"))
      (node (ref "L1") (pin "2") (pinfunction "2_2") (pintype "passive"))
      (node (ref "R4") (pin "1") (pinfunction "1_1") (pintype "passive"))
    )
    (net (code "112") (name "/VPS-ON") (class "Default")
      (node (ref "IC1") (pin "53") (pinfunction "RPF8/RF8_53") (pintype "bidirectional"))
      (node (ref "Q4") (pin "5") (pinfunction "G_5") (pintype "passive"))
      (node (ref "R44") (pin "1") (pinfunction "1_1") (pintype "passive"))
      (node (ref "R58") (pin "1") (pinfunction "1_1") (pintype "passive"))
    )
    (net (code "113") (name "/VPS-ON-ICB") (class "Default")
      (node (ref "J1") (pin "20") (pinfunction "GPIO45_20") (pintype "passive"))
      (node (ref "R58") (pin "2") (pinfunction "2_2") (pintype "passive"))
    )
    (net (code "114") (name "/VPS-PWR") (class "Default")
      (node (ref "D4") (pin "C") (pinfunction "C_C") (pintype "passive"))
      (node (ref "J3") (pin "6") (pinfunction "6_6") (pintype "passive"))
      (node (ref "J4") (pin "6") (pinfunction "6_6") (pintype "passive"))
      (node (ref "L10") (pin "2") (pinfunction "2_2") (pintype "passive"))
    )
    (net (code "115") (name "/VPS-PWR-F") (class "Default")
      (node (ref "L10") (pin "1") (pinfunction "1_1") (pintype "passive"))
      (node (ref "Q5") (pin "1") (pinfunction "D_1") (pintype "passive"))
      (node (ref "Q5") (pin "2") (pinfunction "D_2") (pintype "passive"))
      (node (ref "Q5") (pin "5") (pinfunction "D_5") (pintype "passive"))
      (node (ref "Q5") (pin "6") (pinfunction "D_6") (pintype "passive"))
      (node (ref "R23") (pin "2") (pinfunction "2_2") (pintype "passive"))
    )
    (net (code "116") (name "/VPS-SENSE") (class "Default")
      (node (ref "C65") (pin "1") (pinfunction "1_1") (pintype "passive"))
      (node (ref "IC1") (pin "12") (pinfunction "AN18/C2IND/RPG8/PMA3/RG8_12") (pintype "bidirectional"))
      (node (ref "IC20") (pin "2") (pinfunction "B_2") (pintype "input"))
      (node (ref "R48") (pin "2") (pinfunction "2_2") (pintype "passive"))
      (node (ref "R49") (pin "1") (pinfunction "1_1") (pintype "passive"))
    )
    (net (code "117") (name "/VPS-SENSE-ICB") (class "Default")
      (node (ref "IC20") (pin "4") (pinfunction "Y_4") (pintype "output"))
      (node (ref "J1") (pin "19") (pinfunction "GPIO79_19") (pintype "passive"))
    )
    (net (code "118") (name "/WAKE-SW") (class "Default")
      (node (ref "IC1") (pin "72") (pinfunction "RPD0/INT0/RD0_72") (pintype "bidirectional"))
      (node (ref "J14") (pin "5") (pinfunction "5_5") (pintype "passive"))
    )
    (net (code "119") (name "/{slash}3.3V1PWRON") (class "Default")
      (node (ref "IC1") (pin "21") (pinfunction "AN4/C1INB/USBOEN/RB4_21") (pintype "bidirectional"))
      (node (ref "R24") (pin "2") (pinfunction "2_2") (pintype "passive"))
    )
    (net (code "120") (name "/{slash}3.3V2PWRON") (class "Default")
      (node (ref "IC1") (pin "96") (pinfunction "TRD1/RG12_96") (pintype "bidirectional"))
      (node (ref "R60") (pin "2") (pinfunction "2_2") (pintype "passive"))
      (node (ref "R75") (pin "2") (pinfunction "2_2") (pintype "passive"))
    )
    (net (code "121") (name "/{slash}BTN1") (class "Default")
      (node (ref "IC1") (pin "5") (pinfunction "AN27/PMD7/RE7_5") (pintype "bidirectional"))
      (node (ref "IC22") (pin "4") (pinfunction "OUT_4") (pintype "output"))
      (node (ref "O6") (pin "P$1") (pinfunction "TP_P$1") (pintype "passive"))
      (node (ref "R120") (pin "2") (pinfunction "2_2") (pintype "passive"))
      (node (ref "T31") (pin "P$1") (pinfunction "TP_P$1") (pintype "passive"))
    )
    (net (code "122") (name "/{slash}BTN2") (class "Default")
      (node (ref "IC1") (pin "4") (pinfunction "AN23/PMD6/RE6_4") (pintype "bidirectional"))
      (node (ref "IC23") (pin "4") (pinfunction "OUT_4") (pintype "output"))
      (node (ref "O7") (pin "P$1") (pinfunction "TP_P$1") (pintype "passive"))
      (node (ref "R71") (pin "2") (pinfunction "2_2") (pintype "passive"))
      (node (ref "T34") (pin "P$1") (pinfunction "TP_P$1") (pintype "passive"))
    )
    (net (code "123") (name "/{slash}CL_CS") (class "Default")
      (node (ref "IC1") (pin "38") (pinfunction "TCK/CTED2/RA1_38") (pintype "bidirectional"))
      (node (ref "J5") (pin "7") (pinfunction "7_7") (pintype "passive"))
      (node (ref "O17") (pin "P$1") (pinfunction "TP_P$1") (pintype "passive"))
      (node (ref "T4") (pin "P$1") (pinfunction "TP_P$1") (pintype "passive"))
    )
    (net (code "124") (name "/{slash}FAULT-AUDIO") (class "Default")
      (node (ref "IC1") (pin "95") (pinfunction "TRD2/RG14_95") (pintype "bidirectional"))
      (node (ref "O3") (pin "P$1") (pinfunction "TP_P$1") (pintype "passive"))
      (node (ref "R7") (pin "1") (pinfunction "1_1") (pintype "passive"))
      (node (ref "T48") (pin "P$1") (pinfunction "TP_P$1") (pintype "passive"))
    )
    (net (code "125") (name "/{slash}FMEM1-CS") (class "Default")
      (node (ref "IC1") (pin "11") (pinfunction "AN17/C1INC/RPG7/PMA4/RG7_11") (pintype "bidirectional"))
      (node (ref "IC9") (pin "1") (pinfunction "/S_1") (pintype "input"))
      (node (ref "R25") (pin "1") (pinfunction "1_1") (pintype "passive"))
    )
    (net (code "126") (name "/{slash}I2C_PWRON") (class "Default")
      (node (ref "IC1") (pin "97") (pinfunction "TRD0/RG13_97") (pintype "bidirectional"))
      (node (ref "O29") (pin "P$1") (pinfunction "TP_P$1") (pintype "passive"))
      (node (ref "R125") (pin "2") (pinfunction "2_2") (pintype "passive"))
      (node (ref "T7") (pin "P$1") (pinfunction "TP_P$1") (pintype "passive"))
    )
    (net (code "127") (name "/{slash}INT-TOUCH") (class "Default")
      (node (ref "J1") (pin "38") (pinfunction "PWM_B_38") (pintype "passive"))
      (node (ref "J6") (pin "5") (pinfunction "5_5") (pintype "passive"))
    )
    (net (code "128") (name "/{slash}LD_SM") (class "Default")
      (node (ref "IC1") (pin "61") (pinfunction "TDO/RA5_61") (pintype "bidirectional"))
      (node (ref "IC17") (pin "25") (pinfunction "/LD_25") (pintype "bidirectional"))
      (node (ref "O39") (pin "P$1") (pinfunction "TP_P$1") (pintype "passive"))
      (node (ref "T17") (pin "P$1") (pinfunction "TP_P$1") (pintype "passive"))
    )
    (net (code "129") (name "/{slash}MCLR") (class "Default")
      (node (ref "IC1") (pin "13") (pinfunction "~{MCLR}_13") (pintype "input"))
      (node (ref "J17") (pin "1") (pinfunction "1_1") (pintype "passive"))
      (node (ref "R61") (pin "2") (pinfunction "2_2") (pintype "passive"))
      (node (ref "R90") (pin "2") (pinfunction "2_2") (pintype "passive"))
    )
    (net (code "130") (name "/{slash}MCLR2") (class "Default")
      (node (ref "IC3") (pin "6") (pinfunction "GP3/MCLR_6") (pintype "bidirectional"))
      (node (ref "J10") (pin "1") (pinfunction "1_1") (pintype "passive"))
    )
    (net (code "131") (name "/{slash}RESET-ICB-OUT") (class "Default")
      (node (ref "IC1") (pin "19") (pinfunction "RPE9/RE9_19") (pintype "bidirectional"))
      (node (ref "J1") (pin "4") (pinfunction "/RST-OUT_4") (pintype "passive"))
      (node (ref "O11") (pin "P$1") (pinfunction "TP_P$1") (pintype "passive"))
      (node (ref "T62") (pin "P$1") (pinfunction "TP_P$1") (pintype "passive"))
    )
    (net (code "132") (name "/{slash}RESET-TOUCH") (class "Default")
      (node (ref "J1") (pin "39") (pinfunction "PWM_C_39") (pintype "passive"))
      (node (ref "J6") (pin "6") (pinfunction "6_6") (pintype "passive"))
    )
    (net (code "133") (name "/{slash}RST-IN") (class "Default")
      (node (ref "IC29") (pin "16") (pinfunction "/LRESET_16") (pintype "input"))
      (node (ref "J1") (pin "1") (pinfunction "/RST-IN_1") (pintype "passive"))
      (node (ref "Q9") (pin "6") (pinfunction "D_6") (pintype "passive"))
      (node (ref "R53") (pin "1") (pinfunction "1_1") (pintype "passive"))
    )
    (net (code "134") (name "/{slash}SD-AUDIO") (class "Default")
      (node (ref "IC1") (pin "94") (pinfunction "PMD1/RE1_94") (pintype "bidirectional"))
      (node (ref "O4") (pin "P$1") (pinfunction "TP_P$1") (pintype "passive"))
      (node (ref "R6") (pin "1") (pinfunction "1_1") (pintype "passive"))
      (node (ref "R84") (pin "2") (pinfunction "2_2") (pintype "passive"))
      (node (ref "T47") (pin "P$1") (pinfunction "TP_P$1") (pintype "passive"))
    )
    (net (code "135") (name "/{slash}SM_FAULT") (class "Default")
      (node (ref "IC1") (pin "71") (pinfunction "RPD11/PMCS1/RD11_71") (pintype "bidirectional"))
      (node (ref "IC17") (pin "24") (pinfunction "-FAULT_24") (pintype "bidirectional"))
      (node (ref "O24") (pin "P$1") (pinfunction "TP_P$1") (pintype "passive"))
      (node (ref "T21") (pin "P$1") (pinfunction "TP_P$1") (pintype "passive"))
    )
    (net (code "136") (name "/{slash}TWI_WAKEUP") (class "Default")
      (node (ref "IC29") (pin "22") (pinfunction "/TWI_WUP_22") (pintype "input"))
      (node (ref "J1") (pin "17") (pinfunction "GPIO97_17") (pintype "passive"))
    )
    (net (code "137") (name "/{slash}USNC-PWRON") (class "Default")
      (node (ref "IC1") (pin "80") (pinfunction "PMD13/RD13_80") (pintype "bidirectional"))
      (node (ref "O30") (pin "P$1") (pinfunction "TP_P$1") (pintype "passive"))
      (node (ref "R50") (pin "2") (pinfunction "2_2") (pintype "passive"))
      (node (ref "T24") (pin "P$1") (pinfunction "TP_P$1") (pintype "passive"))
    )
    (net (code "138") (name "DGND") (class "Default")
      (node (ref "C1") (pin "2") (pinfunction "2_2") (pintype "passive"))
      (node (ref "C10") (pin "2") (pinfunction "2_2") (pintype "passive"))
      (node (ref "C100") (pin "2") (pinfunction "2_2") (pintype "passive"))
      (node (ref "C101") (pin "2") (pinfunction "2_2") (pintype "passive"))
      (node (ref "C102") (pin "2") (pinfunction "2_2") (pintype "passive"))
      (node (ref "C103") (pin "2") (pinfunction "2_2") (pintype "passive"))
      (node (ref "C104") (pin "2") (pinfunction "2_2") (pintype "passive"))
      (node (ref "C105") (pin "2") (pinfunction "2_2") (pintype "passive"))
      (node (ref "C106") (pin "2") (pinfunction "2_2") (pintype "passive"))
      (node (ref "C109") (pin "2") (pinfunction "2_2") (pintype "passive"))
      (node (ref "C11") (pin "2") (pinfunction "2_2") (pintype "passive"))
      (node (ref "C110") (pin "2") (pinfunction "2_2") (pintype "passive"))
      (node (ref "C111") (pin "2") (pinfunction "2_2") (pintype "passive"))
      (node (ref "C112") (pin "-") (pinfunction "-_-") (pintype "passive"))
      (node (ref "C113") (pin "2") (pinfunction "2_2") (pintype "passive"))
      (node (ref "C114") (pin "2") (pinfunction "2_2") (pintype "passive"))
      (node (ref "C115") (pin "2") (pinfunction "2_2") (pintype "passive"))
      (node (ref "C116") (pin "2") (pinfunction "2_2") (pintype "passive"))
      (node (ref "C117") (pin "2") (pinfunction "2_2") (pintype "passive"))
      (node (ref "C118") (pin "2") (pinfunction "2_2") (pintype "passive"))
      (node (ref "C12") (pin "2") (pinfunction "2_2") (pintype "passive"))
      (node (ref "C15") (pin "2") (pinfunction "2_2") (pintype "passive"))
      (node (ref "C16") (pin "2") (pinfunction "2_2") (pintype "passive"))
      (node (ref "C17") (pin "2") (pinfunction "2_2") (pintype "passive"))
      (node (ref "C18") (pin "2") (pinfunction "2_2") (pintype "passive"))
      (node (ref "C19") (pin "2") (pinfunction "2_2") (pintype "passive"))
      (node (ref "C2") (pin "2") (pinfunction "2_2") (pintype "passive"))
      (node (ref "C21") (pin "1") (pinfunction "1_1") (pintype "passive"))
      (node (ref "C22") (pin "2") (pinfunction "2_2") (pintype "passive"))
      (node (ref "C23") (pin "2") (pinfunction "2_2") (pintype "passive"))
      (node (ref "C24") (pin "1") (pinfunction "1_1") (pintype "passive"))
      (node (ref "C27") (pin "2") (pinfunction "2_2") (pintype "passive"))
      (node (ref "C28") (pin "2") (pinfunction "2_2") (pintype "passive"))
      (node (ref "C29") (pin "2") (pinfunction "2_2") (pintype "passive"))
      (node (ref "C3") (pin "2") (pinfunction "2_2") (pintype "passive"))
      (node (ref "C30") (pin "2") (pinfunction "2_2") (pintype "passive"))
      (node (ref "C31") (pin "-") (pinfunction "-_-") (pintype "passive"))
      (node (ref "C35") (pin "2") (pinfunction "2_2") (pintype "passive"))
      (node (ref "C36") (pin "2") (pinfunction "2_2") (pintype "passive"))
      (node (ref "C38") (pin "2") (pinfunction "2_2") (pintype "passive"))
      (node (ref "C40") (pin "2") (pinfunction "2_2") (pintype "passive"))
      (node (ref "C41") (pin "2") (pinfunction "2_2") (pintype "passive"))
      (node (ref "C42") (pin "2") (pinfunction "2_2") (pintype "passive"))
      (node (ref "C44") (pin "1") (pinfunction "1_1") (pintype "passive"))
      (node (ref "C45") (pin "2") (pinfunction "2_2") (pintype "passive"))
      (node (ref "C46") (pin "2") (pinfunction "2_2") (pintype "passive"))
      (node (ref "C47") (pin "2") (pinfunction "2_2") (pintype "passive"))
      (node (ref "C48") (pin "2") (pinfunction "2_2") (pintype "passive"))
      (node (ref "C49") (pin "2") (pinfunction "2_2") (pintype "passive"))
      (node (ref "C5") (pin "2") (pinfunction "2_2") (pintype "passive"))
      (node (ref "C50") (pin "2") (pinfunction "2_2") (pintype "passive"))
      (node (ref "C51") (pin "2") (pinfunction "2_2") (pintype "passive"))
      (node (ref "C52") (pin "2") (pinfunction "2_2") (pintype "passive"))
      (node (ref "C53") (pin "2") (pinfunction "2_2") (pintype "passive"))
      (node (ref "C54") (pin "-") (pinfunction "-_-") (pintype "passive"))
      (node (ref "C55") (pin "2") (pinfunction "2_2") (pintype "passive"))
      (node (ref "C56") (pin "-") (pinfunction "-_-") (pintype "passive"))
      (node (ref "C57") (pin "2") (pinfunction "2_2") (pintype "passive"))
      (node (ref "C58") (pin "2") (pinfunction "2_2") (pintype "passive"))
      (node (ref "C59") (pin "2") (pinfunction "2_2") (pintype "passive"))
      (node (ref "C6") (pin "2") (pinfunction "2_2") (pintype "passive"))
      (node (ref "C60") (pin "2") (pinfunction "2_2") (pintype "passive"))
      (node (ref "C61") (pin "2") (pinfunction "2_2") (pintype "passive"))
      (node (ref "C62") (pin "2") (pinfunction "2_2") (pintype "passive"))
      (node (ref "C63") (pin "2") (pinfunction "2_2") (pintype "passive"))
      (node (ref "C64") (pin "2") (pinfunction "2_2") (pintype "passive"))
      (node (ref "C65") (pin "2") (pinfunction "2_2") (pintype "passive"))
      (node (ref "C66") (pin "2") (pinfunction "2_2") (pintype "passive"))
      (node (ref "C67") (pin "2") (pinfunction "2_2") (pintype "passive"))
      (node (ref "C68") (pin "2") (pinfunction "2_2") (pintype "passive"))
      (node (ref "C7") (pin "2") (pinfunction "2_2") (pintype "passive"))
      (node (ref "C71") (pin "2") (pinfunction "2_2") (pintype "passive"))
      (node (ref "C72") (pin "2") (pinfunction "2_2") (pintype "passive"))
      (node (ref "C75") (pin "2") (pinfunction "2_2") (pintype "passive"))
      (node (ref "C76") (pin "2") (pinfunction "2_2") (pintype "passive"))
      (node (ref "C77") (pin "2") (pinfunction "2_2") (pintype "passive"))
      (node (ref "C78") (pin "1") (pinfunction "1_1") (pintype "passive"))
      (node (ref "C79") (pin "2") (pinfunction "2_2") (pintype "passive"))
      (node (ref "C8") (pin "2") (pinfunction "2_2") (pintype "passive"))
      (node (ref "C81") (pin "-") (pinfunction "-_-") (pintype "passive"))
      (node (ref "C83") (pin "2") (pinfunction "2_2") (pintype "passive"))
      (node (ref "C84") (pin "2") (pinfunction "2_2") (pintype "passive"))
      (node (ref "C85") (pin "2") (pinfunction "2_2") (pintype "passive"))
      (node (ref "C86") (pin "-") (pinfunction "-_-") (pintype "passive"))
      (node (ref "C87") (pin "1") (pinfunction "1_1") (pintype "passive"))
      (node (ref "C88") (pin "2") (pinfunction "2_2") (pintype "passive"))
      (node (ref "C9") (pin "2") (pinfunction "2_2") (pintype "passive"))
      (node (ref "C91") (pin "2") (pinfunction "2_2") (pintype "passive"))
      (node (ref "C92") (pin "2") (pinfunction "2_2") (pintype "passive"))
      (node (ref "C93") (pin "2") (pinfunction "2_2") (pintype "passive"))
      (node (ref "C94") (pin "2") (pinfunction "2_2") (pintype "passive"))
      (node (ref "C95") (pin "2") (pinfunction "2_2") (pintype "passive"))
      (node (ref "C96") (pin "2") (pinfunction "2_2") (pintype "passive"))
      (node (ref "C97") (pin "1") (pinfunction "1_1") (pintype "passive"))
      (node (ref "C98") (pin "2") (pinfunction "2_2") (pintype "passive"))
      (node (ref "C99") (pin "2") (pinfunction "2_2") (pintype "passive"))
      (node (ref "D1") (pin "A") (pinfunction "A_A") (pintype "passive"))
      (node (ref "D2") (pin "-") (pinfunction "A_-") (pintype "passive"))
      (node (ref "D5") (pin "K") (pinfunction "K_K") (pintype "passive"))
      (node (ref "D7") (pin "A") (pinfunction "A_A") (pintype "passive"))
      (node (ref "IC1") (pin "15") (pinfunction "VSS2_15") (pintype "input"))
      (node (ref "IC1") (pin "31") (pinfunction "AVSS_31") (pintype "input"))
      (node (ref "IC1") (pin "36") (pinfunction "VSS3_36") (pintype "input"))
      (node (ref "IC1") (pin "45") (pinfunction "VSS4_45") (pintype "input"))
      (node (ref "IC1") (pin "65") (pinfunction "VSS5_65") (pintype "input"))
      (node (ref "IC1") (pin "75") (pinfunction "VSS1_75") (pintype "input"))
      (node (ref "IC10") (pin "1") (pinfunction "GND_1") (pintype "input"))
      (node (ref "IC10") (pin "2") (pinfunction "GND1_2") (pintype "input"))
      (node (ref "IC11") (pin "1") (pinfunction "A0_1") (pintype "input"))
      (node (ref "IC11") (pin "3") (pinfunction "A2_3") (pintype "input"))
      (node (ref "IC11") (pin "4") (pinfunction "GND_4") (pintype "input"))
      (node (ref "IC12") (pin "5") (pinfunction "GND_5") (pintype "input"))
      (node (ref "IC13") (pin "3") (pinfunction "GND_3") (pintype "bidirectional"))
      (node (ref "IC15") (pin "1") (pinfunction "1_1") (pintype "input"))
      (node (ref "IC16") (pin "4") (pinfunction "V-_4") (pintype "input"))
      (node (ref "IC17") (pin "10") (pinfunction "PGND_10") (pintype "input"))
      (node (ref "IC17") (pin "21") (pinfunction "PRESB_21") (pintype "bidirectional"))
      (node (ref "IC17") (pin "9") (pinfunction "SGND_9") (pintype "input"))
      (node (ref "IC17") (pin "PAD") (pinfunction "PAD_PAD") (pintype "input"))
      (node (ref "IC18") (pin "3") (pinfunction "GND_3") (pintype "input"))
      (node (ref "IC19") (pin "3") (pinfunction "GND_3") (pintype "input"))
      (node (ref "IC2") (pin "3") (pinfunction "GND_3") (pintype "input"))
      (node (ref "IC20") (pin "3") (pinfunction "GND_3") (pintype "input"))
      (node (ref "IC21") (pin "3") (pinfunction "GND_3") (pintype "input"))
      (node (ref "IC22") (pin "3") (pinfunction "GND_3") (pintype "input"))
      (node (ref "IC23") (pin "3") (pinfunction "GND_3") (pintype "input"))
      (node (ref "IC24") (pin "4") (pinfunction "GND_4") (pintype "input"))
      (node (ref "IC24") (pin "5") (pinfunction "A2_5") (pintype "input"))
      (node (ref "IC24") (pin "6") (pinfunction "A1_6") (pintype "input"))
      (node (ref "IC25") (pin "19") (pinfunction "PGND_19") (pintype "input"))
      (node (ref "IC25") (pin "24") (pinfunction "PGND_24") (pintype "input"))
      (node (ref "IC25") (pin "3") (pinfunction "GND_3") (pintype "input"))
      (node (ref "IC25") (pin "4") (pinfunction "GND_4") (pintype "input"))
      (node (ref "IC25") (pin "8") (pinfunction "AGND_8") (pintype "input"))
      (node (ref "IC25") (pin "EP") (pinfunction "EP_EP") (pintype "input"))
      (node (ref "IC26") (pin "1") (pinfunction "1_1") (pintype "input"))
      (node (ref "IC27") (pin "1") (pinfunction "1_1") (pintype "input"))
      (node (ref "IC28") (pin "1") (pinfunction "1_1") (pintype "input"))
      (node (ref "IC29") (pin "11") (pinfunction "GND_11") (pintype "input"))
      (node (ref "IC29") (pin "17") (pinfunction "GPIO_17") (pintype "input"))
      (node (ref "IC29") (pin "18") (pinfunction "GND_18") (pintype "input"))
      (node (ref "IC29") (pin "20") (pinfunction "/PIRQ_20") (pintype "input"))
      (node (ref "IC29") (pin "21") (pinfunction "ATEST_21") (pintype "input"))
      (node (ref "IC29") (pin "23") (pinfunction "ATEST_23") (pintype "input"))
      (node (ref "IC29") (pin "25") (pinfunction "GND_25") (pintype "input"))
      (node (ref "IC29") (pin "26") (pinfunction "ATEST_26") (pintype "input"))
      (node (ref "IC29") (pin "4") (pinfunction "GND_4") (pintype "input"))
      (node (ref "IC29") (pin "8") (pinfunction "TESTL_8") (pintype "input"))
      (node (ref "IC29") (pin "9") (pinfunction "TESTBI/GPIO/XT_9") (pintype "input"))
      (node (ref "IC3") (pin "2") (pinfunction "VSS_2") (pintype "input"))
      (node (ref "IC30") (pin "8") (pinfunction "SYNC_8") (pintype "input"))
      (node (ref "IC30") (pin "EP") (pinfunction "GND_EP") (pintype "input"))
      (node (ref "IC31") (pin "5") (pinfunction "GND_5") (pintype "input"))
      (node (ref "IC4") (pin "1") (pinfunction "GND_1") (pintype "input"))
      (node (ref "IC4") (pin "2") (pinfunction "GND1_2") (pintype "input"))
      (node (ref "IC5") (pin "3") (pinfunction "GND_3") (pintype "input"))
      (node (ref "IC6") (pin "2") (pinfunction "GND_2") (pintype "input"))
      (node (ref "IC7") (pin "1") (pinfunction "A0_1") (pintype "input"))
      (node (ref "IC7") (pin "2") (pinfunction "A1_2") (pintype "input"))
      (node (ref "IC7") (pin "3") (pinfunction "A2_3") (pintype "input"))
      (node (ref "IC7") (pin "4") (pinfunction "GND_4") (pintype "input"))
      (node (ref "IC7") (pin "7") (pinfunction "WP_7") (pintype "input"))
      (node (ref "IC8") (pin "10") (pinfunction "SYNC_10") (pintype "input"))
      (node (ref "IC8") (pin "EP") (pinfunction "GND_EP") (pintype "input"))
      (node (ref "IC9") (pin "4") (pinfunction "GND_4") (pintype "input"))
      (node (ref "J1") (pin "2") (pinfunction "GND1_2") (pintype "passive"))
      (node (ref "J1") (pin "21") (pinfunction "GND4_21") (pintype "passive"))
      (node (ref "J1") (pin "3") (pinfunction "GND2_3") (pintype "passive"))
      (node (ref "J1") (pin "36") (pinfunction "GND5_36") (pintype "passive"))
      (node (ref "J1") (pin "7") (pinfunction "GND3_7") (pintype "passive"))
      (node (ref "J10") (pin "3") (pinfunction "3_3") (pintype "passive"))
      (node (ref "J12") (pin "4_GND") (pinfunction "GND_4_GND") (pintype "bidirectional"))
      (node (ref "J12") (pin "SH1") (pinfunction "GND_SH1_SH1") (pintype "bidirectional"))
      (node (ref "J12") (pin "SH2") (pinfunction "GND_SH2_SH2") (pintype "bidirectional"))
      (node (ref "J13") (pin "1") (pinfunction "1_1") (pintype "passive"))
      (node (ref "J14") (pin "1") (pinfunction "1_1") (pintype "passive"))
      (node (ref "J15") (pin "7") (pinfunction "7_7") (pintype "passive"))
      (node (ref "J15") (pin "8") (pinfunction "8_8") (pintype "passive"))
      (node (ref "J16") (pin "4") (pinfunction "4_4") (pintype "passive"))
      (node (ref "J17") (pin "3") (pinfunction "3_3") (pintype "passive"))
      (node (ref "J18") (pin "1") (pinfunction "1_1") (pintype "passive"))
      (node (ref "J19") (pin "1") (pinfunction "1_1") (pintype "passive"))
      (node (ref "J2") (pin "C5") (pinfunction "C5/GND_C5") (pintype "input"))
      (node (ref "J20") (pin "1") (pinfunction "1_1") (pintype "passive"))
      (node (ref "J21") (pin "7") (pinfunction "7_7") (pintype "passive"))
      (node (ref "J21") (pin "8") (pinfunction "8_8") (pintype "passive"))
      (node (ref "J22") (pin "4") (pinfunction "4_4") (pintype "passive"))
      (node (ref "J23") (pin "5") (pinfunction "5_5") (pintype "passive"))
      (node (ref "J23") (pin "6") (pinfunction "6_6") (pintype "passive"))
      (node (ref "J5") (pin "1") (pinfunction "1_1") (pintype "passive"))
      (node (ref "J6") (pin "2") (pinfunction "2_2") (pintype "passive"))
      (node (ref "J9") (pin "7") (pinfunction "7_7") (pintype "passive"))
      (node (ref "J9") (pin "8") (pinfunction "8_8") (pintype "passive"))
      (node (ref "L12") (pin "1") (pinfunction "1_1") (pintype "passive"))
      (node (ref "PCB1") (pin "1") (pinfunction "1_1") (pintype "bidirectional"))
      (node (ref "PCB1") (pin "2") (pinfunction "2_2") (pintype "bidirectional"))
      (node (ref "PCB1") (pin "4") (pinfunction "4_4") (pintype "bidirectional"))
      (node (ref "PCB3") (pin "1") (pinfunction "P$1_1") (pintype "bidirectional"))
      (node (ref "Q10") (pin "1") (pinfunction "S_1") (pintype "passive"))
      (node (ref "Q10") (pin "4") (pinfunction "S_4") (pintype "passive"))
      (node (ref "Q9") (pin "1") (pinfunction "S_1") (pintype "passive"))
      (node (ref "Q9") (pin "4") (pinfunction "S_4") (pintype "passive"))
      (node (ref "R10") (pin "2") (pinfunction "2_2") (pintype "passive"))
      (node (ref "R12") (pin "1") (pinfunction "1_1") (pintype "passive"))
      (node (ref "R13") (pin "2") (pinfunction "2_2") (pintype "passive"))
      (node (ref "R136") (pin "2") (pinfunction "2_2") (pintype "passive"))
      (node (ref "R137") (pin "2") (pinfunction "2_2") (pintype "passive"))
      (node (ref "R138") (pin "2") (pinfunction "2_2") (pintype "passive"))
      (node (ref "R140") (pin "1") (pinfunction "1_1") (pintype "passive"))
      (node (ref "R141") (pin "1") (pinfunction "1_1") (pintype "passive"))
      (node (ref "R146") (pin "1") (pinfunction "1_1") (pintype "passive"))
      (node (ref "R148") (pin "2") (pinfunction "2_2") (pintype "passive"))
      (node (ref "R15") (pin "1") (pinfunction "1_1") (pintype "passive"))
      (node (ref "R17") (pin "2") (pinfunction "2_2") (pintype "passive"))
      (node (ref "R19") (pin "2") (pinfunction "2_2") (pintype "passive"))
      (node (ref "R2") (pin "2") (pinfunction "2_2") (pintype "passive"))
      (node (ref "R21") (pin "2") (pinfunction "2_2") (pintype "passive"))
      (node (ref "R31") (pin "2") (pinfunction "2_2") (pintype "passive"))
      (node (ref "R40") (pin "1") (pinfunction "1_1") (pintype "passive"))
      (node (ref "R41") (pin "2") (pinfunction "2_2") (pintype "passive"))
      (node (ref "R43") (pin "1") (pinfunction "1_1") (pintype "passive"))
      (node (ref "R44") (pin "2") (pinfunction "2_2") (pintype "passive"))
      (node (ref "R46") (pin "1") (pinfunction "1_1") (pintype "passive"))
      (node (ref "R48") (pin "1") (pinfunction "1_1") (pintype "passive"))
      (node (ref "R56") (pin "1") (pinfunction "1_1") (pintype "passive"))
      (node (ref "R57") (pin "1") (pinfunction "1_1") (pintype "passive"))
      (node (ref "R63") (pin "2") (pinfunction "2_2") (pintype "passive"))
      (node (ref "R70") (pin "1") (pinfunction "1_1") (pintype "passive"))
      (node (ref "R74") (pin "2") (pinfunction "2_2") (pintype "passive"))
      (node (ref "R8") (pin "1") (pinfunction "1_1") (pintype "passive"))
      (node (ref "R83") (pin "1") (pinfunction "1_1") (pintype "passive"))
      (node (ref "R84") (pin "1") (pinfunction "1_1") (pintype "passive"))
      (node (ref "R85") (pin "1") (pinfunction "1_1") (pintype "passive"))
      (node (ref "R88") (pin "1") (pinfunction "1_1") (pintype "passive"))
      (node (ref "R89") (pin "1") (pinfunction "1_1") (pintype "passive"))
      (node (ref "R9") (pin "1") (pinfunction "1_1") (pintype "passive"))
      (node (ref "R96") (pin "2") (pinfunction "2_2") (pintype "passive"))
      (node (ref "R99") (pin "2") (pinfunction "2_2") (pintype "passive"))
    )
    (net (code "139") (name "Net-(C11-Pad1)") (class "Default")
      (node (ref "C11") (pin "1") (pinfunction "1_1") (pintype "passive"))
      (node (ref "C19") (pin "1") (pinfunction "1_1") (pintype "passive"))
      (node (ref "IC25") (pin "7") (pinfunction "AVCC_7") (pintype "input"))
      (node (ref "R4") (pin "2") (pinfunction "2_2") (pintype "passive"))
      (node (ref "R5") (pin "1") (pinfunction "1_1") (pintype "passive"))
    )
    (net (code "140") (name "Net-(C24-Pad2)") (class "Default")
      (node (ref "C24") (pin "2") (pinfunction "2_2") (pintype "passive"))
      (node (ref "R77") (pin "2") (pinfunction "2_2") (pintype "passive"))
    )
    (net (code "141") (name "Net-(C39-Pad1)") (class "Default")
      (node (ref "C39") (pin "1") (pinfunction "1_1") (pintype "passive"))
      (node (ref "IC14") (pin "4") (pinfunction "4_4") (pintype "input"))
      (node (ref "R30") (pin "1") (pinfunction "1_1") (pintype "passive"))
    )
    (net (code "142") (name "Net-(C39-Pad2)") (class "Default")
      (node (ref "C39") (pin "2") (pinfunction "2_2") (pintype "passive"))
      (node (ref "D3") (pin "A") (pinfunction "A_A") (pintype "passive"))
      (node (ref "D4") (pin "A") (pinfunction "A_A") (pintype "passive"))
      (node (ref "IC14") (pin "1") (pinfunction "1_1") (pintype "input"))
      (node (ref "J3") (pin "2") (pinfunction "2_2") (pintype "passive"))
      (node (ref "J3") (pin "7") (pinfunction "7_7") (pintype "passive"))
      (node (ref "J3") (pin "8") (pinfunction "8_8") (pintype "passive"))
      (node (ref "J4") (pin "2") (pinfunction "2_2") (pintype "passive"))
      (node (ref "J4") (pin "7") (pinfunction "7_7") (pintype "passive"))
      (node (ref "J4") (pin "8") (pinfunction "8_8") (pintype "passive"))
      (node (ref "L12") (pin "2") (pinfunction "2_2") (pintype "passive"))
    )
    (net (code "143") (name "Net-(C40-Pad1)") (class "Default")
      (node (ref "C40") (pin "1") (pinfunction "1_1") (pintype "passive"))
      (node (ref "R90") (pin "1") (pinfunction "1_1") (pintype "passive"))
      (node (ref "R91") (pin "1") (pinfunction "1_1") (pintype "passive"))
    )
    (net (code "144") (name "Net-(C68-Pad1)") (class "Default")
      (node (ref "C68") (pin "1") (pinfunction "1_1") (pintype "passive"))
      (node (ref "R112") (pin "1") (pinfunction "1_1") (pintype "passive"))
      (node (ref "R86") (pin "2") (pinfunction "2_2") (pintype "passive"))
      (node (ref "R88") (pin "2") (pinfunction "2_2") (pintype "passive"))
    )
    (net (code "145") (name "Net-(C71-Pad1)") (class "Default")
      (node (ref "C71") (pin "1") (pinfunction "1_1") (pintype "passive"))
      (node (ref "R113") (pin "1") (pinfunction "1_1") (pintype "passive"))
      (node (ref "R87") (pin "2") (pinfunction "2_2") (pintype "passive"))
      (node (ref "R89") (pin "2") (pinfunction "2_2") (pintype "passive"))
    )
    (net (code "146") (name "Net-(C89-Pad+)") (class "Default")
      (node (ref "C89") (pin "+") (pinfunction "+_+") (pintype "passive"))
      (node (ref "C90") (pin "1") (pinfunction "1_1") (pintype "passive"))
      (node (ref "JP2") (pin "2") (pinfunction "2_2") (pintype "bidirectional"))
    )
    (net (code "147") (name "Net-(C89-Pad-)") (class "Default")
      (node (ref "C89") (pin "-") (pinfunction "-_-") (pintype "passive"))
      (node (ref "C90") (pin "2") (pinfunction "2_2") (pintype "passive"))
      (node (ref "R78") (pin "1") (pinfunction "1_1") (pintype "passive"))
      (node (ref "R79") (pin "1") (pinfunction "1_1") (pintype "passive"))
      (node (ref "R80") (pin "2") (pinfunction "2_2") (pintype "passive"))
      (node (ref "R81") (pin "2") (pinfunction "2_2") (pintype "passive"))
    )
    (net (code "148") (name "Net-(C94-Pad1)") (class "Default")
      (node (ref "C94") (pin "1") (pinfunction "1_1") (pintype "passive"))
      (node (ref "IC26") (pin "4") (pinfunction "4_4") (pintype "input"))
      (node (ref "R147") (pin "2") (pinfunction "2_2") (pintype "passive"))
    )
    (net (code "149") (name "Net-(C102-Pad1)") (class "Default")
      (node (ref "C102") (pin "1") (pinfunction "1_1") (pintype "passive"))
      (node (ref "C103") (pin "1") (pinfunction "1_1") (pintype "passive"))
      (node (ref "C106") (pin "1") (pinfunction "1_1") (pintype "passive"))
      (node (ref "D8") (pin "K") (pinfunction "K_K") (pintype "passive"))
      (node (ref "L5") (pin "1") (pinfunction "1_1") (pintype "passive"))
      (node (ref "R133") (pin "1") (pinfunction "1_1") (pintype "passive"))
    )
    (net (code "150") (name "Net-(C105-Pad1)") (class "Default")
      (node (ref "C105") (pin "1") (pinfunction "1_1") (pintype "passive"))
      (node (ref "R135") (pin "2") (pinfunction "2_2") (pintype "passive"))
    )
    (net (code "151") (name "Net-(C110-Pad1)") (class "Default")
      (node (ref "C110") (pin "1") (pinfunction "1_1") (pintype "passive"))
      (node (ref "J23") (pin "1") (pinfunction "1_1") (pintype "passive"))
      (node (ref "J23") (pin "2") (pinfunction "2_2") (pintype "passive"))
      (node (ref "L5") (pin "2") (pinfunction "2_2") (pintype "passive"))
    )
    (net (code "152") (name "Net-(C114-Pad1)") (class "Default")
      (node (ref "C114") (pin "1") (pinfunction "1_1") (pintype "passive"))
      (node (ref "L4") (pin "1") (pinfunction "1_1") (pintype "passive"))
      (node (ref "Q12") (pin "1") (pinfunction "D_1") (pintype "passive"))
      (node (ref "Q12") (pin "2") (pinfunction "D_2") (pintype "passive"))
      (node (ref "Q12") (pin "5") (pinfunction "D_5") (pintype "passive"))
      (node (ref "Q12") (pin "6") (pinfunction "D_6") (pintype "passive"))
    )
    (net (code "153") (name "Net-(C115-Pad1)") (class "Default")
      (node (ref "C115") (pin "1") (pinfunction "1_1") (pintype "passive"))
      (node (ref "L1") (pin "1") (pinfunction "1_1") (pintype "passive"))
      (node (ref "Q8") (pin "1") (pinfunction "D_1") (pintype "passive"))
      (node (ref "Q8") (pin "2") (pinfunction "D_2") (pintype "passive"))
      (node (ref "Q8") (pin "5") (pinfunction "D_5") (pintype "passive"))
      (node (ref "Q8") (pin "6") (pinfunction "D_6") (pintype "passive"))
    )
    (net (code "154") (name "Net-(C117-Pad1)") (class "Default")
      (node (ref "C117") (pin "1") (pinfunction "1_1") (pintype "passive"))
      (node (ref "L6") (pin "2") (pinfunction "2_2") (pintype "passive"))
      (node (ref "R129") (pin "2") (pinfunction "2_2") (pintype "passive"))
    )
    (net (code "155") (name "Net-(D2-C)") (class "Default")
      (node (ref "C26") (pin "1") (pinfunction "1_1") (pintype "passive"))
      (node (ref "C30") (pin "1") (pinfunction "1_1") (pintype "passive"))
      (node (ref "C31") (pin "+") (pinfunction "+_+") (pintype "passive"))
      (node (ref "D2") (pin "+") (pinfunction "C_+") (pintype "passive"))
      (node (ref "IC8") (pin "1") (pinfunction "BD_1") (pintype "input"))
      (node (ref "L6") (pin "1") (pinfunction "1_1") (pintype "passive"))
      (node (ref "L9") (pin "2") (pinfunction "2_2") (pintype "passive"))
      (node (ref "R20") (pin "1") (pinfunction "1_1") (pintype "passive"))
    )
    (net (code "156") (name "Net-(D5-PadA)") (class "Default")
      (node (ref "D5") (pin "A") (pinfunction "A_A") (pintype "passive"))
      (node (ref "R29") (pin "2") (pinfunction "2_2") (pintype "passive"))
    )
    (net (code "157") (name "Net-(F1-Pad1)") (class "Default")
      (node (ref "F1") (pin "1") (pinfunction "1_1") (pintype "passive"))
      (node (ref "J19") (pin "2") (pinfunction "2_2") (pintype "passive"))
    )
    (net (code "158") (name "Net-(IC1-AVDD)") (class "Default")
      (node (ref "C55") (pin "1") (pinfunction "1_1") (pintype "passive"))
      (node (ref "C56") (pin "+") (pinfunction "+_+") (pintype "passive"))
      (node (ref "C88") (pin "1") (pinfunction "1_1") (pintype "passive"))
      (node (ref "IC1") (pin "30") (pinfunction "AVDD_30") (pintype "input"))
      (node (ref "L13") (pin "2") (pinfunction "2_2") (pintype "passive"))
    )
    (net (code "159") (name "Net-(IC1-CLKI{slash}RC12{slash}OSC1)") (class "Default")
      (node (ref "C60") (pin "1") (pinfunction "1_1") (pintype "passive"))
      (node (ref "IC1") (pin "63") (pinfunction "CLKI/RC12/OSC1_63") (pintype "bidirectional"))
      (node (ref "X1") (pin "3") (pinfunction "2_3") (pintype "passive"))
    )
    (net (code "160") (name "Net-(IC1-CLKO{slash}RC15{slash}OSC2)") (class "Default")
      (node (ref "C61") (pin "1") (pinfunction "1_1") (pintype "passive"))
      (node (ref "IC1") (pin "64") (pinfunction "CLKO/RC15/OSC2_64") (pintype "bidirectional"))
      (node (ref "X1") (pin "1") (pinfunction "1_1") (pintype "passive"))
    )
    (net (code "161") (name "Net-(IC1-RPD14{slash}RD14)") (class "Default")
      (node (ref "C73") (pin "2") (pinfunction "2_2") (pintype "passive"))
      (node (ref "IC1") (pin "47") (pinfunction "RPD14/RD14_47") (pintype "bidirectional"))
      (node (ref "R107") (pin "2") (pinfunction "2_2") (pintype "passive"))
    )
    (net (code "162") (name "Net-(IC1-VCAP)") (class "Default")
      (node (ref "C53") (pin "1") (pinfunction "1_1") (pintype "passive"))
      (node (ref "C54") (pin "+") (pinfunction "+_+") (pintype "passive"))
      (node (ref "IC1") (pin "85") (pinfunction "VCAP_85") (pintype "input"))
      (node (ref "R118") (pin "2") (pinfunction "2_2") (pintype "passive"))
    )
    (net (code "163") (name "Net-(IC3-GP2{slash}T0CK)") (class "Default")
      (node (ref "IC3") (pin "4") (pinfunction "GP2/T0CK_4") (pintype "bidirectional"))
      (node (ref "R61") (pin "1") (pinfunction "1_1") (pintype "passive"))
    )
    (net (code "164") (name "Net-(IC3-VDD)") (class "Default")
      (node (ref "C6") (pin "1") (pinfunction "1_1") (pintype "passive"))
      (node (ref "IC3") (pin "5") (pinfunction "VDD_5") (pintype "input"))
      (node (ref "J10") (pin "2") (pinfunction "2_2") (pintype "passive"))
      (node (ref "R3") (pin "2") (pinfunction "2_2") (pintype "passive"))
    )
    (net (code "165") (name "Net-(IC4-OUT)") (class "Default")
      (node (ref "IC4") (pin "3") (pinfunction "OUT_3") (pintype "output"))
      (node (ref "R36") (pin "1") (pinfunction "1_1") (pintype "passive"))
    )
    (net (code "166") (name "Net-(IC4-VIN-)") (class "Default")
      (node (ref "C107") (pin "1") (pinfunction "1_1") (pintype "passive"))
      (node (ref "C32") (pin "1") (pinfunction "1_1") (pintype "passive"))
      (node (ref "IC4") (pin "4") (pinfunction "VIN-_4") (pintype "input"))
      (node (ref "Q12") (pin "4") (pinfunction "S_4") (pintype "passive"))
      (node (ref "Q7") (pin "4") (pinfunction "S_4") (pintype "passive"))
      (node (ref "R11") (pin "1") (pinfunction "1_1") (pintype "passive"))
      (node (ref "R139") (pin "1") (pinfunction "1_1") (pintype "passive"))
      (node (ref "R16") (pin "1") (pinfunction "1_1") (pintype "passive"))
      (node (ref "R35") (pin "1") (pinfunction "1_1") (pintype "passive"))
      (node (ref "R37") (pin "1") (pinfunction "1_1") (pintype "passive"))
    )
    (net (code "167") (name "Net-(IC5-IN)") (class "Default")
      (node (ref "C80") (pin "2") (pinfunction "2_2") (pintype "passive"))
      (node (ref "IC5") (pin "2") (pinfunction "IN_2") (pintype "input"))
      (node (ref "R121") (pin "1") (pinfunction "1_1") (pintype "passive"))
    )
    (net (code "168") (name "Net-(IC6-HTH)") (class "Default")
      (node (ref "IC6") (pin "1") (pinfunction "HTH_1") (pintype "input"))
      (node (ref "R46") (pin "2") (pinfunction "2_2") (pintype "passive"))
      (node (ref "R47") (pin "1") (pinfunction "1_1") (pintype "passive"))
    )
    (net (code "169") (name "Net-(IC6-LTH)") (class "Default")
      (node (ref "IC6") (pin "3") (pinfunction "LTH_3") (pintype "input"))
      (node (ref "R33") (pin "1") (pinfunction "1_1") (pintype "passive"))
      (node (ref "R47") (pin "2") (pinfunction "2_2") (pintype "passive"))
    )
    (net (code "170") (name "Net-(IC6-VDD)") (class "Default")
      (node (ref "C35") (pin "1") (pinfunction "1_1") (pintype "passive"))
      (node (ref "IC6") (pin "5") (pinfunction "VDD_5") (pintype "input"))
      (node (ref "R28") (pin "1") (pinfunction "1_1") (pintype "passive"))
    )
    (net (code "171") (name "Net-(IC8-BOOST)") (class "Default")
      (node (ref "C25") (pin "2") (pinfunction "2_2") (pintype "passive"))
      (node (ref "IC8") (pin "2") (pinfunction "BOOST_2") (pintype "input"))
    )
    (net (code "172") (name "Net-(IC8-EN)") (class "Default")
      (node (ref "IC8") (pin "5") (pinfunction "EN_5") (pintype "input"))
      (node (ref "JP1") (pin "2") (pinfunction "2_2") (pintype "bidirectional"))
      (node (ref "R22") (pin "2") (pinfunction "2_2") (pintype "passive"))
    )
    (net (code "173") (name "Net-(IC8-FB)") (class "Default")
      (node (ref "C26") (pin "2") (pinfunction "2_2") (pintype "passive"))
      (node (ref "IC8") (pin "6") (pinfunction "FB_6") (pintype "input"))
      (node (ref "R19") (pin "1") (pinfunction "1_1") (pintype "passive"))
      (node (ref "R20") (pin "2") (pinfunction "2_2") (pintype "passive"))
    )
    (net (code "174") (name "Net-(IC8-RT)") (class "Default")
      (node (ref "IC8") (pin "8") (pinfunction "RT_8") (pintype "input"))
      (node (ref "R17") (pin "1") (pinfunction "1_1") (pintype "passive"))
    )
    (net (code "175") (name "Net-(IC8-SS)") (class "Default")
      (node (ref "IC8") (pin "7") (pinfunction "SS_7") (pintype "input"))
      (node (ref "R77") (pin "1") (pinfunction "1_1") (pintype "passive"))
    )
    (net (code "176") (name "Net-(IC8-SW)") (class "Default")
      (node (ref "C25") (pin "1") (pinfunction "1_1") (pintype "passive"))
      (node (ref "D7") (pin "K") (pinfunction "K_K") (pintype "passive"))
      (node (ref "IC8") (pin "3") (pinfunction "SW_3") (pintype "output"))
      (node (ref "L9") (pin "1") (pinfunction "1_1") (pintype "passive"))
    )
    (net (code "177") (name "Net-(IC8-VIN)") (class "Default")
      (node (ref "C22") (pin "1") (pinfunction "1_1") (pintype "passive"))
      (node (ref "C23") (pin "1") (pinfunction "1_1") (pintype "passive"))
      (node (ref "C84") (pin "1") (pinfunction "1_1") (pintype "passive"))
      (node (ref "IC8") (pin "4") (pinfunction "VIN_4") (pintype "input"))
      (node (ref "JP1") (pin "3") (pinfunction "3_3") (pintype "bidirectional"))
      (node (ref "L2") (pin "2") (pinfunction "2_2") (pintype "passive"))
      (node (ref "R22") (pin "1") (pinfunction "1_1") (pintype "passive"))
    )
    (net (code "178") (name "Net-(IC10-OUT)") (class "Default")
      (node (ref "IC10") (pin "3") (pinfunction "OUT_3") (pintype "output"))
      (node (ref "R102") (pin "1") (pinfunction "1_1") (pintype "passive"))
    )
    (net (code "179") (name "Net-(IC10-VIN+)") (class "Default")
      (node (ref "C29") (pin "1") (pinfunction "1_1") (pintype "passive"))
      (node (ref "C83") (pin "1") (pinfunction "1_1") (pintype "passive"))
      (node (ref "D1") (pin "C") (pinfunction "C_C") (pintype "passive"))
      (node (ref "F1") (pin "2") (pinfunction "2_2") (pintype "passive"))
      (node (ref "IC10") (pin "5") (pinfunction "VIN+_5") (pintype "input"))
      (node (ref "IC4") (pin "5") (pinfunction "VIN+_5") (pintype "input"))
      (node (ref "R35") (pin "2") (pinfunction "2_2") (pintype "passive"))
      (node (ref "R37") (pin "2") (pinfunction "2_2") (pintype "passive"))
      (node (ref "R39") (pin "2") (pinfunction "2_2") (pintype "passive"))
    )
    (net (code "180") (name "Net-(IC11-WP)") (class "Default")
      (node (ref "IC11") (pin "7") (pinfunction "WP_7") (pintype "input"))
      (node (ref "R18") (pin "2") (pinfunction "2_2") (pintype "passive"))
      (node (ref "TP1") (pin "P$1") (pinfunction "TP_P$1") (pintype "passive"))
    )
    (net (code "181") (name "Net-(IC13-VIN)") (class "Default")
      (node (ref "C58") (pin "1") (pinfunction "1_1") (pintype "passive"))
      (node (ref "C59") (pin "1") (pinfunction "1_1") (pintype "passive"))
      (node (ref "IC13") (pin "1") (pinfunction "VIN_1") (pintype "bidirectional"))
      (node (ref "R93") (pin "2") (pinfunction "2_2") (pintype "passive"))
    )
    (net (code "182") (name "Net-(IC16A-+IN)") (class "Default")
      (node (ref "C62") (pin "1") (pinfunction "1_1") (pintype "passive"))
      (node (ref "IC16") (pin "3") (pinfunction "+IN_3") (pintype "input"))
      (node (ref "R95") (pin "2") (pinfunction "2_2") (pintype "passive"))
      (node (ref "R96") (pin "1") (pinfunction "1_1") (pintype "passive"))
    )
    (net (code "183") (name "Net-(IC16A--IN)") (class "Default")
      (node (ref "IC16") (pin "1") (pinfunction "OUT_1") (pintype "output"))
      (node (ref "IC16") (pin "2") (pinfunction "-IN_2") (pintype "input"))
      (node (ref "R101") (pin "2") (pinfunction "2_2") (pintype "passive"))
    )
    (net (code "184") (name "Net-(IC16B-+IN)") (class "Default")
      (node (ref "C63") (pin "1") (pinfunction "1_1") (pintype "passive"))
      (node (ref "IC16") (pin "5") (pinfunction "+IN_5") (pintype "input"))
      (node (ref "R98") (pin "2") (pinfunction "2_2") (pintype "passive"))
      (node (ref "R99") (pin "1") (pinfunction "1_1") (pintype "passive"))
    )
    (net (code "185") (name "Net-(IC16B--IN)") (class "Default")
      (node (ref "IC16") (pin "6") (pinfunction "-IN_6") (pintype "input"))
      (node (ref "IC16") (pin "7") (pinfunction "OUT_7") (pintype "output"))
      (node (ref "R100") (pin "2") (pinfunction "2_2") (pintype "passive"))
    )
    (net (code "186") (name "Net-(IC16C-V+)") (class "Default")
      (node (ref "C67") (pin "1") (pinfunction "1_1") (pintype "passive"))
      (node (ref "IC16") (pin "8") (pinfunction "V+_8") (pintype "input"))
      (node (ref "R103") (pin "1") (pinfunction "1_1") (pintype "passive"))
    )
    (net (code "187") (name "Net-(IC17--UNDERV)") (class "Default")
      (node (ref "IC17") (pin "23") (pinfunction "-UNDERV_23") (pintype "bidirectional"))
      (node (ref "R1") (pin "1") (pinfunction "1_1") (pintype "passive"))
    )
    (net (code "188") (name "Net-(IC17-C+)") (class "Default")
      (node (ref "C4") (pin "2") (pinfunction "2_2") (pintype "passive"))
      (node (ref "IC17") (pin "14") (pinfunction "C+_14") (pintype "input"))
    )
    (net (code "189") (name "Net-(IC17-C-)") (class "Default")
      (node (ref "C4") (pin "1") (pinfunction "1_1") (pintype "passive"))
      (node (ref "IC17") (pin "11") (pinfunction "C-_11") (pintype "input"))
    )
    (net (code "190") (name "Net-(IC17-CPO)") (class "Default")
      (node (ref "C5") (pin "1") (pinfunction "1_1") (pintype "passive"))
      (node (ref "IC17") (pin "15") (pinfunction "CPO_15") (pintype "bidirectional"))
    )
    (net (code "191") (name "Net-(IC17-DVCC)") (class "Default")
      (node (ref "C2") (pin "1") (pinfunction "1_1") (pintype "passive"))
      (node (ref "C3") (pin "1") (pinfunction "1_1") (pintype "passive"))
      (node (ref "C77") (pin "1") (pinfunction "1_1") (pintype "passive"))
      (node (ref "IC17") (pin "1") (pinfunction "DVCC_1") (pintype "bidirectional"))
      (node (ref "IC17") (pin "12") (pinfunction "SVBAT_12") (pintype "input"))
      (node (ref "IC17") (pin "13") (pinfunction "PVBAT_13") (pintype "input"))
      (node (ref "R1") (pin "2") (pinfunction "2_2") (pintype "passive"))
      (node (ref "R114") (pin "2") (pinfunction "2_2") (pintype "passive"))
    )
    (net (code "192") (name "Net-(IC17-NC{slash}-NO)") (class "Default")
      (node (ref "IC17") (pin "22") (pinfunction "NC/-NO_22") (pintype "bidirectional"))
      (node (ref "R2") (pin "1") (pinfunction "1_1") (pintype "passive"))
    )
    (net (code "193") (name "Net-(IC18-A)") (class "Default")
      (node (ref "IC18") (pin "1") (pinfunction "A_1") (pintype "input"))
      (node (ref "IC5") (pin "4") (pinfunction "OUT_4") (pintype "output"))
    )
    (net (code "194") (name "Net-(IC18-B)") (class "Default")
      (node (ref "IC18") (pin "2") (pinfunction "B_2") (pintype "input"))
      (node (ref "R122") (pin "2") (pinfunction "2_2") (pintype "passive"))
    )
    (net (code "195") (name "Net-(IC18-Y)") (class "Default")
      (node (ref "IC18") (pin "4") (pinfunction "Y_4") (pintype "output"))
      (node (ref "IC2") (pin "2") (pinfunction "B_2") (pintype "input"))
    )
    (net (code "196") (name "Net-(IC19-VCC)") (class "Default")
      (node (ref "C98") (pin "1") (pinfunction "1_1") (pintype "passive"))
      (node (ref "IC19") (pin "5") (pinfunction "VCC_5") (pintype "input"))
      (node (ref "IC20") (pin "5") (pinfunction "VCC_5") (pintype "input"))
      (node (ref "R132") (pin "2") (pinfunction "2_2") (pintype "passive"))
    )
    (net (code "197") (name "Net-(IC22-IN)") (class "Default")
      (node (ref "C45") (pin "1") (pinfunction "1_1") (pintype "passive"))
      (node (ref "IC22") (pin "2") (pinfunction "IN_2") (pintype "input"))
      (node (ref "R64") (pin "1") (pinfunction "1_1") (pintype "passive"))
    )
    (net (code "198") (name "Net-(IC22-VCC)") (class "Default")
      (node (ref "C79") (pin "1") (pinfunction "1_1") (pintype "passive"))
      (node (ref "IC22") (pin "5") (pinfunction "VCC_5") (pintype "input"))
      (node (ref "IC23") (pin "5") (pinfunction "VCC_5") (pintype "input"))
      (node (ref "R117") (pin "1") (pinfunction "1_1") (pintype "passive"))
    )
    (net (code "199") (name "Net-(IC23-IN)") (class "Default")
      (node (ref "C46") (pin "1") (pinfunction "1_1") (pintype "passive"))
      (node (ref "IC23") (pin "2") (pinfunction "IN_2") (pintype "input"))
      (node (ref "R76") (pin "1") (pinfunction "1_1") (pintype "passive"))
    )
    (net (code "200") (name "Net-(IC25-AVCC-Pad14)") (class "Default")
      (node (ref "IC25") (pin "14") (pinfunction "AVCC_14") (pintype "input"))
      (node (ref "R5") (pin "2") (pinfunction "2_2") (pintype "passive"))
    )
    (net (code "201") (name "Net-(IC25-GVDD)") (class "Default")
      (node (ref "C118") (pin "1") (pinfunction "1_1") (pintype "passive"))
      (node (ref "C12") (pin "1") (pinfunction "1_1") (pintype "passive"))
      (node (ref "IC25") (pin "10") (pinfunction "PLIMIT_10") (pintype "input"))
      (node (ref "IC25") (pin "9") (pinfunction "GVDD_9") (pintype "output"))
    )
    (net (code "202") (name "Net-(IC25-~{FAULT})") (class "Default")
      (node (ref "IC25") (pin "1") (pinfunction "~{SD}_1") (pintype "input"))
      (node (ref "IC25") (pin "2") (pinfunction "~{FAULT}_2") (pintype "output"))
      (node (ref "R6") (pin "2") (pinfunction "2_2") (pintype "passive"))
      (node (ref "R7") (pin "2") (pinfunction "2_2") (pintype "passive"))
    )
    (net (code "203") (name "Net-(IC26-Pad2)") (class "Default")
      (node (ref "IC26") (pin "2") (pinfunction "2_2") (pintype "passive"))
      (node (ref "J18") (pin "2") (pinfunction "2_2") (pintype "passive"))
      (node (ref "R109") (pin "2") (pinfunction "2_2") (pintype "passive"))
    )
    (net (code "204") (name "Net-(IC26-Pad3)") (class "Default")
      (node (ref "IC26") (pin "3") (pinfunction "3_3") (pintype "passive"))
      (node (ref "J18") (pin "3") (pinfunction "3_3") (pintype "passive"))
      (node (ref "R108") (pin "2") (pinfunction "2_2") (pintype "passive"))
    )
    (net (code "205") (name "Net-(IC27-Pad2)") (class "Default")
      (node (ref "IC27") (pin "2") (pinfunction "2_2") (pintype "passive"))
      (node (ref "J16") (pin "1") (pinfunction "1_1") (pintype "passive"))
      (node (ref "R153") (pin "2") (pinfunction "2_2") (pintype "passive"))
    )
    (net (code "206") (name "Net-(IC27-Pad3)") (class "Default")
      (node (ref "IC27") (pin "3") (pinfunction "3_3") (pintype "passive"))
      (node (ref "J16") (pin "2") (pinfunction "2_2") (pintype "passive"))
      (node (ref "R154") (pin "2") (pinfunction "2_2") (pintype "passive"))
    )
    (net (code "207") (name "Net-(IC28-Pad2)") (class "Default")
      (node (ref "IC28") (pin "2") (pinfunction "2_2") (pintype "passive"))
      (node (ref "J22") (pin "1") (pinfunction "1_1") (pintype "passive"))
      (node (ref "R152") (pin "2") (pinfunction "2_2") (pintype "passive"))
    )
    (net (code "208") (name "Net-(IC28-Pad3)") (class "Default")
      (node (ref "IC28") (pin "3") (pinfunction "3_3") (pintype "passive"))
      (node (ref "J22") (pin "2") (pinfunction "2_2") (pintype "passive"))
      (node (ref "R151") (pin "2") (pinfunction "2_2") (pintype "passive"))
    )
    (net (code "209") (name "Net-(IC30-FB)") (class "Default")
      (node (ref "IC30") (pin "1") (pinfunction "FB_1") (pintype "input"))
      (node (ref "R133") (pin "2") (pinfunction "2_2") (pintype "passive"))
    )
    (net (code "210") (name "Net-(IC30-RT)") (class "Default")
      (node (ref "IC30") (pin "6") (pinfunction "RT_6") (pintype "input"))
      (node (ref "R136") (pin "1") (pinfunction "1_1") (pintype "passive"))
    )
    (net (code "211") (name "Net-(IC30-SS)") (class "Default")
      (node (ref "C104") (pin "1") (pinfunction "1_1") (pintype "passive"))
      (node (ref "IC30") (pin "7") (pinfunction "SS_7") (pintype "input"))
    )
    (net (code "212") (name "Net-(IC30-SW)") (class "Default")
      (node (ref "D8") (pin "A") (pinfunction "A_A") (pintype "passive"))
      (node (ref "IC30") (pin "4") (pinfunction "SW_4") (pintype "output"))
      (node (ref "L3") (pin "2") (pinfunction "2_2") (pintype "passive"))
    )
    (net (code "213") (name "Net-(IC30-VC)") (class "Default")
      (node (ref "IC30") (pin "2") (pinfunction "VC_2") (pintype "input"))
      (node (ref "R135") (pin "1") (pinfunction "1_1") (pintype "passive"))
    )
    (net (code "214") (name "Net-(IC30-VIN)") (class "Default")
      (node (ref "C100") (pin "1") (pinfunction "1_1") (pintype "passive"))
      (node (ref "C101") (pin "1") (pinfunction "1_1") (pintype "passive"))
      (node (ref "C99") (pin "1") (pinfunction "1_1") (pintype "passive"))
      (node (ref "IC30") (pin "3") (pinfunction "VIN_3") (pintype "input"))
      (node (ref "L3") (pin "1") (pinfunction "1_1") (pintype "passive"))
      (node (ref "L4") (pin "2") (pinfunction "2_2") (pintype "passive"))
      (node (ref "R134") (pin "1") (pinfunction "1_1") (pintype "passive"))
    )
    (net (code "215") (name "Net-(IC30-{slash}SHDN)") (class "Default")
      (node (ref "C113") (pin "1") (pinfunction "1_1") (pintype "passive"))
      (node (ref "IC30") (pin "5") (pinfunction "/SHDN_5") (pintype "input"))
      (node (ref "R134") (pin "2") (pinfunction "2_2") (pintype "passive"))
      (node (ref "R137") (pin "1") (pinfunction "1_1") (pintype "passive"))
    )
    (net (code "216") (name "Net-(IC31-A)") (class "Default")
      (node (ref "IC31") (pin "6") (pinfunction "A_6") (pintype "bidirectional"))
      (node (ref "J23") (pin "4") (pinfunction "4_4") (pintype "passive"))
      (node (ref "R144") (pin "1") (pinfunction "1_1") (pintype "passive"))
      (node (ref "R145") (pin "2") (pinfunction "2_2") (pintype "passive"))
    )
    (net (code "217") (name "Net-(IC31-B)") (class "Default")
      (node (ref "IC31") (pin "7") (pinfunction "B_7") (pintype "bidirectional"))
      (node (ref "J23") (pin "3") (pinfunction "3_3") (pintype "passive"))
      (node (ref "R145") (pin "1") (pinfunction "1_1") (pintype "passive"))
      (node (ref "R146") (pin "2") (pinfunction "2_2") (pintype "passive"))
    )
    (net (code "218") (name "Net-(J1-RXD-C)") (class "Default")
      (node (ref "J1") (pin "34") (pinfunction "RXD-C_34") (pintype "passive"))
      (node (ref "R123") (pin "1") (pinfunction "1_1") (pintype "passive"))
    )
    (net (code "219") (name "Net-(J1-TXD-C)") (class "Default")
      (node (ref "J1") (pin "35") (pinfunction "TXD-C_35") (pintype "passive"))
      (node (ref "R124") (pin "2") (pinfunction "2_2") (pintype "passive"))
    )
    (net (code "220") (name "Net-(J7-Pad2)") (class "Default")
      (node (ref "J7") (pin "2") (pinfunction "2_2") (pintype "passive"))
      (node (ref "R66") (pin "2") (pinfunction "2_2") (pintype "passive"))
      (node (ref "R67") (pin "2") (pinfunction "2_2") (pintype "passive"))
    )
    (net (code "221") (name "Net-(J7-Pad3)") (class "Default")
      (node (ref "J7") (pin "3") (pinfunction "3_3") (pintype "passive"))
      (node (ref "R62") (pin "1") (pinfunction "1_1") (pintype "passive"))
    )
    (net (code "222") (name "Net-(J8-Pad2)") (class "Default")
      (node (ref "J8") (pin "2") (pinfunction "2_2") (pintype "passive"))
      (node (ref "R78") (pin "2") (pinfunction "2_2") (pintype "passive"))
      (node (ref "R79") (pin "2") (pinfunction "2_2") (pintype "passive"))
    )
    (net (code "223") (name "Net-(J8-Pad3)") (class "Default")
      (node (ref "J8") (pin "3") (pinfunction "3_3") (pintype "passive"))
      (node (ref "R73") (pin "1") (pinfunction "1_1") (pintype "passive"))
    )
    (net (code "224") (name "Net-(J12-+5V)") (class "Default")
      (node (ref "C85") (pin "1") (pinfunction "1_1") (pintype "passive"))
      (node (ref "D6") (pin "A") (pinfunction "A_A") (pintype "passive"))
      (node (ref "IC15") (pin "4") (pinfunction "4_4") (pintype "input"))
      (node (ref "J12") (pin "1_+5V") (pinfunction "+5V_1_+5V") (pintype "bidirectional"))
      (node (ref "R128") (pin "1") (pinfunction "1_1") (pintype "passive"))
    )
    (net (code "225") (name "Net-(J20-Pad2)") (class "Default")
      (node (ref "J20") (pin "2") (pinfunction "2_2") (pintype "passive"))
      (node (ref "Q7") (pin "1") (pinfunction "D_1") (pintype "passive"))
      (node (ref "Q7") (pin "2") (pinfunction "D_2") (pintype "passive"))
      (node (ref "Q7") (pin "5") (pinfunction "D_5") (pintype "passive"))
      (node (ref "Q7") (pin "6") (pinfunction "D_6") (pintype "passive"))
    )
    (net (code "226") (name "Net-(JP1-Pad1)") (class "Default")
      (node (ref "JP1") (pin "1") (pinfunction "1_1") (pintype "bidirectional"))
      (node (ref "R21") (pin "1") (pinfunction "1_1") (pintype "passive"))
    )
    (net (code "227") (name "Net-(L13-Pad1)") (class "Default")
      (node (ref "L13") (pin "1") (pinfunction "1_1") (pintype "passive"))
      (node (ref "R92") (pin "2") (pinfunction "2_2") (pintype "passive"))
    )
    (net (code "228") (name "Net-(Q1A-G)") (class "Default")
      (node (ref "C43") (pin "2") (pinfunction "2_2") (pintype "passive"))
      (node (ref "Q1") (pin "2") (pinfunction "G_2") (pintype "passive"))
      (node (ref "R50") (pin "1") (pinfunction "1_1") (pintype "passive"))
      (node (ref "R51") (pin "2") (pinfunction "2_2") (pintype "passive"))
    )
    (net (code "229") (name "Net-(Q1A-S)") (class "Default")
      (node (ref "Q1") (pin "1") (pinfunction "S_1") (pintype "passive"))
      (node (ref "R52") (pin "1") (pinfunction "1_1") (pintype "passive"))
    )
    (net (code "230") (name "Net-(Q1B-G)") (class "Default")
      (node (ref "C82") (pin "2") (pinfunction "2_2") (pintype "passive"))
      (node (ref "Q1") (pin "5") (pinfunction "G_5") (pintype "passive"))
      (node (ref "R125") (pin "1") (pinfunction "1_1") (pintype "passive"))
      (node (ref "R126") (pin "2") (pinfunction "2_2") (pintype "passive"))
    )
    (net (code "231") (name "Net-(Q1B-S)") (class "Default")
      (node (ref "Q1") (pin "4") (pinfunction "S_4") (pintype "passive"))
      (node (ref "R127") (pin "1") (pinfunction "1_1") (pintype "passive"))
    )
    (net (code "232") (name "Net-(Q2A-G)") (class "Default")
      (node (ref "C70") (pin "2") (pinfunction "2_2") (pintype "passive"))
      (node (ref "Q2") (pin "2") (pinfunction "G_2") (pintype "passive"))
      (node (ref "R75") (pin "1") (pinfunction "1_1") (pintype "passive"))
      (node (ref "R82") (pin "2") (pinfunction "2_2") (pintype "passive"))
    )
    (net (code "233") (name "Net-(Q2A-S)") (class "Default")
      (node (ref "Q2") (pin "1") (pinfunction "S_1") (pintype "passive"))
      (node (ref "R106") (pin "1") (pinfunction "1_1") (pintype "passive"))
    )
    (net (code "234") (name "Net-(Q2B-G)") (class "Default")
      (node (ref "C69") (pin "2") (pinfunction "2_2") (pintype "passive"))
      (node (ref "Q2") (pin "5") (pinfunction "G_5") (pintype "passive"))
      (node (ref "R24") (pin "1") (pinfunction "1_1") (pintype "passive"))
      (node (ref "R65") (pin "2") (pinfunction "2_2") (pintype "passive"))
    )
    (net (code "235") (name "Net-(Q2B-S)") (class "Default")
      (node (ref "Q2") (pin "4") (pinfunction "S_4") (pintype "passive"))
      (node (ref "R105") (pin "1") (pinfunction "1_1") (pintype "passive"))
    )
    (net (code "236") (name "Net-(Q3-G)") (class "Default")
      (node (ref "C33") (pin "2") (pinfunction "2_2") (pintype "passive"))
      (node (ref "Q3") (pin "3") (pinfunction "G_3") (pintype "passive"))
      (node (ref "Q4") (pin "6") (pinfunction "D_6") (pintype "passive"))
      (node (ref "R42") (pin "2") (pinfunction "2_2") (pintype "passive"))
    )
    (net (code "237") (name "Net-(Q4A-S)") (class "Default")
      (node (ref "Q4") (pin "1") (pinfunction "S_1") (pintype "passive"))
      (node (ref "R40") (pin "2") (pinfunction "2_2") (pintype "passive"))
    )
    (net (code "238") (name "Net-(Q4B-D)") (class "Default")
      (node (ref "C34") (pin "2") (pinfunction "2_2") (pintype "passive"))
      (node (ref "Q4") (pin "3") (pinfunction "D_3") (pintype "passive"))
      (node (ref "Q5") (pin "3") (pinfunction "G_3") (pintype "passive"))
      (node (ref "R45") (pin "2") (pinfunction "2_2") (pintype "passive"))
    )
    (net (code "239") (name "Net-(Q4B-S)") (class "Default")
      (node (ref "Q4") (pin "4") (pinfunction "S_4") (pintype "passive"))
      (node (ref "R43") (pin "2") (pinfunction "2_2") (pintype "passive"))
    )
    (net (code "240") (name "Net-(Q6A-D)") (class "Default")
      (node (ref "C32") (pin "2") (pinfunction "2_2") (pintype "passive"))
      (node (ref "Q6") (pin "6") (pinfunction "D_6") (pintype "passive"))
      (node (ref "Q7") (pin "3") (pinfunction "G_3") (pintype "passive"))
      (node (ref "R11") (pin "2") (pinfunction "2_2") (pintype "passive"))
    )
    (net (code "241") (name "Net-(Q6A-S)") (class "Default")
      (node (ref "Q6") (pin "1") (pinfunction "S_1") (pintype "passive"))
      (node (ref "R12") (pin "2") (pinfunction "2_2") (pintype "passive"))
    )
    (net (code "242") (name "Net-(Q6B-D)") (class "Default")
      (node (ref "C37") (pin "2") (pinfunction "2_2") (pintype "passive"))
      (node (ref "Q6") (pin "3") (pinfunction "D_3") (pintype "passive"))
      (node (ref "Q8") (pin "3") (pinfunction "G_3") (pintype "passive"))
      (node (ref "R14") (pin "2") (pinfunction "2_2") (pintype "passive"))
    )
    (net (code "243") (name "Net-(Q6B-S)") (class "Default")
      (node (ref "Q6") (pin "4") (pinfunction "S_4") (pintype "passive"))
      (node (ref "R15") (pin "2") (pinfunction "2_2") (pintype "passive"))
    )
    (net (code "244") (name "Net-(Q9B-D)") (class "Default")
      (node (ref "Q9") (pin "3") (pinfunction "D_3") (pintype "passive"))
      (node (ref "R60") (pin "1") (pinfunction "1_1") (pintype "passive"))
    )
    (net (code "245") (name "Net-(Q10A-D)") (class "Default")
      (node (ref "Q10") (pin "6") (pinfunction "D_6") (pintype "passive"))
      (node (ref "R68") (pin "1") (pinfunction "1_1") (pintype "passive"))
      (node (ref "R69") (pin "1") (pinfunction "1_1") (pintype "passive"))
    )
    (net (code "246") (name "Net-(Q10A-G)") (class "Default")
      (node (ref "Q10") (pin "2") (pinfunction "G_2") (pintype "passive"))
      (node (ref "R116") (pin "2") (pinfunction "2_2") (pintype "passive"))
      (node (ref "R70") (pin "2") (pinfunction "2_2") (pintype "passive"))
    )
    (net (code "247") (name "Net-(Q10B-D)") (class "Default")
      (node (ref "Q10") (pin "3") (pinfunction "D_3") (pintype "passive"))
      (node (ref "R80") (pin "1") (pinfunction "1_1") (pintype "passive"))
      (node (ref "R81") (pin "1") (pinfunction "1_1") (pintype "passive"))
    )
    (net (code "248") (name "Net-(Q10B-G)") (class "Default")
      (node (ref "Q10") (pin "5") (pinfunction "G_5") (pintype "passive"))
      (node (ref "R119") (pin "2") (pinfunction "2_2") (pintype "passive"))
      (node (ref "R83") (pin "2") (pinfunction "2_2") (pintype "passive"))
    )
    (net (code "249") (name "Net-(Q11A-D)") (class "Default")
      (node (ref "C107") (pin "2") (pinfunction "2_2") (pintype "passive"))
      (node (ref "Q11") (pin "6") (pinfunction "D_6") (pintype "passive"))
      (node (ref "Q12") (pin "3") (pinfunction "G_3") (pintype "passive"))
      (node (ref "R139") (pin "2") (pinfunction "2_2") (pintype "passive"))
    )
    (net (code "250") (name "Net-(Q11A-S)") (class "Default")
      (node (ref "Q11") (pin "1") (pinfunction "S_1") (pintype "passive"))
      (node (ref "R140") (pin "2") (pinfunction "2_2") (pintype "passive"))
    )
    (net (code "251") (name "Net-(Q11B-D)") (class "Default")
      (node (ref "C108") (pin "2") (pinfunction "2_2") (pintype "passive"))
      (node (ref "Q11") (pin "3") (pinfunction "D_3") (pintype "passive"))
      (node (ref "Q13") (pin "2") (pinfunction "G_2") (pintype "passive"))
      (node (ref "R142") (pin "2") (pinfunction "2_2") (pintype "passive"))
    )
    (net (code "252") (name "Net-(Q11B-S)") (class "Default")
      (node (ref "Q11") (pin "4") (pinfunction "S_4") (pintype "passive"))
      (node (ref "R141") (pin "2") (pinfunction "2_2") (pintype "passive"))
    )
    (net (code "253") (name "Net-(Q13A-S)") (class "Default")
      (node (ref "Q13") (pin "1") (pinfunction "S_1") (pintype "passive"))
      (node (ref "R143") (pin "1") (pinfunction "1_1") (pintype "passive"))
    )
    (net (code "254") (name "Net-(R23-Pad1)") (class "Default")
      (node (ref "R23") (pin "1") (pinfunction "1_1") (pintype "passive"))
      (node (ref "R49") (pin "2") (pinfunction "2_2") (pintype "passive"))
    )
    (net (code "255") (name "Net-(R62-Pad2)") (class "Default")
      (node (ref "R62") (pin "2") (pinfunction "2_2") (pintype "passive"))
      (node (ref "R63") (pin "1") (pinfunction "1_1") (pintype "passive"))
      (node (ref "R64") (pin "2") (pinfunction "2_2") (pintype "passive"))
    )
    (net (code "256") (name "Net-(R66-Pad1)") (class "Default")
      (node (ref "R66") (pin "1") (pinfunction "1_1") (pintype "passive"))
      (node (ref "R67") (pin "1") (pinfunction "1_1") (pintype "passive"))
      (node (ref "R68") (pin "2") (pinfunction "2_2") (pintype "passive"))
      (node (ref "R69") (pin "2") (pinfunction "2_2") (pintype "passive"))
    )
    (net (code "257") (name "Net-(R73-Pad2)") (class "Default")
      (node (ref "R73") (pin "2") (pinfunction "2_2") (pintype "passive"))
      (node (ref "R74") (pin "1") (pinfunction "1_1") (pintype "passive"))
      (node (ref "R76") (pin "2") (pinfunction "2_2") (pintype "passive"))
    )
    (net (code "258") (name "Net-(R94-Pad2)") (class "Default")
      (node (ref "R94") (pin "2") (pinfunction "2_2") (pintype "passive"))
      (node (ref "R95") (pin "1") (pinfunction "1_1") (pintype "passive"))
    )
    (net (code "259") (name "Net-(R97-Pad2)") (class "Default")
      (node (ref "R97") (pin "2") (pinfunction "2_2") (pintype "passive"))
      (node (ref "R98") (pin "1") (pinfunction "1_1") (pintype "passive"))
    )
    (net (code "260") (name "VBAT") (class "Default")
      (node (ref "C33") (pin "1") (pinfunction "1_1") (pintype "passive"))
      (node (ref "C37") (pin "1") (pinfunction "1_1") (pintype "passive"))
      (node (ref "C75") (pin "1") (pinfunction "1_1") (pintype "passive"))
      (node (ref "IC10") (pin "4") (pinfunction "VIN-_4") (pintype "input"))
      (node (ref "J7") (pin "1") (pinfunction "1_1") (pintype "passive"))
      (node (ref "J8") (pin "1") (pinfunction "1_1") (pintype "passive"))
      (node (ref "JP2") (pin "1") (pinfunction "1_1") (pintype "bidirectional"))
      (node (ref "L2") (pin "1") (pinfunction "1_1") (pintype "passive"))
      (node (ref "Q3") (pin "4") (pinfunction "S_4") (pintype "passive"))
      (node (ref "Q8") (pin "4") (pinfunction "S_4") (pintype "passive"))
      (node (ref "R14") (pin "1") (pinfunction "1_1") (pintype "passive"))
      (node (ref "R33") (pin "2") (pinfunction "2_2") (pintype "passive"))
      (node (ref "R39") (pin "1") (pinfunction "1_1") (pintype "passive"))
      (node (ref "R42") (pin "1") (pinfunction "1_1") (pintype "passive"))
      (node (ref "R97") (pin "1") (pinfunction "1_1") (pintype "passive"))
    )
    (net (code "261") (name "unconnected-(IC1-AN12{slash}PMA11{slash}RB12-Pad41)") (class "Default")
      (node (ref "IC1") (pin "41") (pinfunction "AN12/PMA11/RB12_41") (pintype "bidirectional"))
    )
    (net (code "262") (name "unconnected-(IC1-RPF3{slash}USBID{slash}RF3-Pad51)") (class "Default")
      (node (ref "IC1") (pin "51") (pinfunction "RPF3/USBID/RF3_51") (pintype "bidirectional"))
    )
    (net (code "263") (name "unconnected-(IC1-RPF12{slash}RF12-Pad40)") (class "Default")
      (node (ref "IC1") (pin "40") (pinfunction "RPF12/RF12_40") (pintype "bidirectional"))
    )
    (net (code "264") (name "unconnected-(IC1-TMS{slash}CTED1{slash}RA0-Pad17)") (class "Default")
      (node (ref "IC1") (pin "17") (pinfunction "TMS/CTED1/RA0_17") (pintype "bidirectional"))
    )
    (net (code "265") (name "unconnected-(IC8-PG-Pad9)") (class "Default")
      (node (ref "IC8") (pin "9") (pinfunction "PG_9") (pintype "bidirectional"))
    )
    (net (code "266") (name "unconnected-(IC17-NC-Pad16)") (class "Default")
      (node (ref "IC17") (pin "16") (pinfunction "NC_16") (pintype "bidirectional"))
    )
    (net (code "267") (name "unconnected-(IC24-OS-Pad3)") (class "Default")
      (node (ref "IC24") (pin "3") (pinfunction "OS_3") (pintype "output"))
    )
    (net (code "268") (name "unconnected-(IC25-NC-Pad13)") (class "Default")
      (node (ref "IC25") (pin "13") (pinfunction "NC_13") (pintype "no_connect"))
    )
    (net (code "269") (name "unconnected-(IC29-GPIO-EXPR-00-Pad6)") (class "Default")
      (node (ref "IC29") (pin "6") (pinfunction "GPIO-EXPR-00_6") (pintype "bidirectional"))
    )
    (net (code "270") (name "unconnected-(IC29-NC-Pad5)") (class "Default")
      (node (ref "IC29") (pin "5") (pinfunction "NC_5") (pintype "passive"))
    )
    (net (code "271") (name "unconnected-(IC29-NC-Pad12)") (class "Default")
      (node (ref "IC29") (pin "12") (pinfunction "NC_12") (pintype "passive"))
    )
    (net (code "272") (name "unconnected-(IC29-NC-Pad13)") (class "Default")
      (node (ref "IC29") (pin "13") (pinfunction "NC_13") (pintype "passive"))
    )
    (net (code "273") (name "unconnected-(IC29-NC-Pad14)") (class "Default")
      (node (ref "IC29") (pin "14") (pinfunction "NC_14") (pintype "passive"))
    )
    (net (code "274") (name "unconnected-(IC29-NC-Pad15)") (class "Default")
      (node (ref "IC29") (pin "15") (pinfunction "NC_15") (pintype "passive"))
    )
    (net (code "275") (name "unconnected-(IC29-NC-Pad27)") (class "Default")
      (node (ref "IC29") (pin "27") (pinfunction "NC_27") (pintype "passive"))
    )
    (net (code "276") (name "unconnected-(IC29-NC-Pad28)") (class "Default")
      (node (ref "IC29") (pin "28") (pinfunction "NC_28") (pintype "passive"))
    )
    (net (code "277") (name "unconnected-(IC29-PP{slash}GPIO{slash}TWI_WUP-Pad7)") (class "Default")
      (node (ref "IC29") (pin "7") (pinfunction "PP/GPIO/TWI_WUP_7") (pintype "bidirectional"))
    )
    (net (code "278") (name "unconnected-(J1-+5V-Pad12)") (class "Default")
      (node (ref "J1") (pin "12") (pinfunction "+5V_12") (pintype "passive"))
    )
    (net (code "279") (name "unconnected-(J1-AGND-Pad26)") (class "Default")
      (node (ref "J1") (pin "26") (pinfunction "AGND_26") (pintype "passive"))
    )
    (net (code "280") (name "unconnected-(J1-AN-IN0-Pad25)") (class "Default")
      (node (ref "J1") (pin "25") (pinfunction "AN-IN0_25") (pintype "passive"))
    )
    (net (code "281") (name "unconnected-(J1-AN-IN1-Pad24)") (class "Default")
      (node (ref "J1") (pin "24") (pinfunction "AN-IN1_24") (pintype "passive"))
    )
    (net (code "282") (name "unconnected-(J1-AN-IN2-Pad23)") (class "Default")
      (node (ref "J1") (pin "23") (pinfunction "AN-IN2_23") (pintype "passive"))
    )
    (net (code "283") (name "unconnected-(J1-AN-IN3-Pad22)") (class "Default")
      (node (ref "J1") (pin "22") (pinfunction "AN-IN3_22") (pintype "passive"))
    )
    (net (code "284") (name "unconnected-(J1-CTS-B-Pad29)") (class "Default")
      (node (ref "J1") (pin "29") (pinfunction "CTS-B_29") (pintype "passive"))
    )
    (net (code "285") (name "unconnected-(J1-PWM_A-Pad37)") (class "Default")
      (node (ref "J1") (pin "37") (pinfunction "PWM_A_37") (pintype "passive"))
    )
    (net (code "286") (name "unconnected-(J1-PWM_D-Pad40)") (class "Default")
      (node (ref "J1") (pin "40") (pinfunction "PWM_D_40") (pintype "passive"))
    )
    (net (code "287") (name "unconnected-(J1-RTS-B-Pad30)") (class "Default")
      (node (ref "J1") (pin "30") (pinfunction "RTS-B_30") (pintype "passive"))
    )
    (net (code "288") (name "unconnected-(J1-SSP-FRM-Pad9)") (class "Default")
      (node (ref "J1") (pin "9") (pinfunction "SSP-FRM_9") (pintype "passive"))
    )
    (net (code "289") (name "unconnected-(J1-SSP-RXD-Pad10)") (class "Default")
      (node (ref "J1") (pin "10") (pinfunction "SSP-RXD_10") (pintype "passive"))
    )
    (net (code "290") (name "unconnected-(J1-SSP-SCLK-Pad8)") (class "Default")
      (node (ref "J1") (pin "8") (pinfunction "SSP-SCLK_8") (pintype "passive"))
    )
    (net (code "291") (name "unconnected-(J1-SSP-TXD-Pad11)") (class "Default")
      (node (ref "J1") (pin "11") (pinfunction "SSP-TXD_11") (pintype "passive"))
    )
    (net (code "292") (name "unconnected-(J2-PadC4)") (class "Default")
      (node (ref "J2") (pin "C4") (pinfunction "C4_C4") (pintype "no_connect"))
    )
    (net (code "293") (name "unconnected-(J2-PadC6)") (class "Default")
      (node (ref "J2") (pin "C6") (pinfunction "C6_C6") (pintype "no_connect"))
    )
    (net (code "294") (name "unconnected-(J2-PadC8)") (class "Default")
      (node (ref "J2") (pin "C8") (pinfunction "C8_C8") (pintype "no_connect"))
    )
    (net (code "295") (name "unconnected-(J5-Pad2)") (class "Default")
      (node (ref "J5") (pin "2") (pinfunction "2_2") (pintype "passive"))
    )
    (net (code "296") (name "unconnected-(J5-Pad3)") (class "Default")
      (node (ref "J5") (pin "3") (pinfunction "3_3") (pintype "passive"))
    )
    (net (code "297") (name "unconnected-(J5-Pad10)") (class "Default")
      (node (ref "J5") (pin "10") (pinfunction "10_10") (pintype "passive"))
    )
    (net (code "298") (name "unconnected-(J9-Pad5)") (class "Default")
      (node (ref "J9") (pin "5") (pinfunction "5_5") (pintype "passive"))
    )
    (net (code "299") (name "unconnected-(J14-Pad8)") (class "Default")
      (node (ref "J14") (pin "8") (pinfunction "8_8") (pintype "passive"))
    )
    (net (code "300") (name "unconnected-(J15-Pad5)") (class "Default")
      (node (ref "J15") (pin "5") (pinfunction "5_5") (pintype "passive"))
    )
    (net (code "301") (name "unconnected-(J21-Pad5)") (class "Default")
      (node (ref "J21") (pin "5") (pinfunction "5_5") (pintype "passive"))
    )
    (net (code "302") (name "unconnected-(JP2-Pad3)") (class "Default")
      (node (ref "JP2") (pin "3") (pinfunction "3_3") (pintype "bidirectional"))
    )
    (net (code "303") (name "unconnected-(PCB1-Pad3)") (class "Default")
      (node (ref "PCB1") (pin "3") (pinfunction "3_3") (pintype "bidirectional"))
    )
    (net (code "304") (name "unconnected-(PCB2-Pad1)") (class "Default")
      (node (ref "PCB2") (pin "1") (pinfunction "1_1") (pintype "bidirectional"))
    )
    (net (code "305") (name "unconnected-(PCB2-Pad2)") (class "Default")
      (node (ref "PCB2") (pin "2") (pinfunction "2_2") (pintype "bidirectional"))
    )
    (net (code "306") (name "unconnected-(PCB2-Pad3)") (class "Default")
      (node (ref "PCB2") (pin "3") (pinfunction "3_3") (pintype "bidirectional"))
    )
    (net (code "307") (name "unconnected-(PCB2-Pad4)") (class "Default")
      (node (ref "PCB2") (pin "4") (pinfunction "4_4") (pintype "bidirectional"))
    )
    (net (code "308") (name "unconnected-(Q13B-D-Pad3)") (class "Default")
      (node (ref "Q13") (pin "3") (pinfunction "D_3") (pintype "passive"))
    )
    (net (code "309") (name "unconnected-(Q13B-D1-PadP2)") (class "Default")
      (node (ref "Q13") (pin "P2") (pinfunction "D1_P2") (pintype "passive"))
    )
    (net (code "310") (name "unconnected-(Q13B-G-Pad5)") (class "Default")
      (node (ref "Q13") (pin "5") (pinfunction "G_5") (pintype "passive"))
    )
    (net (code "311") (name "unconnected-(Q13B-S-Pad4)") (class "Default")
      (node (ref "Q13") (pin "4") (pinfunction "S_4") (pintype "passive"))
    )
  )
)
